# PWM_Board_77X.net
KiCad netlist of a schematic drawn in EAGLE
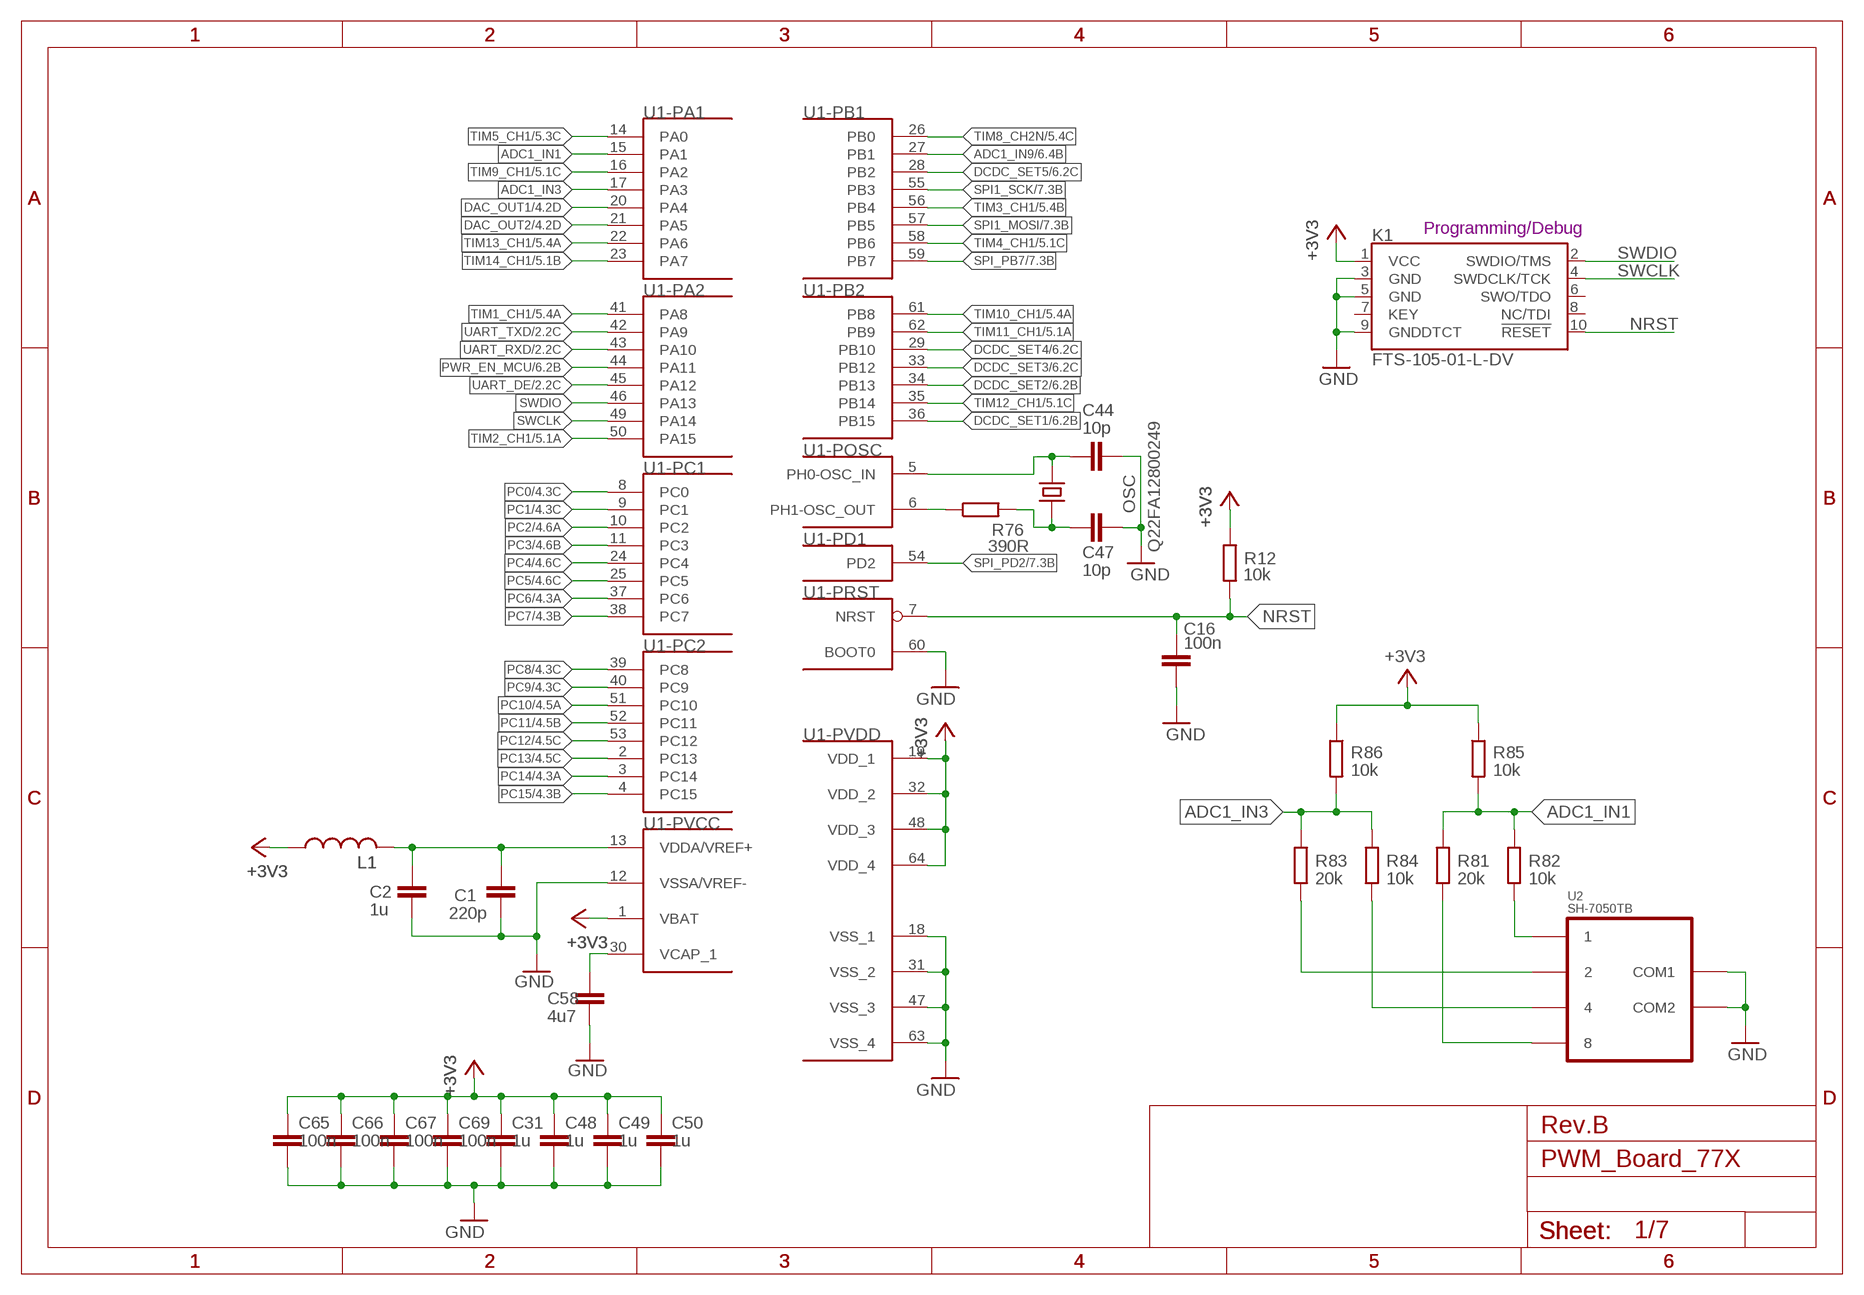
[diagram p0: schematic, sheet 1]
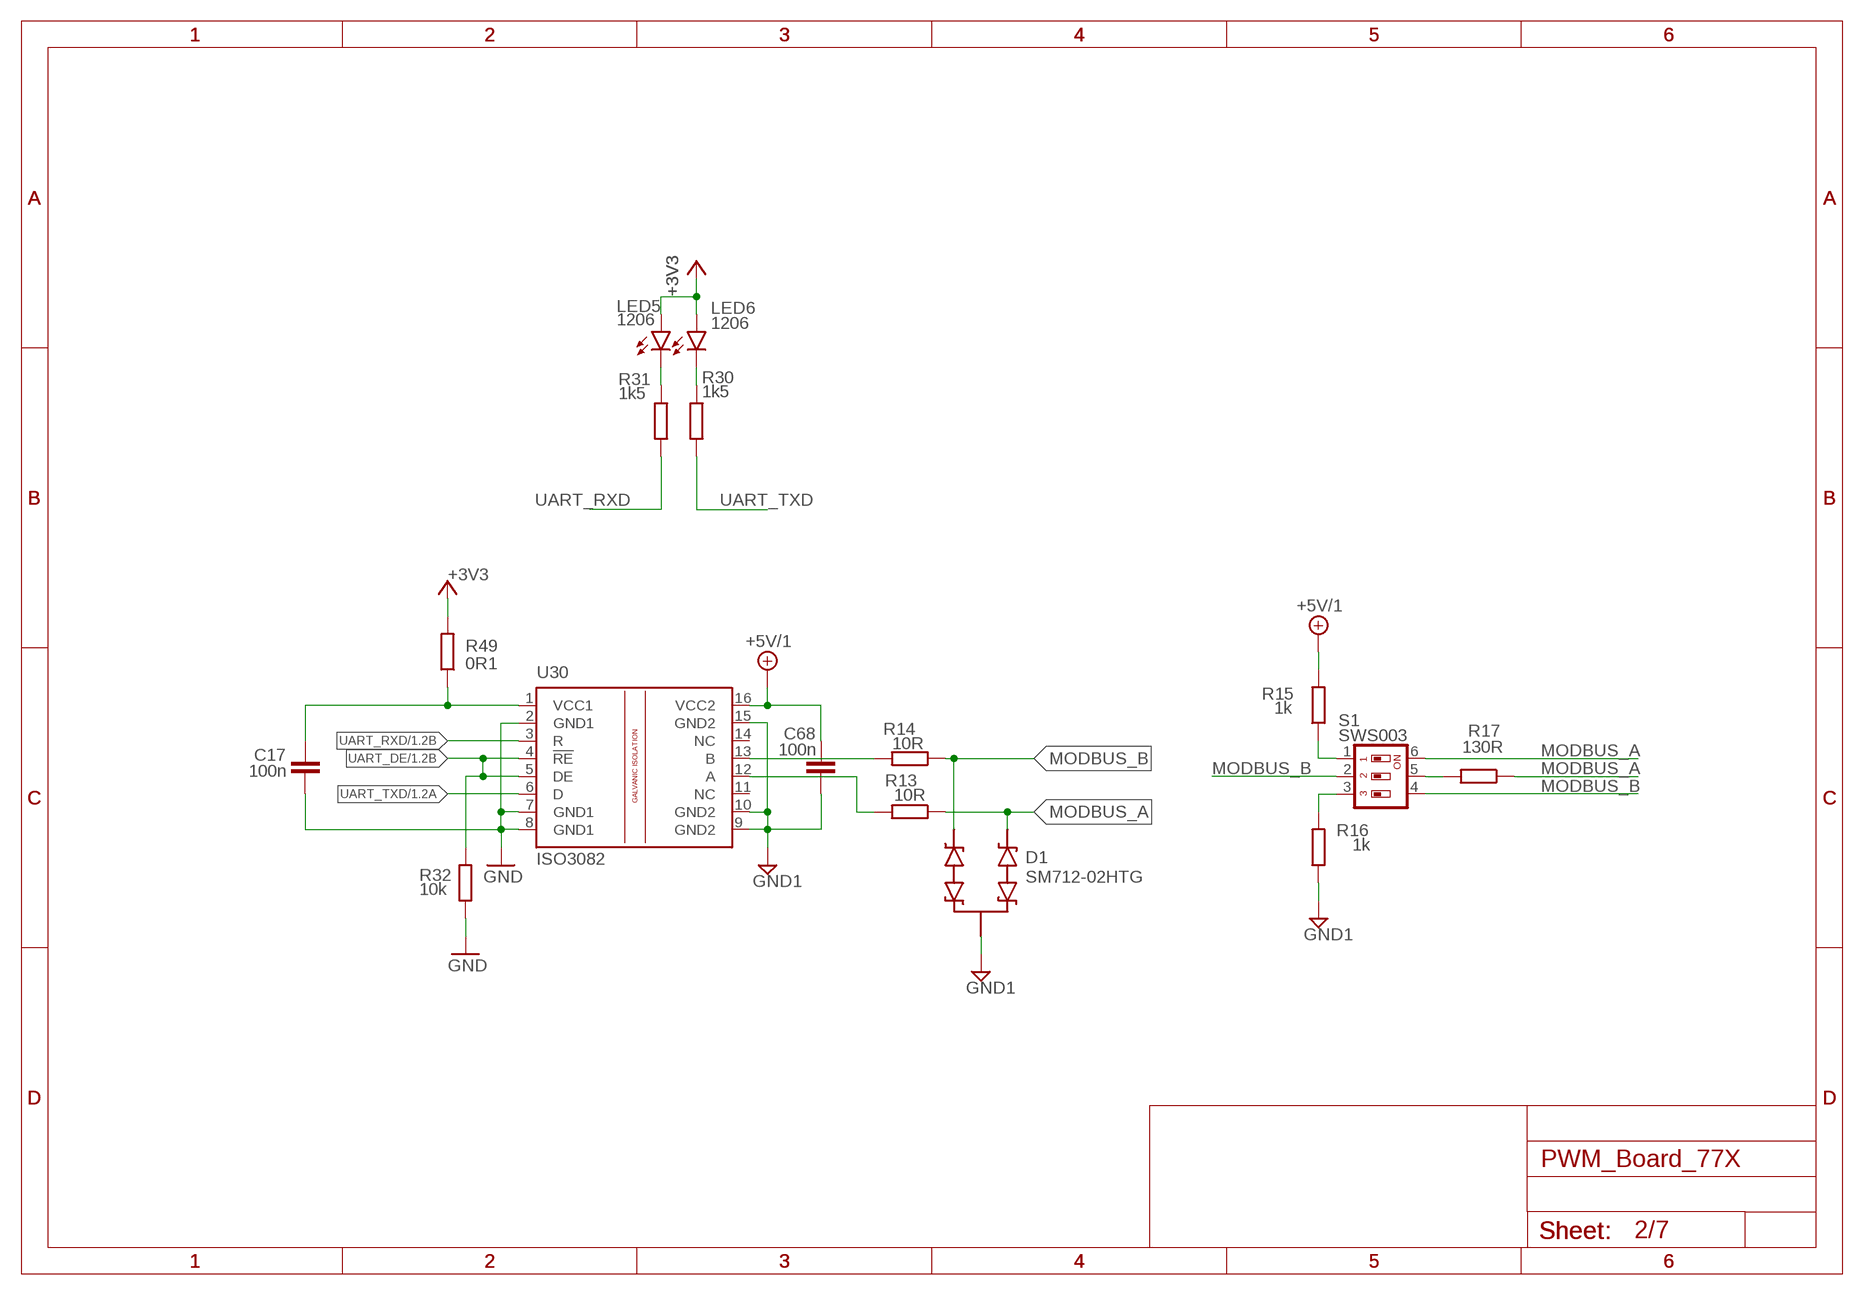
[diagram p1: schematic, sheet 2]
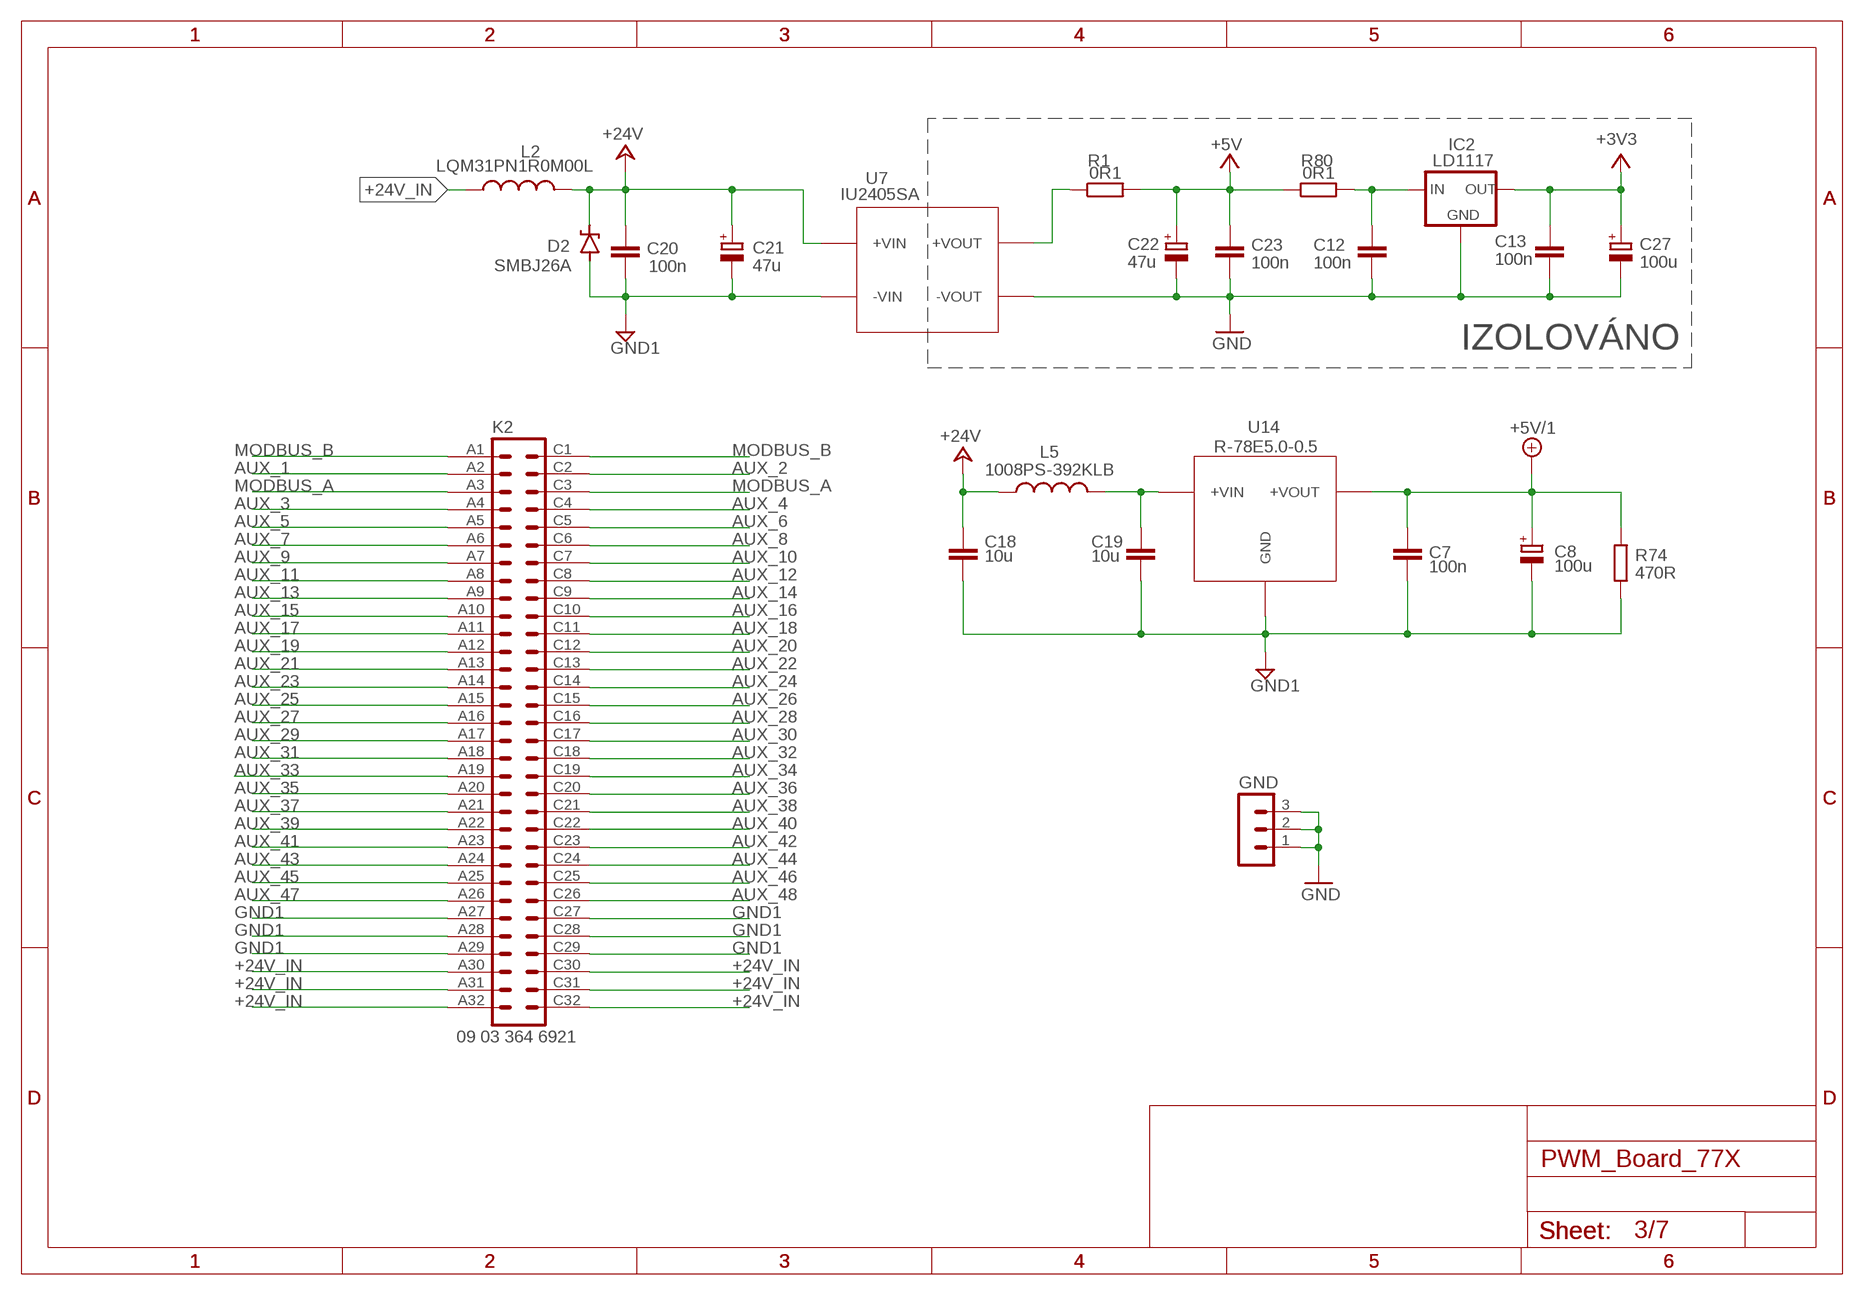
[diagram p2: schematic, sheet 3]
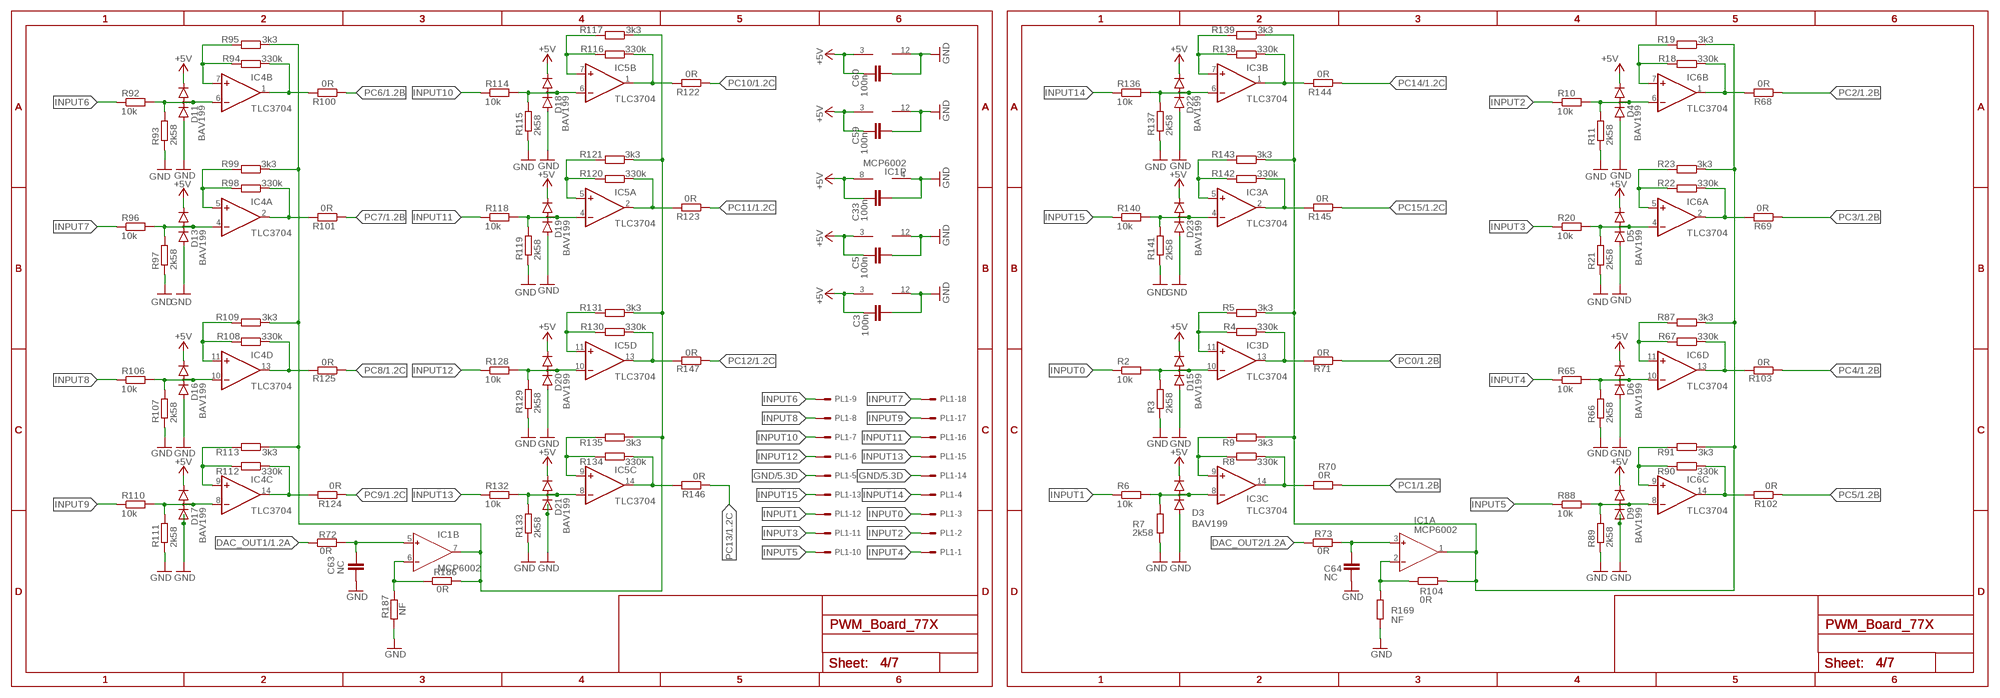
[diagram p3: schematic, sheet 4]
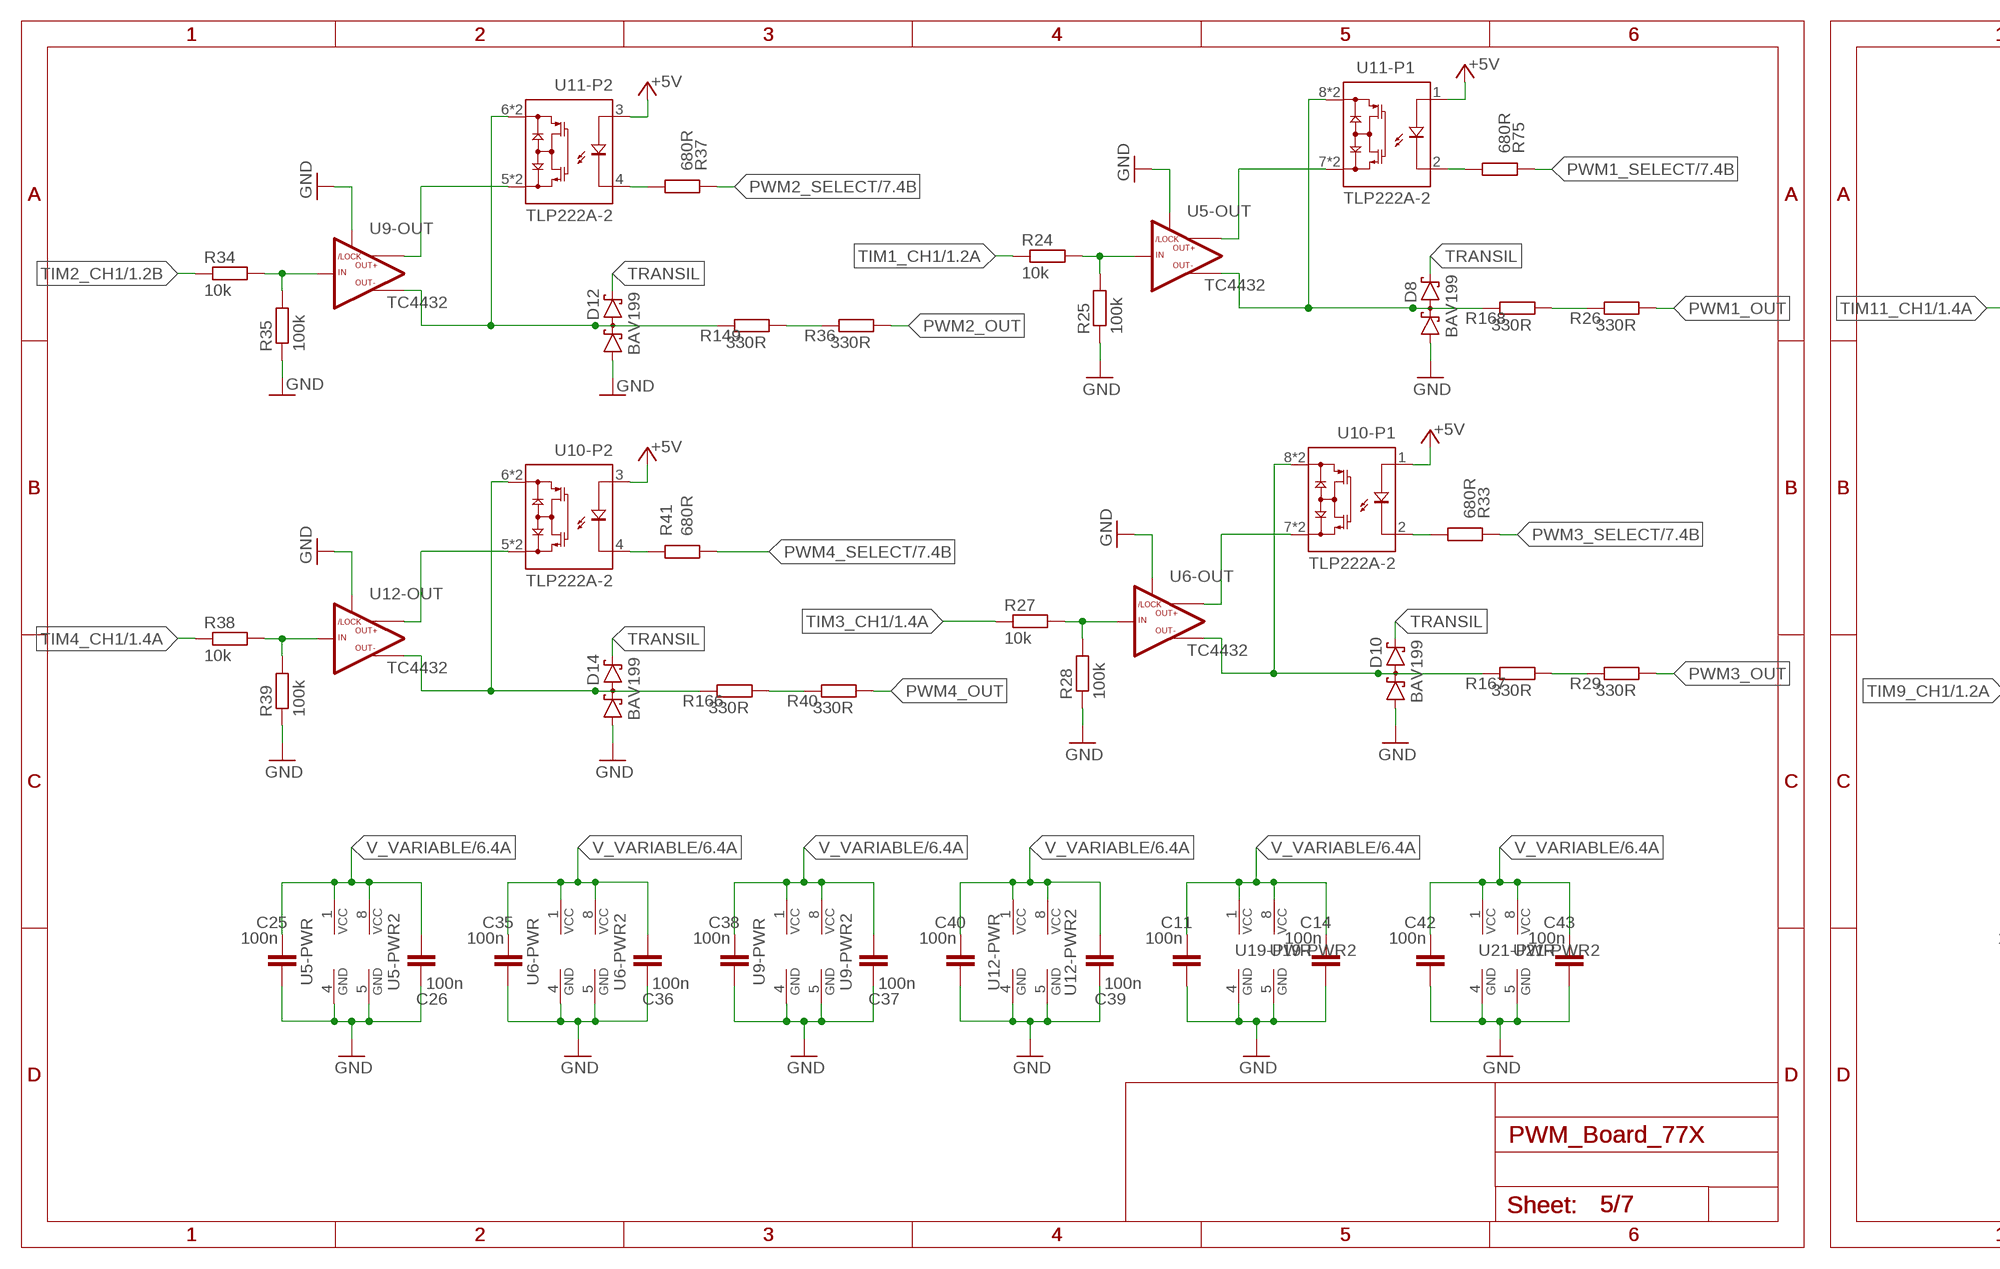
[diagram p4: schematic, sheet 5, part 1 of 2]
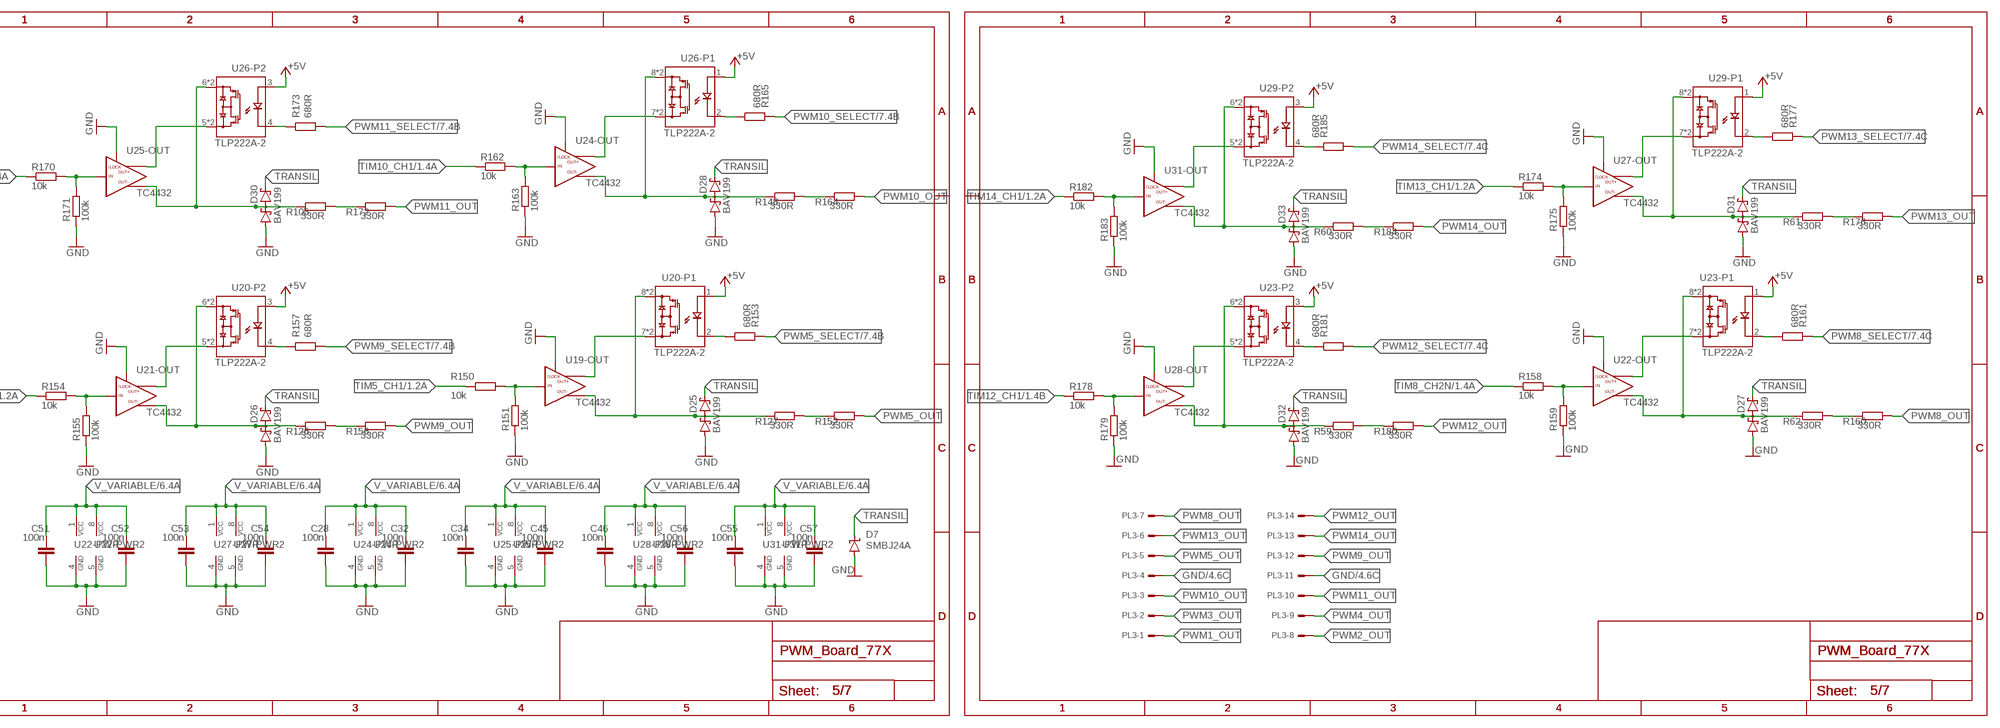
[diagram p5: schematic, sheet 5, part 2 of 2]
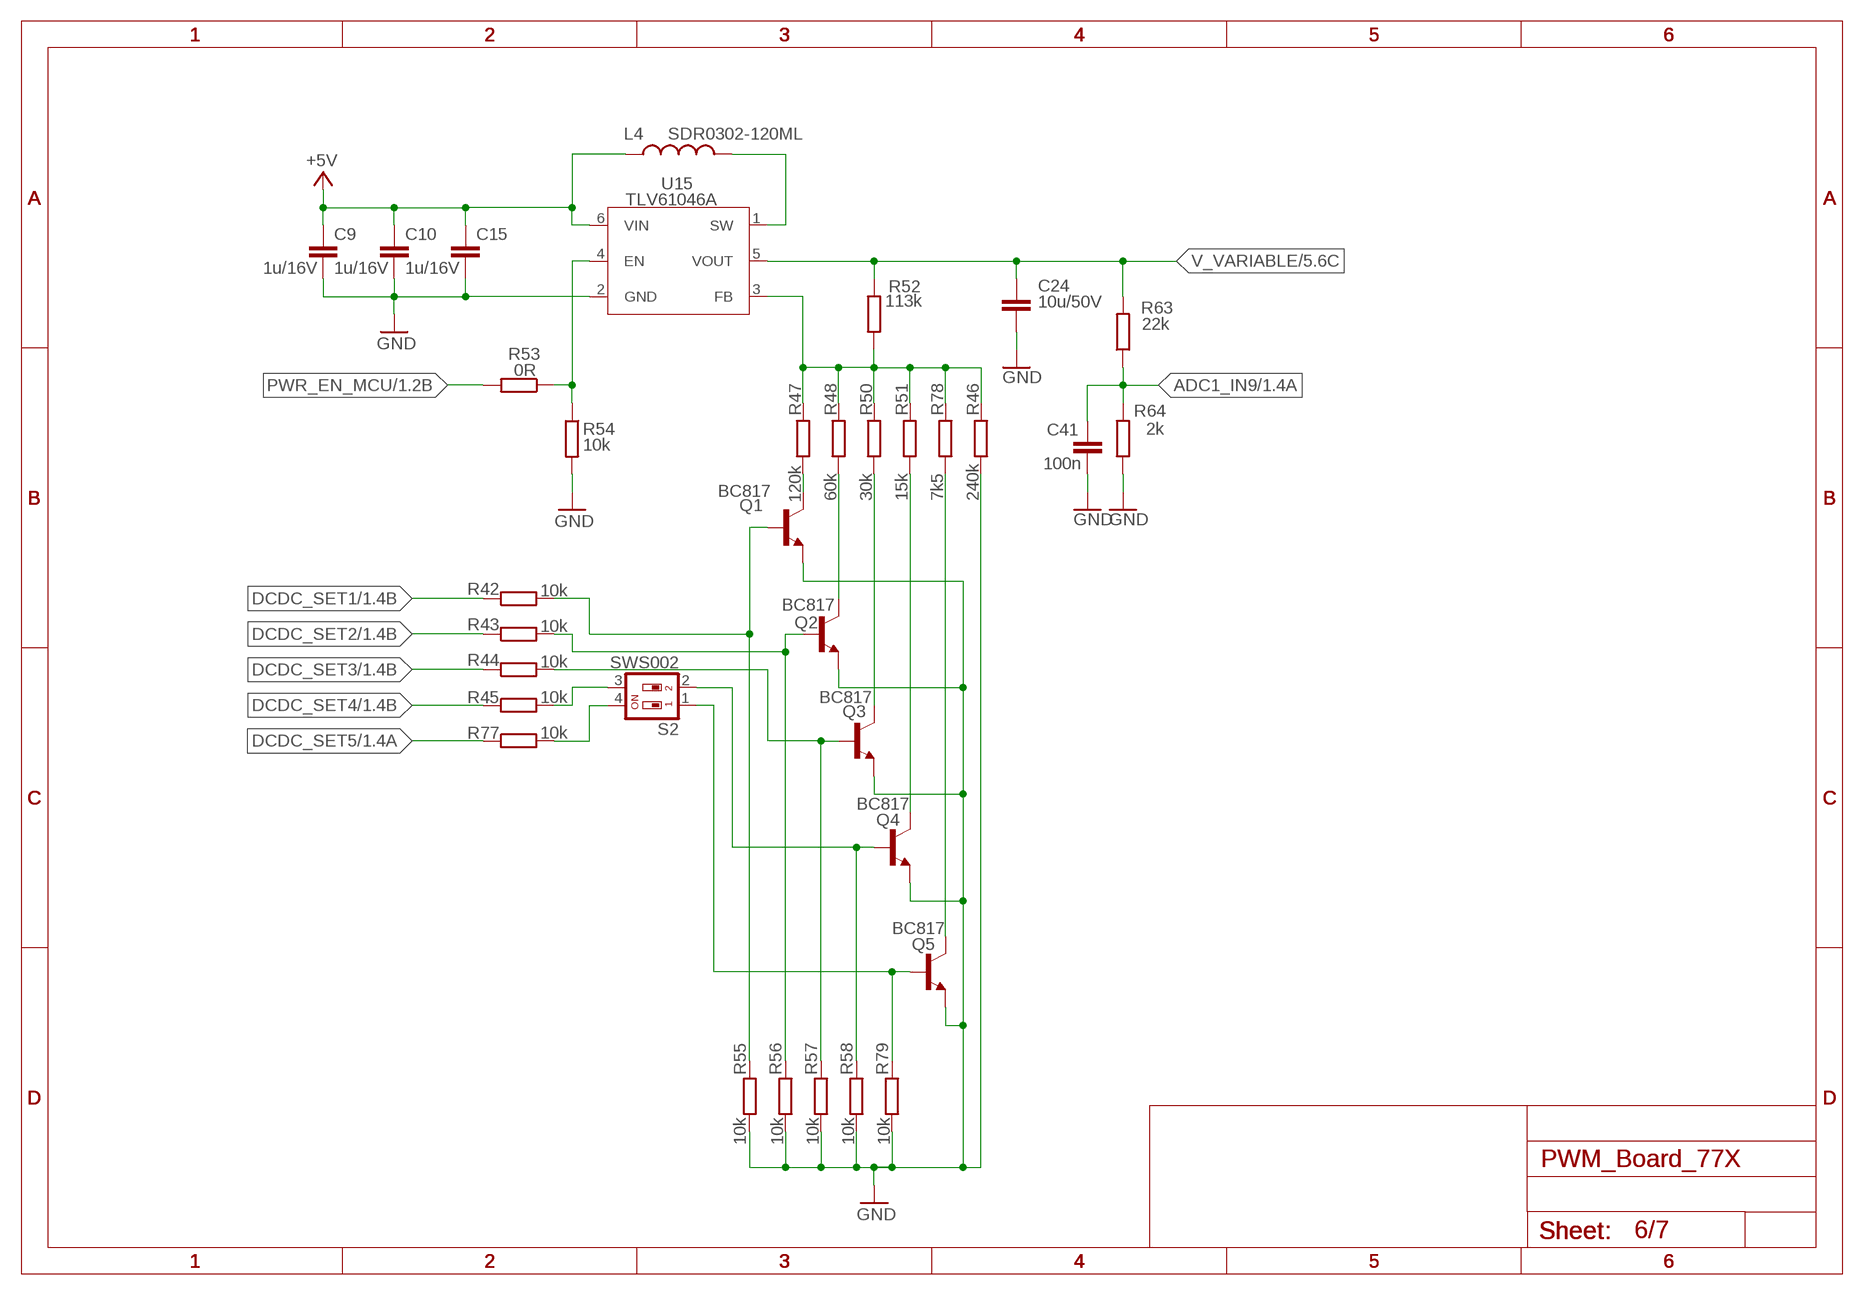
[diagram p6: schematic, sheet 6]
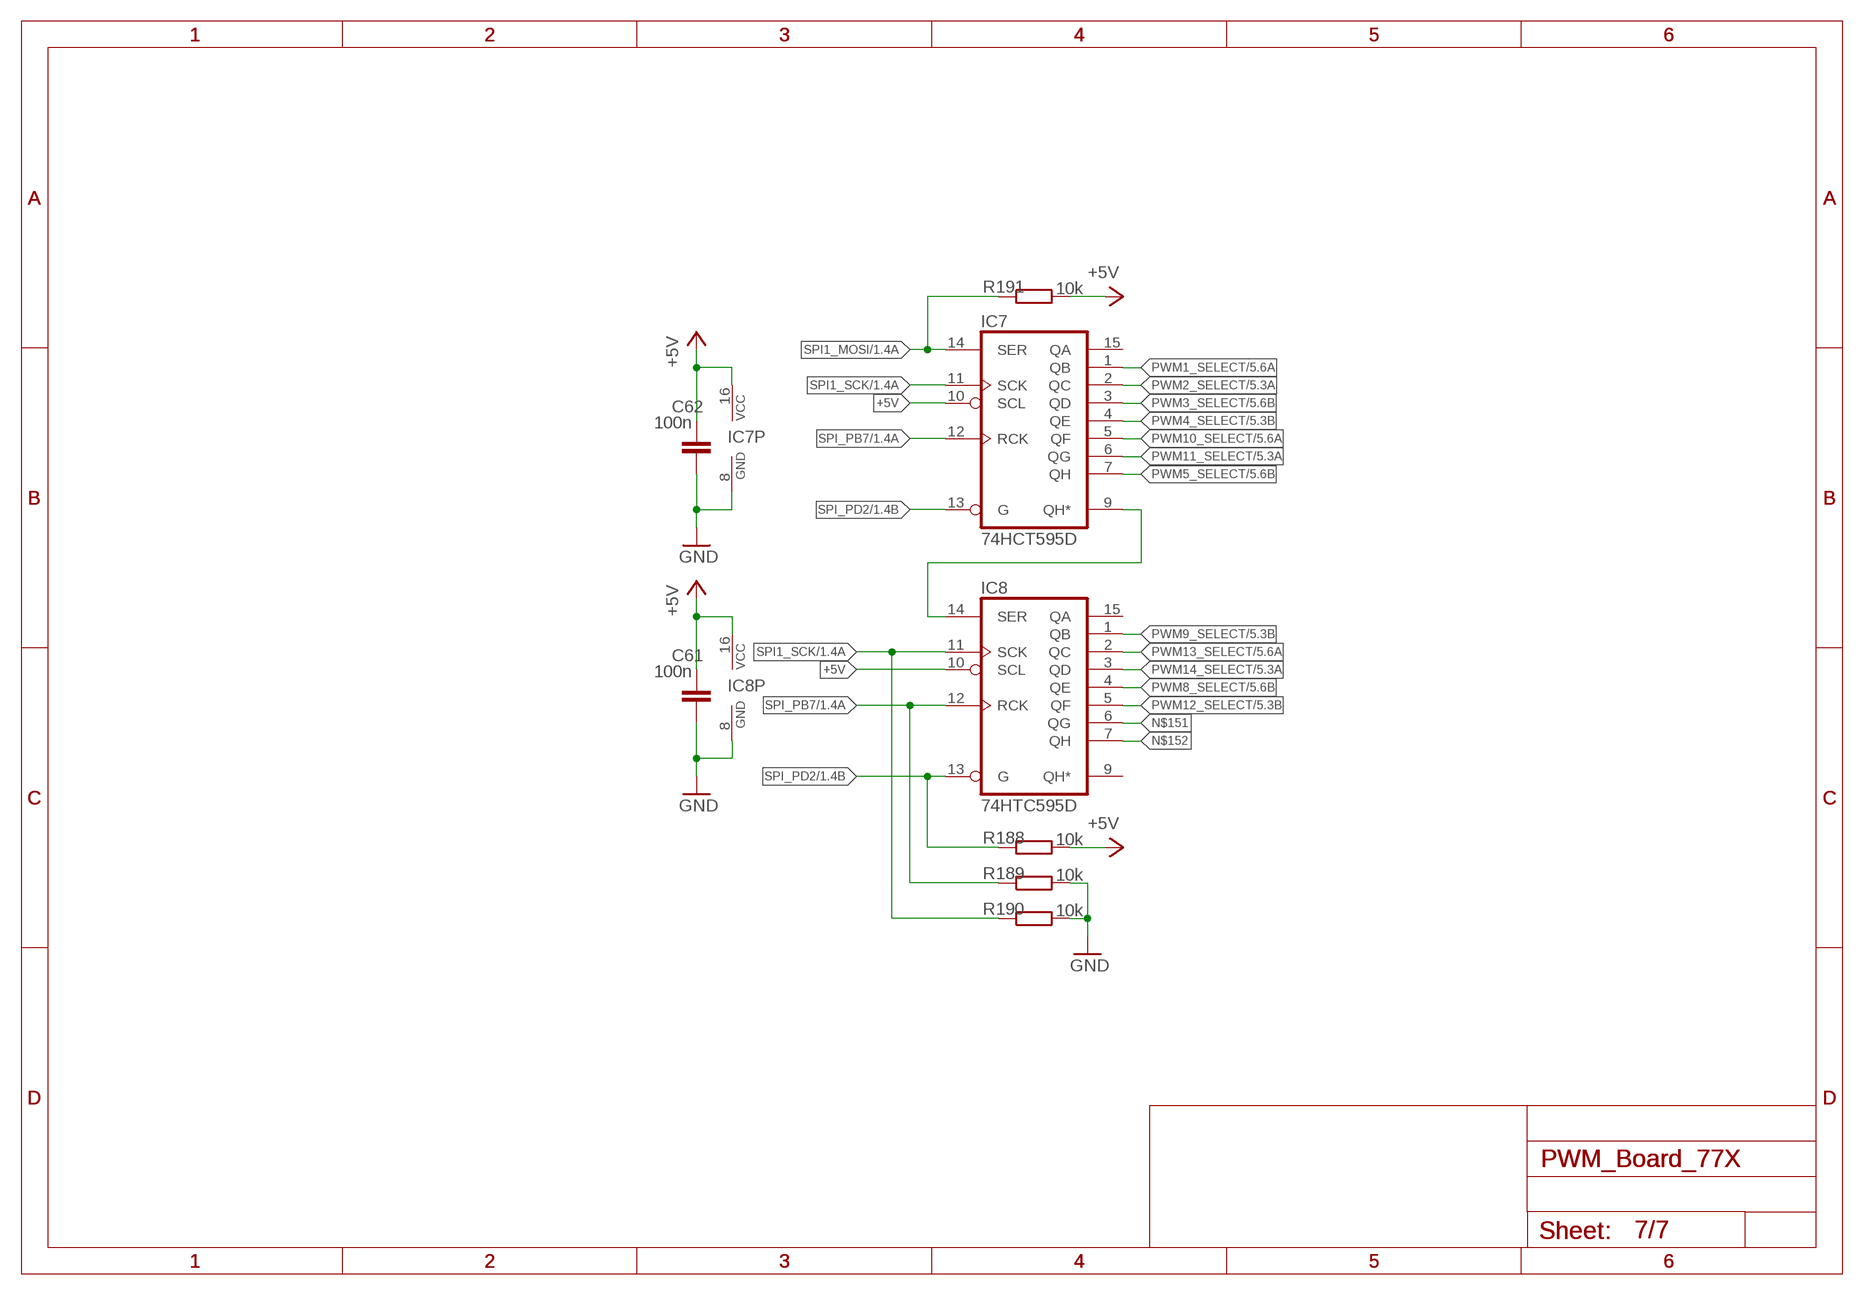
[diagram p7: schematic, sheet 7]

(export (version "E")
  (design (tool "Eeschema 10.0.6"))
  (components
    (comp (ref "C9")
      (value "1u/16V")
      (footprint "eagle-import:C0805")
      (libsource (lib "eagle-import") (part "rcl@1_C-EUC0805"))
    )
    (comp (ref "C10")
      (value "1u/16V")
      (footprint "eagle-import:C0805")
      (libsource (lib "eagle-import") (part "rcl@1_C-EUC0805"))
    )
    (comp (ref "C15")
      (value "1u/16V")
      (footprint "eagle-import:C0805")
      (libsource (lib "eagle-import") (part "rcl@1_C-EUC0805"))
    )
    (comp (ref "C24")
      (value "10u/50V")
      (footprint "eagle-import:C1206")
      (libsource (lib "eagle-import") (part "rcl@1_C-EUC1206"))
    )
    (comp (ref "C41")
      (value "100n")
      (footprint "eagle-import:C0805")
      (libsource (lib "eagle-import") (part "rcl@1_C-EUC0805"))
    )
    (comp (ref "L4")
      (value "SDR0302-120ML")
      (footprint "eagle-import:IND_NPI43C")
      (libsource (lib "eagle-import") (part "rcl2_L-US"))
    )
    (comp (ref "Q1")
      (value "BC817")
      (footprint "eagle-import:SOT23-BEC")
      (libsource (lib "eagle-import") (part "BC817SMD-25"))
    )
    (comp (ref "Q2")
      (value "BC817")
      (footprint "eagle-import:SOT23-BEC")
      (libsource (lib "eagle-import") (part "BC817SMD-25"))
    )
    (comp (ref "Q3")
      (value "BC817")
      (footprint "eagle-import:SOT23-BEC")
      (libsource (lib "eagle-import") (part "BC817SMD-25"))
    )
    (comp (ref "Q4")
      (value "BC817")
      (footprint "eagle-import:SOT23-BEC")
      (libsource (lib "eagle-import") (part "BC817SMD-25"))
    )
    (comp (ref "Q5")
      (value "BC817")
      (footprint "eagle-import:SOT23-BEC")
      (libsource (lib "eagle-import") (part "BC817SMD-25"))
    )
    (comp (ref "R42")
      (value "10k")
      (footprint "eagle-import:R0603")
      (libsource (lib "eagle-import") (part "rcl@1_R-EU_R0603"))
    )
    (comp (ref "R43")
      (value "10k")
      (footprint "eagle-import:R0603")
      (libsource (lib "eagle-import") (part "rcl@1_R-EU_R0603"))
    )
    (comp (ref "R44")
      (value "10k")
      (footprint "eagle-import:R0603")
      (libsource (lib "eagle-import") (part "rcl@1_R-EU_R0603"))
    )
    (comp (ref "R45")
      (value "10k")
      (footprint "eagle-import:R0603")
      (libsource (lib "eagle-import") (part "rcl@1_R-EU_R0603"))
    )
    (comp (ref "R46")
      (value "240k")
      (footprint "eagle-import:R0603")
      (libsource (lib "eagle-import") (part "rcl@1_R-EU_R0603"))
    )
    (comp (ref "R47")
      (value "120k")
      (footprint "eagle-import:R0603")
      (libsource (lib "eagle-import") (part "rcl@1_R-EU_R0603"))
    )
    (comp (ref "R48")
      (value "60k")
      (footprint "eagle-import:R0603")
      (libsource (lib "eagle-import") (part "rcl@1_R-EU_R0603"))
    )
    (comp (ref "R50")
      (value "30k")
      (footprint "eagle-import:R0603")
      (libsource (lib "eagle-import") (part "rcl@1_R-EU_R0603"))
    )
    (comp (ref "R51")
      (value "15k")
      (footprint "eagle-import:R0603")
      (libsource (lib "eagle-import") (part "rcl@1_R-EU_R0603"))
    )
    (comp (ref "R52")
      (value "113k")
      (footprint "eagle-import:R0603")
      (libsource (lib "eagle-import") (part "rcl@1_R-EU_R0603"))
    )
    (comp (ref "R53")
      (value "0R")
      (footprint "eagle-import:R0603")
      (libsource (lib "eagle-import") (part "R-EU_R0603"))
    )
    (comp (ref "R54")
      (value "10k")
      (footprint "eagle-import:R0603")
      (libsource (lib "eagle-import") (part "rcl@1_R-EU_R0603"))
    )
    (comp (ref "R55")
      (value "10k")
      (footprint "eagle-import:R0603")
      (libsource (lib "eagle-import") (part "rcl@1_R-EU_R0603"))
    )
    (comp (ref "R56")
      (value "10k")
      (footprint "eagle-import:R0603")
      (libsource (lib "eagle-import") (part "rcl@1_R-EU_R0603"))
    )
    (comp (ref "R57")
      (value "10k")
      (footprint "eagle-import:R0603")
      (libsource (lib "eagle-import") (part "rcl@1_R-EU_R0603"))
    )
    (comp (ref "R58")
      (value "10k")
      (footprint "eagle-import:R0603")
      (libsource (lib "eagle-import") (part "rcl@1_R-EU_R0603"))
    )
    (comp (ref "R63")
      (value "22k")
      (footprint "eagle-import:R0603")
      (libsource (lib "eagle-import") (part "R-EU_R0603"))
    )
    (comp (ref "R64")
      (value "2k")
      (footprint "eagle-import:R0603")
      (libsource (lib "eagle-import") (part "rcl@1_R-EU_R0603"))
    )
    (comp (ref "R77")
      (value "10k")
      (footprint "eagle-import:R0603")
      (libsource (lib "eagle-import") (part "rcl@1_R-EU_R0603"))
    )
    (comp (ref "R78")
      (value "7k5")
      (footprint "eagle-import:R0603")
      (libsource (lib "eagle-import") (part "rcl@1_R-EU_R0603"))
    )
    (comp (ref "R79")
      (value "10k")
      (footprint "eagle-import:R0603")
      (libsource (lib "eagle-import") (part "rcl@1_R-EU_R0603"))
    )
    (comp (ref "S2")
      (value "SWS002")
      (footprint "eagle-import:SMS-002")
      (libsource (lib "eagle-import") (part "SWS002"))
    )
    (comp (ref "U15")
      (value "TLV61046A")
      (footprint "eagle-import:SOT23-6")
      (libsource (lib "eagle-import") (part "TLV61046A"))
    )
    (comp (ref "C1")
      (value "220p")
      (footprint "eagle-import:C0603")
      (libsource (lib "eagle-import") (part "rcl_C-EUC0603"))
    )
    (comp (ref "C2")
      (value "1u")
      (footprint "eagle-import:C0805")
      (libsource (lib "eagle-import") (part "rcl@1_C-EUC0805"))
    )
    (comp (ref "C16")
      (value "100n")
      (footprint "eagle-import:C0603")
      (libsource (lib "eagle-import") (part "rcl_C-EUC0603"))
    )
    (comp (ref "C31")
      (value "1u")
      (footprint "eagle-import:C0805")
      (libsource (lib "eagle-import") (part "rcl@1_C-EUC0805"))
    )
    (comp (ref "C44")
      (value "10p")
      (footprint "eagle-import:C0603")
      (libsource (lib "eagle-import") (part "C-EUC0603"))
    )
    (comp (ref "C47")
      (value "10p")
      (footprint "eagle-import:C0603")
      (libsource (lib "eagle-import") (part "C-EUC0603"))
    )
    (comp (ref "C48")
      (value "1u")
      (footprint "eagle-import:C0805")
      (libsource (lib "eagle-import") (part "rcl@1_C-EUC0805"))
    )
    (comp (ref "C49")
      (value "1u")
      (footprint "eagle-import:C0805")
      (libsource (lib "eagle-import") (part "rcl@1_C-EUC0805"))
    )
    (comp (ref "C50")
      (value "1u")
      (footprint "eagle-import:C0805")
      (libsource (lib "eagle-import") (part "rcl@1_C-EUC0805"))
    )
    (comp (ref "C58")
      (value "4u7")
      (footprint "eagle-import:C0805")
      (libsource (lib "eagle-import") (part "rcl@1_C-EUC0805"))
    )
    (comp (ref "C65")
      (value "100n")
      (footprint "eagle-import:C0805")
      (libsource (lib "eagle-import") (part "rcl@1_C-EUC0805"))
    )
    (comp (ref "C66")
      (value "100n")
      (footprint "eagle-import:C0805")
      (libsource (lib "eagle-import") (part "rcl@1_C-EUC0805"))
    )
    (comp (ref "C67")
      (value "100n")
      (footprint "eagle-import:C0805")
      (libsource (lib "eagle-import") (part "rcl@1_C-EUC0805"))
    )
    (comp (ref "C69")
      (value "100n")
      (footprint "eagle-import:C0805")
      (libsource (lib "eagle-import") (part "rcl@1_C-EUC0805"))
    )
    (comp (ref "K1")
      (value "FTS-105-01-L-DV")
      (footprint "eagle-import:SAMTECH_FTSH-105-01")
      (libsource (lib "eagle-import") (part "CORTEX_DEBUG_SMD"))
    )
    (comp (ref "L1")
      (value "L-US")
      (footprint "eagle-import:R1206")
      (libsource (lib "eagle-import") (part "L-US"))
    )
    (comp (ref "OSC")
      (value "Q22FA12800249")
      (footprint "eagle-import:OSCILATOR")
      (libsource (lib "eagle-import") (part "Q22FA12800249"))
    )
    (comp (ref "R12")
      (value "10k")
      (footprint "eagle-import:R0603")
      (libsource (lib "eagle-import") (part "R-EU_R0603"))
    )
    (comp (ref "R76")
      (value "390R")
      (footprint "eagle-import:R0603")
      (libsource (lib "eagle-import") (part "R-EU_R0603"))
    )
    (comp (ref "R81")
      (value "20k")
      (footprint "eagle-import:R0603")
      (libsource (lib "eagle-import") (part "R-EU_R0603"))
    )
    (comp (ref "R82")
      (value "10k")
      (footprint "eagle-import:R0603")
      (libsource (lib "eagle-import") (part "R-EU_R0603"))
    )
    (comp (ref "R83")
      (value "20k")
      (footprint "eagle-import:R0603")
      (libsource (lib "eagle-import") (part "R-EU_R0603"))
    )
    (comp (ref "R84")
      (value "10k")
      (footprint "eagle-import:R0603")
      (libsource (lib "eagle-import") (part "R-EU_R0603"))
    )
    (comp (ref "R85")
      (value "10k")
      (footprint "eagle-import:R0603")
      (libsource (lib "eagle-import") (part "R-EU_R0603"))
    )
    (comp (ref "R86")
      (value "10k")
      (footprint "eagle-import:R0603")
      (libsource (lib "eagle-import") (part "R-EU_R0603"))
    )
    (comp (ref "U1")
      (value "STM32F446RE_64PIN")
      (footprint "eagle-import:LQFP64_F446RE")
      (libsource (lib "eagle-import") (part "STM32F446RE_64PIN"))
    )
    (comp (ref "U2")
      (value "SH-7050TB")
      (footprint "eagle-import:HEX_DEC")
      (libsource (lib "eagle-import") (part "SH-7050TB"))
    )
    (comp (ref "C11")
      (value "100n")
      (footprint "eagle-import:C0805")
      (libsource (lib "eagle-import") (part "rcl_C-EUC0805"))
    )
    (comp (ref "C14")
      (value "100n")
      (footprint "eagle-import:C0805")
      (libsource (lib "eagle-import") (part "rcl_C-EUC0805"))
    )
    (comp (ref "C25")
      (value "100n")
      (footprint "eagle-import:C0805")
      (libsource (lib "eagle-import") (part "rcl_C-EUC0805"))
    )
    (comp (ref "C26")
      (value "100n")
      (footprint "eagle-import:C0805")
      (libsource (lib "eagle-import") (part "rcl_C-EUC0805"))
    )
    (comp (ref "C28")
      (value "100n")
      (footprint "eagle-import:C0805")
      (libsource (lib "eagle-import") (part "rcl_C-EUC0805"))
    )
    (comp (ref "C32")
      (value "100n")
      (footprint "eagle-import:C0805")
      (libsource (lib "eagle-import") (part "rcl_C-EUC0805"))
    )
    (comp (ref "C34")
      (value "100n")
      (footprint "eagle-import:C0805")
      (libsource (lib "eagle-import") (part "rcl_C-EUC0805"))
    )
    (comp (ref "C35")
      (value "100n")
      (footprint "eagle-import:C0805")
      (libsource (lib "eagle-import") (part "rcl_C-EUC0805"))
    )
    (comp (ref "C36")
      (value "100n")
      (footprint "eagle-import:C0805")
      (libsource (lib "eagle-import") (part "rcl_C-EUC0805"))
    )
    (comp (ref "C37")
      (value "100n")
      (footprint "eagle-import:C0805")
      (libsource (lib "eagle-import") (part "rcl_C-EUC0805"))
    )
    (comp (ref "C38")
      (value "100n")
      (footprint "eagle-import:C0805")
      (libsource (lib "eagle-import") (part "rcl_C-EUC0805"))
    )
    (comp (ref "C39")
      (value "100n")
      (footprint "eagle-import:C0805")
      (libsource (lib "eagle-import") (part "rcl_C-EUC0805"))
    )
    (comp (ref "C40")
      (value "100n")
      (footprint "eagle-import:C0805")
      (libsource (lib "eagle-import") (part "rcl_C-EUC0805"))
    )
    (comp (ref "C42")
      (value "100n")
      (footprint "eagle-import:C0805")
      (libsource (lib "eagle-import") (part "rcl_C-EUC0805"))
    )
    (comp (ref "C43")
      (value "100n")
      (footprint "eagle-import:C0805")
      (libsource (lib "eagle-import") (part "rcl_C-EUC0805"))
    )
    (comp (ref "C45")
      (value "100n")
      (footprint "eagle-import:C0805")
      (libsource (lib "eagle-import") (part "rcl_C-EUC0805"))
    )
    (comp (ref "C46")
      (value "100n")
      (footprint "eagle-import:C0805")
      (libsource (lib "eagle-import") (part "rcl_C-EUC0805"))
    )
    (comp (ref "C51")
      (value "100n")
      (footprint "eagle-import:C0805")
      (libsource (lib "eagle-import") (part "rcl_C-EUC0805"))
    )
    (comp (ref "C52")
      (value "100n")
      (footprint "eagle-import:C0805")
      (libsource (lib "eagle-import") (part "rcl_C-EUC0805"))
    )
    (comp (ref "C53")
      (value "100n")
      (footprint "eagle-import:C0805")
      (libsource (lib "eagle-import") (part "rcl_C-EUC0805"))
    )
    (comp (ref "C54")
      (value "100n")
      (footprint "eagle-import:C0805")
      (libsource (lib "eagle-import") (part "rcl_C-EUC0805"))
    )
    (comp (ref "C55")
      (value "100n")
      (footprint "eagle-import:C0805")
      (libsource (lib "eagle-import") (part "rcl_C-EUC0805"))
    )
    (comp (ref "C56")
      (value "100n")
      (footprint "eagle-import:C0805")
      (libsource (lib "eagle-import") (part "rcl_C-EUC0805"))
    )
    (comp (ref "C57")
      (value "100n")
      (footprint "eagle-import:C0805")
      (libsource (lib "eagle-import") (part "rcl_C-EUC0805"))
    )
    (comp (ref "D7")
      (value "SMBJ24A")
      (footprint "eagle-import:SMBJ")
      (libsource (lib "eagle-import") (part "SUPPRESSOR-SMBJ"))
    )
    (comp (ref "D8")
      (value "BAV199")
      (footprint "eagle-import:SOT23")
      (libsource (lib "eagle-import") (part "BAS70-04"))
    )
    (comp (ref "D10")
      (value "BAV199")
      (footprint "eagle-import:SOT23")
      (libsource (lib "eagle-import") (part "BAS70-04"))
    )
    (comp (ref "D12")
      (value "BAV199")
      (footprint "eagle-import:SOT23")
      (libsource (lib "eagle-import") (part "BAS70-04"))
    )
    (comp (ref "D14")
      (value "BAV199")
      (footprint "eagle-import:SOT23")
      (libsource (lib "eagle-import") (part "BAS70-04"))
    )
    (comp (ref "D25")
      (value "BAV199")
      (footprint "eagle-import:SOT23")
      (libsource (lib "eagle-import") (part "BAS70-04"))
    )
    (comp (ref "D26")
      (value "BAV199")
      (footprint "eagle-import:SOT23")
      (libsource (lib "eagle-import") (part "BAS70-04"))
    )
    (comp (ref "D27")
      (value "BAV199")
      (footprint "eagle-import:SOT23")
      (libsource (lib "eagle-import") (part "BAS70-04"))
    )
    (comp (ref "D28")
      (value "BAV199")
      (footprint "eagle-import:SOT23")
      (libsource (lib "eagle-import") (part "BAS70-04"))
    )
    (comp (ref "D30")
      (value "BAV199")
      (footprint "eagle-import:SOT23")
      (libsource (lib "eagle-import") (part "BAS70-04"))
    )
    (comp (ref "D31")
      (value "BAV199")
      (footprint "eagle-import:SOT23")
      (libsource (lib "eagle-import") (part "BAS70-04"))
    )
    (comp (ref "D32")
      (value "BAV199")
      (footprint "eagle-import:SOT23")
      (libsource (lib "eagle-import") (part "BAS70-04"))
    )
    (comp (ref "D33")
      (value "BAV199")
      (footprint "eagle-import:SOT23")
      (libsource (lib "eagle-import") (part "BAS70-04"))
    )
    (comp (ref "PL3")
      (value "555X-14H-NO-HOLES")
      (footprint "eagle-import:5569-14_NO_HOLES")
      (libsource (lib "eagle-import") (part "555X-14H-NO-HOLES"))
    )
    (comp (ref "R24")
      (value "10k")
      (footprint "eagle-import:R0603")
      (libsource (lib "eagle-import") (part "R-EU_R0603"))
    )
    (comp (ref "R25")
      (value "100k")
      (footprint "eagle-import:R0603")
      (libsource (lib "eagle-import") (part "rcl@1_R-EU_R0603"))
    )
    (comp (ref "R26")
      (value "330R")
      (footprint "eagle-import:R1210")
      (libsource (lib "eagle-import") (part "resistor_R-EU_R1210"))
    )
    (comp (ref "R27")
      (value "10k")
      (footprint "eagle-import:R0603")
      (libsource (lib "eagle-import") (part "R-EU_R0603"))
    )
    (comp (ref "R28")
      (value "100k")
      (footprint "eagle-import:R0603")
      (libsource (lib "eagle-import") (part "rcl@1_R-EU_R0603"))
    )
    (comp (ref "R29")
      (value "330R")
      (footprint "eagle-import:R1210")
      (libsource (lib "eagle-import") (part "resistor_R-EU_R1210"))
    )
    (comp (ref "R33")
      (value "680R")
      (footprint "eagle-import:R0603")
      (libsource (lib "eagle-import") (part "R-EU_R0603"))
    )
    (comp (ref "R34")
      (value "10k")
      (footprint "eagle-import:R0603")
      (libsource (lib "eagle-import") (part "R-EU_R0603"))
    )
    (comp (ref "R35")
      (value "100k")
      (footprint "eagle-import:R0603")
      (libsource (lib "eagle-import") (part "rcl@1_R-EU_R0603"))
    )
    (comp (ref "R36")
      (value "330R")
      (footprint "eagle-import:R1210")
      (libsource (lib "eagle-import") (part "resistor_R-EU_R1210"))
    )
    (comp (ref "R37")
      (value "680R")
      (footprint "eagle-import:R0603")
      (libsource (lib "eagle-import") (part "R-EU_R0603"))
    )
    (comp (ref "R38")
      (value "10k")
      (footprint "eagle-import:R0603")
      (libsource (lib "eagle-import") (part "R-EU_R0603"))
    )
    (comp (ref "R39")
      (value "100k")
      (footprint "eagle-import:R0603")
      (libsource (lib "eagle-import") (part "rcl@1_R-EU_R0603"))
    )
    (comp (ref "R40")
      (value "330R")
      (footprint "eagle-import:R1210")
      (libsource (lib "eagle-import") (part "resistor_R-EU_R1210"))
    )
    (comp (ref "R41")
      (value "680R")
      (footprint "eagle-import:R0603")
      (libsource (lib "eagle-import") (part "R-EU_R0603"))
    )
    (comp (ref "R59")
      (value "330R")
      (footprint "eagle-import:R1210")
      (libsource (lib "eagle-import") (part "resistor_R-EU_R1210"))
    )
    (comp (ref "R60")
      (value "330R")
      (footprint "eagle-import:R1210")
      (libsource (lib "eagle-import") (part "resistor_R-EU_R1210"))
    )
    (comp (ref "R61")
      (value "330R")
      (footprint "eagle-import:R1210")
      (libsource (lib "eagle-import") (part "resistor_R-EU_R1210"))
    )
    (comp (ref "R62")
      (value "330R")
      (footprint "eagle-import:R1210")
      (libsource (lib "eagle-import") (part "resistor_R-EU_R1210"))
    )
    (comp (ref "R75")
      (value "680R")
      (footprint "eagle-import:R0603")
      (libsource (lib "eagle-import") (part "R-EU_R0603"))
    )
    (comp (ref "R105")
      (value "330R")
      (footprint "eagle-import:R1210")
      (libsource (lib "eagle-import") (part "resistor_R-EU_R1210"))
    )
    (comp (ref "R126")
      (value "330R")
      (footprint "eagle-import:R1210")
      (libsource (lib "eagle-import") (part "resistor_R-EU_R1210"))
    )
    (comp (ref "R127")
      (value "330R")
      (footprint "eagle-import:R1210")
      (libsource (lib "eagle-import") (part "resistor_R-EU_R1210"))
    )
    (comp (ref "R148")
      (value "330R")
      (footprint "eagle-import:R1210")
      (libsource (lib "eagle-import") (part "resistor_R-EU_R1210"))
    )
    (comp (ref "R149")
      (value "330R")
      (footprint "eagle-import:R1210")
      (libsource (lib "eagle-import") (part "resistor_R-EU_R1210"))
    )
    (comp (ref "R150")
      (value "10k")
      (footprint "eagle-import:R0603")
      (libsource (lib "eagle-import") (part "R-EU_R0603"))
    )
    (comp (ref "R151")
      (value "100k")
      (footprint "eagle-import:R0603")
      (libsource (lib "eagle-import") (part "rcl@1_R-EU_R0603"))
    )
    (comp (ref "R152")
      (value "330R")
      (footprint "eagle-import:R1210")
      (libsource (lib "eagle-import") (part "resistor_R-EU_R1210"))
    )
    (comp (ref "R153")
      (value "680R")
      (footprint "eagle-import:R0603")
      (libsource (lib "eagle-import") (part "R-EU_R0603"))
    )
    (comp (ref "R154")
      (value "10k")
      (footprint "eagle-import:R0603")
      (libsource (lib "eagle-import") (part "R-EU_R0603"))
    )
    (comp (ref "R155")
      (value "100k")
      (footprint "eagle-import:R0603")
      (libsource (lib "eagle-import") (part "rcl@1_R-EU_R0603"))
    )
    (comp (ref "R156")
      (value "330R")
      (footprint "eagle-import:R1210")
      (libsource (lib "eagle-import") (part "resistor_R-EU_R1210"))
    )
    (comp (ref "R157")
      (value "680R")
      (footprint "eagle-import:R0603")
      (libsource (lib "eagle-import") (part "R-EU_R0603"))
    )
    (comp (ref "R158")
      (value "10k")
      (footprint "eagle-import:R0603")
      (libsource (lib "eagle-import") (part "R-EU_R0603"))
    )
    (comp (ref "R159")
      (value "100k")
      (footprint "eagle-import:R0603")
      (libsource (lib "eagle-import") (part "rcl@1_R-EU_R0603"))
    )
    (comp (ref "R160")
      (value "330R")
      (footprint "eagle-import:R1210")
      (libsource (lib "eagle-import") (part "resistor_R-EU_R1210"))
    )
    (comp (ref "R161")
      (value "680R")
      (footprint "eagle-import:R0603")
      (libsource (lib "eagle-import") (part "R-EU_R0603"))
    )
    (comp (ref "R162")
      (value "10k")
      (footprint "eagle-import:R0603")
      (libsource (lib "eagle-import") (part "R-EU_R0603"))
    )
    (comp (ref "R163")
      (value "100k")
      (footprint "eagle-import:R0603")
      (libsource (lib "eagle-import") (part "rcl@1_R-EU_R0603"))
    )
    (comp (ref "R164")
      (value "330R")
      (footprint "eagle-import:R1210")
      (libsource (lib "eagle-import") (part "resistor_R-EU_R1210"))
    )
    (comp (ref "R165")
      (value "680R")
      (footprint "eagle-import:R0603")
      (libsource (lib "eagle-import") (part "R-EU_R0603"))
    )
    (comp (ref "R166")
      (value "330R")
      (footprint "eagle-import:R1210")
      (libsource (lib "eagle-import") (part "resistor_R-EU_R1210"))
    )
    (comp (ref "R167")
      (value "330R")
      (footprint "eagle-import:R1210")
      (libsource (lib "eagle-import") (part "resistor_R-EU_R1210"))
    )
    (comp (ref "R168")
      (value "330R")
      (footprint "eagle-import:R1210")
      (libsource (lib "eagle-import") (part "resistor_R-EU_R1210"))
    )
    (comp (ref "R170")
      (value "10k")
      (footprint "eagle-import:R0603")
      (libsource (lib "eagle-import") (part "R-EU_R0603"))
    )
    (comp (ref "R171")
      (value "100k")
      (footprint "eagle-import:R0603")
      (libsource (lib "eagle-import") (part "rcl@1_R-EU_R0603"))
    )
    (comp (ref "R172")
      (value "330R")
      (footprint "eagle-import:R1210")
      (libsource (lib "eagle-import") (part "resistor_R-EU_R1210"))
    )
    (comp (ref "R173")
      (value "680R")
      (footprint "eagle-import:R0603")
      (libsource (lib "eagle-import") (part "R-EU_R0603"))
    )
    (comp (ref "R174")
      (value "10k")
      (footprint "eagle-import:R0603")
      (libsource (lib "eagle-import") (part "R-EU_R0603"))
    )
    (comp (ref "R175")
      (value "100k")
      (footprint "eagle-import:R0603")
      (libsource (lib "eagle-import") (part "rcl@1_R-EU_R0603"))
    )
    (comp (ref "R176")
      (value "330R")
      (footprint "eagle-import:R1210")
      (libsource (lib "eagle-import") (part "resistor_R-EU_R1210"))
    )
    (comp (ref "R177")
      (value "680R")
      (footprint "eagle-import:R0603")
      (libsource (lib "eagle-import") (part "R-EU_R0603"))
    )
    (comp (ref "R178")
      (value "10k")
      (footprint "eagle-import:R0603")
      (libsource (lib "eagle-import") (part "R-EU_R0603"))
    )
    (comp (ref "R179")
      (value "100k")
      (footprint "eagle-import:R0603")
      (libsource (lib "eagle-import") (part "rcl@1_R-EU_R0603"))
    )
    (comp (ref "R180")
      (value "330R")
      (footprint "eagle-import:R1210")
      (libsource (lib "eagle-import") (part "resistor_R-EU_R1210"))
    )
    (comp (ref "R181")
      (value "680R")
      (footprint "eagle-import:R0603")
      (libsource (lib "eagle-import") (part "R-EU_R0603"))
    )
    (comp (ref "R182")
      (value "10k")
      (footprint "eagle-import:R0603")
      (libsource (lib "eagle-import") (part "R-EU_R0603"))
    )
    (comp (ref "R183")
      (value "100k")
      (footprint "eagle-import:R0603")
      (libsource (lib "eagle-import") (part "rcl@1_R-EU_R0603"))
    )
    (comp (ref "R184")
      (value "330R")
      (footprint "eagle-import:R1210")
      (libsource (lib "eagle-import") (part "resistor_R-EU_R1210"))
    )
    (comp (ref "R185")
      (value "680R")
      (footprint "eagle-import:R0603")
      (libsource (lib "eagle-import") (part "R-EU_R0603"))
    )
    (comp (ref "U5")
      (value "TC4432")
      (footprint "eagle-import:SO08")
      (libsource (lib "eagle-import") (part "TC4432"))
    )
    (comp (ref "U6")
      (value "TC4432")
      (footprint "eagle-import:SO08")
      (libsource (lib "eagle-import") (part "TC4432"))
    )
    (comp (ref "U9")
      (value "TC4432")
      (footprint "eagle-import:SO08")
      (libsource (lib "eagle-import") (part "TC4432"))
    )
    (comp (ref "U10")
      (value "TLP222A-2")
      (footprint "eagle-import:DIL8-SMD_V2")
      (libsource (lib "eagle-import") (part "TLP222A-2/TLP171D"))
    )
    (comp (ref "U11")
      (value "TLP222A-2")
      (footprint "eagle-import:DIL8-SMD_V2")
      (libsource (lib "eagle-import") (part "TLP222A-2/TLP171D"))
    )
    (comp (ref "U12")
      (value "TC4432")
      (footprint "eagle-import:SO08")
      (libsource (lib "eagle-import") (part "TC4432"))
    )
    (comp (ref "U19")
      (value "TC4432")
      (footprint "eagle-import:SO08")
      (libsource (lib "eagle-import") (part "TC4432"))
    )
    (comp (ref "U20")
      (value "TLP222A-2")
      (footprint "eagle-import:DIL8-SMD_V2")
      (libsource (lib "eagle-import") (part "TLP222A-2/TLP171D"))
    )
    (comp (ref "U21")
      (value "TC4432")
      (footprint "eagle-import:SO08")
      (libsource (lib "eagle-import") (part "TC4432"))
    )
    (comp (ref "U22")
      (value "TC4432")
      (footprint "eagle-import:SO08")
      (libsource (lib "eagle-import") (part "TC4432"))
    )
    (comp (ref "U23")
      (value "TLP222A-2")
      (footprint "eagle-import:DIL8-SMD_V2")
      (libsource (lib "eagle-import") (part "TLP222A-2/TLP171D"))
    )
    (comp (ref "U24")
      (value "TC4432")
      (footprint "eagle-import:SO08")
      (libsource (lib "eagle-import") (part "TC4432"))
    )
    (comp (ref "U25")
      (value "TC4432")
      (footprint "eagle-import:SO08")
      (libsource (lib "eagle-import") (part "TC4432"))
    )
    (comp (ref "U26")
      (value "TLP222A-2")
      (footprint "eagle-import:DIL8-SMD_V2")
      (libsource (lib "eagle-import") (part "TLP222A-2/TLP171D"))
    )
    (comp (ref "U27")
      (value "TC4432")
      (footprint "eagle-import:SO08")
      (libsource (lib "eagle-import") (part "TC4432"))
    )
    (comp (ref "U28")
      (value "TC4432")
      (footprint "eagle-import:SO08")
      (libsource (lib "eagle-import") (part "TC4432"))
    )
    (comp (ref "U29")
      (value "TLP222A-2")
      (footprint "eagle-import:DIL8-SMD_V2")
      (libsource (lib "eagle-import") (part "TLP222A-2/TLP171D"))
    )
    (comp (ref "U31")
      (value "TC4432")
      (footprint "eagle-import:SO08")
      (libsource (lib "eagle-import") (part "TC4432"))
    )
    (comp (ref "C3")
      (value "100n")
      (footprint "eagle-import:C0805")
      (libsource (lib "eagle-import") (part "rcl_C-EUC0805"))
    )
    (comp (ref "C5")
      (value "100n")
      (footprint "eagle-import:C0805")
      (libsource (lib "eagle-import") (part "rcl_C-EUC0805"))
    )
    (comp (ref "C33")
      (value "100n")
      (footprint "eagle-import:C0805")
      (libsource (lib "eagle-import") (part "rcl_C-EUC0805"))
    )
    (comp (ref "C59")
      (value "100n")
      (footprint "eagle-import:C0805")
      (libsource (lib "eagle-import") (part "rcl_C-EUC0805"))
    )
    (comp (ref "C60")
      (value "100n")
      (footprint "eagle-import:C0805")
      (libsource (lib "eagle-import") (part "rcl_C-EUC0805"))
    )
    (comp (ref "C63")
      (value "NC")
      (footprint "eagle-import:C0603")
      (libsource (lib "eagle-import") (part "C-EUC0603"))
    )
    (comp (ref "C64")
      (value "NC")
      (footprint "eagle-import:C0603")
      (libsource (lib "eagle-import") (part "C-EUC0603"))
    )
    (comp (ref "D3")
      (value "BAV199")
      (footprint "eagle-import:SOT23")
      (libsource (lib "eagle-import") (part "BAV199"))
    )
    (comp (ref "D4")
      (value "BAV199")
      (footprint "eagle-import:SOT23")
      (libsource (lib "eagle-import") (part "BAV199"))
    )
    (comp (ref "D5")
      (value "BAV199")
      (footprint "eagle-import:SOT23")
      (libsource (lib "eagle-import") (part "BAV199"))
    )
    (comp (ref "D6")
      (value "BAV199")
      (footprint "eagle-import:SOT23")
      (libsource (lib "eagle-import") (part "BAV199"))
    )
    (comp (ref "D9")
      (value "BAV199")
      (footprint "eagle-import:SOT23")
      (libsource (lib "eagle-import") (part "BAV199"))
    )
    (comp (ref "D11")
      (value "BAV199")
      (footprint "eagle-import:SOT23")
      (libsource (lib "eagle-import") (part "BAV199"))
    )
    (comp (ref "D13")
      (value "BAV199")
      (footprint "eagle-import:SOT23")
      (libsource (lib "eagle-import") (part "BAV199"))
    )
    (comp (ref "D15")
      (value "BAV199")
      (footprint "eagle-import:SOT23")
      (libsource (lib "eagle-import") (part "BAV199"))
    )
    (comp (ref "D16")
      (value "BAV199")
      (footprint "eagle-import:SOT23")
      (libsource (lib "eagle-import") (part "BAV199"))
    )
    (comp (ref "D17")
      (value "BAV199")
      (footprint "eagle-import:SOT23")
      (libsource (lib "eagle-import") (part "BAV199"))
    )
    (comp (ref "D18")
      (value "BAV199")
      (footprint "eagle-import:SOT23")
      (libsource (lib "eagle-import") (part "BAV199"))
    )
    (comp (ref "D19")
      (value "BAV199")
      (footprint "eagle-import:SOT23")
      (libsource (lib "eagle-import") (part "BAV199"))
    )
    (comp (ref "D20")
      (value "BAV199")
      (footprint "eagle-import:SOT23")
      (libsource (lib "eagle-import") (part "BAV199"))
    )
    (comp (ref "D21")
      (value "BAV199")
      (footprint "eagle-import:SOT23")
      (libsource (lib "eagle-import") (part "BAV199"))
    )
    (comp (ref "D22")
      (value "BAV199")
      (footprint "eagle-import:SOT23")
      (libsource (lib "eagle-import") (part "BAV199"))
    )
    (comp (ref "D23")
      (value "BAV199")
      (footprint "eagle-import:SOT23")
      (libsource (lib "eagle-import") (part "BAV199"))
    )
    (comp (ref "IC1")
      (value "MCP6002")
      (footprint "eagle-import:SO8")
      (fields (field (name "MPN") "AD8599ARZ"))
      (libsource (lib "eagle-import") (part "AD8599R"))
    )
    (comp (ref "IC3")
      (value "TLC3704")
      (footprint "eagle-import:SO14")
      (libsource (lib "eagle-import") (part "TLC339D"))
    )
    (comp (ref "IC4")
      (value "TLC3704")
      (footprint "eagle-import:SO14")
      (libsource (lib "eagle-import") (part "TLC339D"))
    )
    (comp (ref "IC5")
      (value "TLC3704")
      (footprint "eagle-import:SO14")
      (libsource (lib "eagle-import") (part "TLC339D"))
    )
    (comp (ref "IC6")
      (value "TLC3704")
      (footprint "eagle-import:SO14")
      (libsource (lib "eagle-import") (part "TLC339D"))
    )
    (comp (ref "PL1")
      (value "555X-18H-NO-HOLES")
      (footprint "eagle-import:5569-18_NO_HOLES")
      (libsource (lib "eagle-import") (part "555X-18H-NO-HOLES"))
    )
    (comp (ref "R2")
      (value "10k")
      (footprint "eagle-import:R1206")
      (libsource (lib "eagle-import") (part "rcl@1_R-EU_R1206"))
    )
    (comp (ref "R3")
      (value "2k58")
      (footprint "eagle-import:R0603")
      (libsource (lib "eagle-import") (part "R-EU_R0603"))
    )
    (comp (ref "R4")
      (value "330k")
      (footprint "eagle-import:R0603")
      (libsource (lib "eagle-import") (part "R-EU_R0603"))
    )
    (comp (ref "R5")
      (value "3k3")
      (footprint "eagle-import:R0603")
      (libsource (lib "eagle-import") (part "R-EU_R0603"))
    )
    (comp (ref "R6")
      (value "10k")
      (footprint "eagle-import:R1206")
      (libsource (lib "eagle-import") (part "rcl@1_R-EU_R1206"))
    )
    (comp (ref "R7")
      (value "2k58")
      (footprint "eagle-import:R0603")
      (libsource (lib "eagle-import") (part "R-EU_R0603"))
    )
    (comp (ref "R8")
      (value "330k")
      (footprint "eagle-import:R0603")
      (libsource (lib "eagle-import") (part "R-EU_R0603"))
    )
    (comp (ref "R9")
      (value "3k3")
      (footprint "eagle-import:R0603")
      (libsource (lib "eagle-import") (part "R-EU_R0603"))
    )
    (comp (ref "R10")
      (value "10k")
      (footprint "eagle-import:R1206")
      (libsource (lib "eagle-import") (part "rcl@1_R-EU_R1206"))
    )
    (comp (ref "R11")
      (value "2k58")
      (footprint "eagle-import:R0603")
      (libsource (lib "eagle-import") (part "R-EU_R0603"))
    )
    (comp (ref "R18")
      (value "330k")
      (footprint "eagle-import:R0603")
      (libsource (lib "eagle-import") (part "R-EU_R0603"))
    )
    (comp (ref "R19")
      (value "3k3")
      (footprint "eagle-import:R0603")
      (libsource (lib "eagle-import") (part "R-EU_R0603"))
    )
    (comp (ref "R20")
      (value "10k")
      (footprint "eagle-import:R1206")
      (libsource (lib "eagle-import") (part "rcl@1_R-EU_R1206"))
    )
    (comp (ref "R21")
      (value "2k58")
      (footprint "eagle-import:R0603")
      (libsource (lib "eagle-import") (part "R-EU_R0603"))
    )
    (comp (ref "R22")
      (value "330k")
      (footprint "eagle-import:R0603")
      (libsource (lib "eagle-import") (part "R-EU_R0603"))
    )
    (comp (ref "R23")
      (value "3k3")
      (footprint "eagle-import:R0603")
      (libsource (lib "eagle-import") (part "R-EU_R0603"))
    )
    (comp (ref "R65")
      (value "10k")
      (footprint "eagle-import:R1206")
      (libsource (lib "eagle-import") (part "rcl@1_R-EU_R1206"))
    )
    (comp (ref "R66")
      (value "2k58")
      (footprint "eagle-import:R0603")
      (libsource (lib "eagle-import") (part "R-EU_R0603"))
    )
    (comp (ref "R67")
      (value "330k")
      (footprint "eagle-import:R0603")
      (libsource (lib "eagle-import") (part "R-EU_R0603"))
    )
    (comp (ref "R68")
      (value "0R")
      (footprint "eagle-import:R0603")
      (libsource (lib "eagle-import") (part "R-EU_R0603"))
    )
    (comp (ref "R69")
      (value "0R")
      (footprint "eagle-import:R0603")
      (libsource (lib "eagle-import") (part "R-EU_R0603"))
    )
    (comp (ref "R70")
      (value "0R")
      (footprint "eagle-import:R0603")
      (libsource (lib "eagle-import") (part "R-EU_R0603"))
    )
    (comp (ref "R71")
      (value "0R")
      (footprint "eagle-import:R0603")
      (libsource (lib "eagle-import") (part "R-EU_R0603"))
    )
    (comp (ref "R72")
      (value "0R")
      (footprint "eagle-import:R0603")
      (libsource (lib "eagle-import") (part "R-EU_R0603"))
    )
    (comp (ref "R73")
      (value "0R")
      (footprint "eagle-import:R0603")
      (libsource (lib "eagle-import") (part "R-EU_R0603"))
    )
    (comp (ref "R87")
      (value "3k3")
      (footprint "eagle-import:R0603")
      (libsource (lib "eagle-import") (part "R-EU_R0603"))
    )
    (comp (ref "R88")
      (value "10k")
      (footprint "eagle-import:R1206")
      (libsource (lib "eagle-import") (part "rcl@1_R-EU_R1206"))
    )
    (comp (ref "R89")
      (value "2k58")
      (footprint "eagle-import:R0603")
      (libsource (lib "eagle-import") (part "R-EU_R0603"))
    )
    (comp (ref "R90")
      (value "330k")
      (footprint "eagle-import:R0603")
      (libsource (lib "eagle-import") (part "R-EU_R0603"))
    )
    (comp (ref "R91")
      (value "3k3")
      (footprint "eagle-import:R0603")
      (libsource (lib "eagle-import") (part "R-EU_R0603"))
    )
    (comp (ref "R92")
      (value "10k")
      (footprint "eagle-import:R1206")
      (libsource (lib "eagle-import") (part "rcl@1_R-EU_R1206"))
    )
    (comp (ref "R93")
      (value "2k58")
      (footprint "eagle-import:R0603")
      (libsource (lib "eagle-import") (part "R-EU_R0603"))
    )
    (comp (ref "R94")
      (value "330k")
      (footprint "eagle-import:R0603")
      (libsource (lib "eagle-import") (part "R-EU_R0603"))
    )
    (comp (ref "R95")
      (value "3k3")
      (footprint "eagle-import:R0603")
      (libsource (lib "eagle-import") (part "R-EU_R0603"))
    )
    (comp (ref "R96")
      (value "10k")
      (footprint "eagle-import:R1206")
      (libsource (lib "eagle-import") (part "rcl@1_R-EU_R1206"))
    )
    (comp (ref "R97")
      (value "2k58")
      (footprint "eagle-import:R0603")
      (libsource (lib "eagle-import") (part "R-EU_R0603"))
    )
    (comp (ref "R98")
      (value "330k")
      (footprint "eagle-import:R0603")
      (libsource (lib "eagle-import") (part "R-EU_R0603"))
    )
    (comp (ref "R99")
      (value "3k3")
      (footprint "eagle-import:R0603")
      (libsource (lib "eagle-import") (part "R-EU_R0603"))
    )
    (comp (ref "R100")
      (value "0R")
      (footprint "eagle-import:R0603")
      (libsource (lib "eagle-import") (part "R-EU_R0603"))
    )
    (comp (ref "R101")
      (value "0R")
      (footprint "eagle-import:R0603")
      (libsource (lib "eagle-import") (part "R-EU_R0603"))
    )
    (comp (ref "R102")
      (value "0R")
      (footprint "eagle-import:R0603")
      (libsource (lib "eagle-import") (part "R-EU_R0603"))
    )
    (comp (ref "R103")
      (value "0R")
      (footprint "eagle-import:R0603")
      (libsource (lib "eagle-import") (part "R-EU_R0603"))
    )
    (comp (ref "R104")
      (value "0R")
      (footprint "eagle-import:R0603")
      (libsource (lib "eagle-import") (part "R-EU_R0603"))
    )
    (comp (ref "R106")
      (value "10k")
      (footprint "eagle-import:R1206")
      (libsource (lib "eagle-import") (part "rcl@1_R-EU_R1206"))
    )
    (comp (ref "R107")
      (value "2k58")
      (footprint "eagle-import:R0603")
      (libsource (lib "eagle-import") (part "R-EU_R0603"))
    )
    (comp (ref "R108")
      (value "330k")
      (footprint "eagle-import:R0603")
      (libsource (lib "eagle-import") (part "R-EU_R0603"))
    )
    (comp (ref "R109")
      (value "3k3")
      (footprint "eagle-import:R0603")
      (libsource (lib "eagle-import") (part "R-EU_R0603"))
    )
    (comp (ref "R110")
      (value "10k")
      (footprint "eagle-import:R1206")
      (libsource (lib "eagle-import") (part "rcl@1_R-EU_R1206"))
    )
    (comp (ref "R111")
      (value "2k58")
      (footprint "eagle-import:R0603")
      (libsource (lib "eagle-import") (part "R-EU_R0603"))
    )
    (comp (ref "R112")
      (value "330k")
      (footprint "eagle-import:R0603")
      (libsource (lib "eagle-import") (part "R-EU_R0603"))
    )
    (comp (ref "R113")
      (value "3k3")
      (footprint "eagle-import:R0603")
      (libsource (lib "eagle-import") (part "R-EU_R0603"))
    )
    (comp (ref "R114")
      (value "10k")
      (footprint "eagle-import:R1206")
      (libsource (lib "eagle-import") (part "rcl@1_R-EU_R1206"))
    )
    (comp (ref "R115")
      (value "2k58")
      (footprint "eagle-import:R0603")
      (libsource (lib "eagle-import") (part "R-EU_R0603"))
    )
    (comp (ref "R116")
      (value "330k")
      (footprint "eagle-import:R0603")
      (libsource (lib "eagle-import") (part "R-EU_R0603"))
    )
    (comp (ref "R117")
      (value "3k3")
      (footprint "eagle-import:R0603")
      (libsource (lib "eagle-import") (part "R-EU_R0603"))
    )
    (comp (ref "R118")
      (value "10k")
      (footprint "eagle-import:R1206")
      (libsource (lib "eagle-import") (part "rcl@1_R-EU_R1206"))
    )
    (comp (ref "R119")
      (value "2k58")
      (footprint "eagle-import:R0603")
      (libsource (lib "eagle-import") (part "R-EU_R0603"))
    )
    (comp (ref "R120")
      (value "330k")
      (footprint "eagle-import:R0603")
      (libsource (lib "eagle-import") (part "R-EU_R0603"))
    )
    (comp (ref "R121")
      (value "3k3")
      (footprint "eagle-import:R0603")
      (libsource (lib "eagle-import") (part "R-EU_R0603"))
    )
    (comp (ref "R122")
      (value "0R")
      (footprint "eagle-import:R0603")
      (libsource (lib "eagle-import") (part "R-EU_R0603"))
    )
    (comp (ref "R123")
      (value "0R")
      (footprint "eagle-import:R0603")
      (libsource (lib "eagle-import") (part "R-EU_R0603"))
    )
    (comp (ref "R124")
      (value "0R")
      (footprint "eagle-import:R0603")
      (libsource (lib "eagle-import") (part "R-EU_R0603"))
    )
    (comp (ref "R125")
      (value "0R")
      (footprint "eagle-import:R0603")
      (libsource (lib "eagle-import") (part "R-EU_R0603"))
    )
    (comp (ref "R128")
      (value "10k")
      (footprint "eagle-import:R1206")
      (libsource (lib "eagle-import") (part "rcl@1_R-EU_R1206"))
    )
    (comp (ref "R129")
      (value "2k58")
      (footprint "eagle-import:R0603")
      (libsource (lib "eagle-import") (part "R-EU_R0603"))
    )
    (comp (ref "R130")
      (value "330k")
      (footprint "eagle-import:R0603")
      (libsource (lib "eagle-import") (part "R-EU_R0603"))
    )
    (comp (ref "R131")
      (value "3k3")
      (footprint "eagle-import:R0603")
      (libsource (lib "eagle-import") (part "R-EU_R0603"))
    )
    (comp (ref "R132")
      (value "10k")
      (footprint "eagle-import:R1206")
      (libsource (lib "eagle-import") (part "rcl@1_R-EU_R1206"))
    )
    (comp (ref "R133")
      (value "2k58")
      (footprint "eagle-import:R0603")
      (libsource (lib "eagle-import") (part "R-EU_R0603"))
    )
    (comp (ref "R134")
      (value "330k")
      (footprint "eagle-import:R0603")
      (libsource (lib "eagle-import") (part "R-EU_R0603"))
    )
    (comp (ref "R135")
      (value "3k3")
      (footprint "eagle-import:R0603")
      (libsource (lib "eagle-import") (part "R-EU_R0603"))
    )
    (comp (ref "R136")
      (value "10k")
      (footprint "eagle-import:R1206")
      (libsource (lib "eagle-import") (part "rcl@1_R-EU_R1206"))
    )
    (comp (ref "R137")
      (value "2k58")
      (footprint "eagle-import:R0603")
      (libsource (lib "eagle-import") (part "R-EU_R0603"))
    )
    (comp (ref "R138")
      (value "330k")
      (footprint "eagle-import:R0603")
      (libsource (lib "eagle-import") (part "R-EU_R0603"))
    )
    (comp (ref "R139")
      (value "3k3")
      (footprint "eagle-import:R0603")
      (libsource (lib "eagle-import") (part "R-EU_R0603"))
    )
    (comp (ref "R140")
      (value "10k")
      (footprint "eagle-import:R1206")
      (libsource (lib "eagle-import") (part "rcl@1_R-EU_R1206"))
    )
    (comp (ref "R141")
      (value "2k58")
      (footprint "eagle-import:R0603")
      (libsource (lib "eagle-import") (part "R-EU_R0603"))
    )
    (comp (ref "R142")
      (value "330k")
      (footprint "eagle-import:R0603")
      (libsource (lib "eagle-import") (part "R-EU_R0603"))
    )
    (comp (ref "R143")
      (value "3k3")
      (footprint "eagle-import:R0603")
      (libsource (lib "eagle-import") (part "R-EU_R0603"))
    )
    (comp (ref "R144")
      (value "0R")
      (footprint "eagle-import:R0603")
      (libsource (lib "eagle-import") (part "R-EU_R0603"))
    )
    (comp (ref "R145")
      (value "0R")
      (footprint "eagle-import:R0603")
      (libsource (lib "eagle-import") (part "R-EU_R0603"))
    )
    (comp (ref "R146")
      (value "0R")
      (footprint "eagle-import:R0603")
      (libsource (lib "eagle-import") (part "R-EU_R0603"))
    )
    (comp (ref "R147")
      (value "0R")
      (footprint "eagle-import:R0603")
      (libsource (lib "eagle-import") (part "R-EU_R0603"))
    )
    (comp (ref "R169")
      (value "NF")
      (footprint "eagle-import:R0603")
      (libsource (lib "eagle-import") (part "R-EU_R0603"))
    )
    (comp (ref "R186")
      (value "0R")
      (footprint "eagle-import:R0603")
      (libsource (lib "eagle-import") (part "R-EU_R0603"))
    )
    (comp (ref "R187")
      (value "NF")
      (footprint "eagle-import:R0603")
      (libsource (lib "eagle-import") (part "R-EU_R0603"))
    )
    (comp (ref "C17")
      (value "100n")
      (footprint "eagle-import:C0805")
      (libsource (lib "eagle-import") (part "rcl_C-EUC0805"))
    )
    (comp (ref "C68")
      (value "100n")
      (footprint "eagle-import:C0805")
      (libsource (lib "eagle-import") (part "rcl_C-EUC0805"))
    )
    (comp (ref "D1")
      (value "SM712-02HTG")
      (footprint "eagle-import:SOT23-BEC")
      (libsource (lib "eagle-import") (part "SM712-02HTG"))
    )
    (comp (ref "LED5")
      (value "1206")
      (footprint "eagle-import:CHIPLED_1206")
      (libsource (lib "eagle-import") (part "LEDCHIPLED_1206"))
    )
    (comp (ref "LED6")
      (value "1206")
      (footprint "eagle-import:CHIPLED_1206")
      (libsource (lib "eagle-import") (part "LEDCHIPLED_1206"))
    )
    (comp (ref "R13")
      (value "10R")
      (footprint "eagle-import:R0603")
      (libsource (lib "eagle-import") (part "R-EU_R0603"))
    )
    (comp (ref "R14")
      (value "10R")
      (footprint "eagle-import:R0603")
      (libsource (lib "eagle-import") (part "R-EU_R0603"))
    )
    (comp (ref "R15")
      (value "1k")
      (footprint "eagle-import:R0603")
      (libsource (lib "eagle-import") (part "R-EU_R0603"))
    )
    (comp (ref "R16")
      (value "1k")
      (footprint "eagle-import:R0603")
      (libsource (lib "eagle-import") (part "R-EU_R0603"))
    )
    (comp (ref "R17")
      (value "130R")
      (footprint "eagle-import:R1206")
      (libsource (lib "eagle-import") (part "R-EU_R1206"))
    )
    (comp (ref "R30")
      (value "1k5")
      (footprint "eagle-import:R1206")
      (libsource (lib "eagle-import") (part "R-EU_R1206"))
    )
    (comp (ref "R31")
      (value "1k5")
      (footprint "eagle-import:R1206")
      (libsource (lib "eagle-import") (part "R-EU_R1206"))
    )
    (comp (ref "R32")
      (value "10k")
      (footprint "eagle-import:R0603")
      (libsource (lib "eagle-import") (part "R-EU_R0603"))
    )
    (comp (ref "R49")
      (value "0R1")
      (footprint "eagle-import:R1206")
      (libsource (lib "eagle-import") (part "R-EU_R1206"))
    )
    (comp (ref "S1")
      (value "SWS003")
      (footprint "eagle-import:SMS-003")
      (libsource (lib "eagle-import") (part "SWS003"))
    )
    (comp (ref "U30")
      (value "ISO3082")
      (footprint "eagle-import:SO-16DW")
      (libsource (lib "eagle-import") (part "ISO3082"))
    )
    (comp (ref "C61")
      (value "100n")
      (footprint "eagle-import:C0805")
      (libsource (lib "eagle-import") (part "rcl_C-EUC0805"))
    )
    (comp (ref "C62")
      (value "100n")
      (footprint "eagle-import:C0805")
      (libsource (lib "eagle-import") (part "rcl_C-EUC0805"))
    )
    (comp (ref "IC7")
      (value "74HCT595D")
      (footprint "eagle-import:SO16")
      (libsource (lib "eagle-import") (part "74595DHC"))
    )
    (comp (ref "IC8")
      (value "74HTC595D")
      (footprint "eagle-import:SO16")
      (libsource (lib "eagle-import") (part "74595DHC"))
    )
    (comp (ref "R188")
      (value "10k")
      (footprint "eagle-import:R0603")
      (libsource (lib "eagle-import") (part "rcl@1_R-EU_R0603"))
    )
    (comp (ref "R189")
      (value "10k")
      (footprint "eagle-import:R0603")
      (libsource (lib "eagle-import") (part "rcl@1_R-EU_R0603"))
    )
    (comp (ref "R190")
      (value "10k")
      (footprint "eagle-import:R0603")
      (libsource (lib "eagle-import") (part "rcl@1_R-EU_R0603"))
    )
    (comp (ref "R191")
      (value "10k")
      (footprint "eagle-import:R0603")
      (libsource (lib "eagle-import") (part "rcl@1_R-EU_R0603"))
    )
    (comp (ref "C7")
      (value "100n")
      (footprint "eagle-import:C0805")
      (libsource (lib "eagle-import") (part "rcl_C-EUC0805"))
    )
    (comp (ref "C8")
      (value "100u")
      (footprint "eagle-import:153CLV-0605")
      (libsource (lib "eagle-import") (part "rcl@1_CPOL-EU153CLV-0605"))
    )
    (comp (ref "C12")
      (value "100n")
      (footprint "eagle-import:C0805")
      (libsource (lib "eagle-import") (part "rcl_C-EUC0805"))
    )
    (comp (ref "C13")
      (value "100n")
      (footprint "eagle-import:C0805")
      (libsource (lib "eagle-import") (part "rcl_C-EUC0805"))
    )
    (comp (ref "C18")
      (value "10u")
      (footprint "eagle-import:C1206")
      (libsource (lib "eagle-import") (part "C-EUC1206"))
    )
    (comp (ref "C19")
      (value "10u")
      (footprint "eagle-import:C1206")
      (libsource (lib "eagle-import") (part "C-EUC1206"))
    )
    (comp (ref "C20")
      (value "100n")
      (footprint "eagle-import:C1206")
      (libsource (lib "eagle-import") (part "rcl_C-EUC1206"))
    )
    (comp (ref "C21")
      (value "47u")
      (footprint "eagle-import:E3,5-8")
      (libsource (lib "eagle-import") (part "CPOL-EUE3.5-8"))
    )
    (comp (ref "C22")
      (value "47u")
      (footprint "eagle-import:150CLZ-1014")
      (libsource (lib "eagle-import") (part "CPOL-EU150CLZ-1014"))
    )
    (comp (ref "C23")
      (value "100n")
      (footprint "eagle-import:C0805")
      (libsource (lib "eagle-import") (part "rcl_C-EUC0805"))
    )
    (comp (ref "C27")
      (value "100u")
      (footprint "eagle-import:153CLV-0605")
      (libsource (lib "eagle-import") (part "rcl@1_CPOL-EU153CLV-0605"))
    )
    (comp (ref "D2")
      (value "SMBJ26A")
      (footprint "eagle-import:SMB")
      (libsource (lib "eagle-import") (part "SMBJ26A"))
    )
    (comp (ref "GND")
      (value "MA03-1")
      (footprint "eagle-import:MA03-1")
      (libsource (lib "eagle-import") (part "MA03-1"))
    )
    (comp (ref "IC2")
      (value "LD1117")
      (footprint "eagle-import:SOT223")
      (libsource (lib "eagle-import") (part "LM1117"))
    )
    (comp (ref "K2")
      (value "09 03 364 6921")
      (footprint "eagle-import:VG64P")
      (libsource (lib "eagle-import") (part "VG64P"))
    )
    (comp (ref "L2")
      (value "LQM31PN1R0M00L")
      (footprint "eagle-import:R1206")
      (libsource (lib "eagle-import") (part "L-US"))
    )
    (comp (ref "L5")
      (value "1008PS-392KLB")
      (footprint "eagle-import:L1812")
      (libsource (lib "eagle-import") (part "L-US?{colon}1L1812"))
    )
    (comp (ref "R1")
      (value "0R1")
      (footprint "eagle-import:R1206")
      (libsource (lib "eagle-import") (part "R-EU_R1206"))
    )
    (comp (ref "R74")
      (value "470R")
      (footprint "eagle-import:R1206")
      (libsource (lib "eagle-import") (part "R-EU_R1206"))
    )
    (comp (ref "R80")
      (value "0R1")
      (footprint "eagle-import:R1206")
      (libsource (lib "eagle-import") (part "R-EU_R1206"))
    )
    (comp (ref "U7")
      (value "IU2405SA")
      (footprint "eagle-import:IU2405SA")
      (libsource (lib "eagle-import") (part "IU2405SA"))
    )
    (comp (ref "U14")
      (value "R-78C5.0-0.5")
      (footprint "eagle-import:R-78E-0.5")
      (libsource (lib "eagle-import") (part "R-78E-0.5"))
    )
  )
  (nets
    (net (code "1") (name "+3V3") (class "Default")
      (node (ref "C13") (pin "1") (pinfunction "1_1") (pintype "passive"))
      (node (ref "C27") (pin "+") (pinfunction "+_+") (pintype "passive"))
      (node (ref "C31") (pin "1") (pinfunction "1_1") (pintype "passive"))
      (node (ref "C48") (pin "1") (pinfunction "1_1") (pintype "passive"))
      (node (ref "C49") (pin "1") (pinfunction "1_1") (pintype "passive"))
      (node (ref "C50") (pin "1") (pinfunction "1_1") (pintype "passive"))
      (node (ref "C65") (pin "1") (pinfunction "1_1") (pintype "passive"))
      (node (ref "C66") (pin "1") (pinfunction "1_1") (pintype "passive"))
      (node (ref "C67") (pin "1") (pinfunction "1_1") (pintype "passive"))
      (node (ref "C69") (pin "1") (pinfunction "1_1") (pintype "passive"))
      (node (ref "IC2") (pin "2") (pinfunction "OUT_2") (pintype "passive"))
      (node (ref "K1") (pin "1") (pinfunction "VCC_1") (pintype "bidirectional"))
      (node (ref "L1") (pin "1") (pinfunction "1_1") (pintype "passive"))
      (node (ref "LED5") (pin "A") (pinfunction "A_A") (pintype "passive"))
      (node (ref "LED6") (pin "A") (pinfunction "A_A") (pintype "passive"))
      (node (ref "R12") (pin "2") (pinfunction "2_2") (pintype "passive"))
      (node (ref "R49") (pin "2") (pinfunction "2_2") (pintype "passive"))
      (node (ref "R85") (pin "1") (pinfunction "1_1") (pintype "passive"))
      (node (ref "R86") (pin "1") (pinfunction "1_1") (pintype "passive"))
      (node (ref "U1") (pin "1") (pinfunction "VBAT_1") (pintype "bidirectional"))
      (node (ref "U1") (pin "19") (pinfunction "VDD_1_19") (pintype "power_in"))
      (node (ref "U1") (pin "32") (pinfunction "VDD_2_32") (pintype "power_in"))
      (node (ref "U1") (pin "48") (pinfunction "VDD_3_48") (pintype "power_in"))
      (node (ref "U1") (pin "64") (pinfunction "VDD_4_64") (pintype "power_in"))
    )
    (net (code "2") (name "+5V") (class "Default")
      (node (ref "C10") (pin "1") (pinfunction "1_1") (pintype "passive"))
      (node (ref "C15") (pin "1") (pinfunction "1_1") (pintype "passive"))
      (node (ref "C22") (pin "+") (pinfunction "+_+") (pintype "passive"))
      (node (ref "C23") (pin "1") (pinfunction "1_1") (pintype "passive"))
      (node (ref "C3") (pin "1") (pinfunction "1_1") (pintype "passive"))
      (node (ref "C33") (pin "1") (pinfunction "1_1") (pintype "passive"))
      (node (ref "C5") (pin "1") (pinfunction "1_1") (pintype "passive"))
      (node (ref "C59") (pin "1") (pinfunction "1_1") (pintype "passive"))
      (node (ref "C60") (pin "1") (pinfunction "1_1") (pintype "passive"))
      (node (ref "C61") (pin "1") (pinfunction "1_1") (pintype "passive"))
      (node (ref "C62") (pin "1") (pinfunction "1_1") (pintype "passive"))
      (node (ref "C9") (pin "1") (pinfunction "1_1") (pintype "passive"))
      (node (ref "D11") (pin "2") (pinfunction "C_2") (pintype "passive"))
      (node (ref "D13") (pin "2") (pinfunction "C_2") (pintype "passive"))
      (node (ref "D15") (pin "2") (pinfunction "C_2") (pintype "passive"))
      (node (ref "D16") (pin "2") (pinfunction "C_2") (pintype "passive"))
      (node (ref "D17") (pin "2") (pinfunction "C_2") (pintype "passive"))
      (node (ref "D18") (pin "2") (pinfunction "C_2") (pintype "passive"))
      (node (ref "D19") (pin "2") (pinfunction "C_2") (pintype "passive"))
      (node (ref "D20") (pin "2") (pinfunction "C_2") (pintype "passive"))
      (node (ref "D21") (pin "2") (pinfunction "C_2") (pintype "passive"))
      (node (ref "D22") (pin "2") (pinfunction "C_2") (pintype "passive"))
      (node (ref "D23") (pin "2") (pinfunction "C_2") (pintype "passive"))
      (node (ref "D3") (pin "2") (pinfunction "C_2") (pintype "passive"))
      (node (ref "D4") (pin "2") (pinfunction "C_2") (pintype "passive"))
      (node (ref "D5") (pin "2") (pinfunction "C_2") (pintype "passive"))
      (node (ref "D6") (pin "2") (pinfunction "C_2") (pintype "passive"))
      (node (ref "D9") (pin "2") (pinfunction "C_2") (pintype "passive"))
      (node (ref "IC1") (pin "8") (pinfunction "V+_8") (pintype "power_in"))
      (node (ref "IC3") (pin "3") (pinfunction "V+_3") (pintype "power_in"))
      (node (ref "IC4") (pin "3") (pinfunction "V+_3") (pintype "power_in"))
      (node (ref "IC5") (pin "3") (pinfunction "V+_3") (pintype "power_in"))
      (node (ref "IC6") (pin "3") (pinfunction "V+_3") (pintype "power_in"))
      (node (ref "IC7") (pin "10") (pinfunction "SCL_10") (pintype "input"))
      (node (ref "IC7") (pin "16") (pinfunction "VCC_16") (pintype "power_in"))
      (node (ref "IC8") (pin "10") (pinfunction "SCL_10") (pintype "input"))
      (node (ref "IC8") (pin "16") (pinfunction "VCC_16") (pintype "power_in"))
      (node (ref "L4") (pin "1") (pinfunction "1_1") (pintype "passive"))
      (node (ref "R1") (pin "2") (pinfunction "2_2") (pintype "passive"))
      (node (ref "R188") (pin "2") (pinfunction "2_2") (pintype "passive"))
      (node (ref "R191") (pin "2") (pinfunction "2_2") (pintype "passive"))
      (node (ref "R80") (pin "1") (pinfunction "1_1") (pintype "passive"))
      (node (ref "U10") (pin "1") (pinfunction "A_1") (pintype "passive"))
      (node (ref "U10") (pin "3") (pinfunction "A_3") (pintype "passive"))
      (node (ref "U11") (pin "1") (pinfunction "A_1") (pintype "passive"))
      (node (ref "U11") (pin "3") (pinfunction "A_3") (pintype "passive"))
      (node (ref "U15") (pin "6") (pinfunction "VIN_6") (pintype "power_in"))
      (node (ref "U20") (pin "1") (pinfunction "A_1") (pintype "passive"))
      (node (ref "U20") (pin "3") (pinfunction "A_3") (pintype "passive"))
      (node (ref "U23") (pin "1") (pinfunction "A_1") (pintype "passive"))
      (node (ref "U23") (pin "3") (pinfunction "A_3") (pintype "passive"))
      (node (ref "U26") (pin "1") (pinfunction "A_1") (pintype "passive"))
      (node (ref "U26") (pin "3") (pinfunction "A_3") (pintype "passive"))
      (node (ref "U29") (pin "1") (pinfunction "A_1") (pintype "passive"))
      (node (ref "U29") (pin "3") (pinfunction "A_3") (pintype "passive"))
    )
    (net (code "3") (name "+5V{slash}1") (class "Default")
      (node (ref "C68") (pin "1") (pinfunction "1_1") (pintype "passive"))
      (node (ref "C7") (pin "1") (pinfunction "1_1") (pintype "passive"))
      (node (ref "C8") (pin "+") (pinfunction "+_+") (pintype "passive"))
      (node (ref "R15") (pin "2") (pinfunction "2_2") (pintype "passive"))
      (node (ref "R74") (pin "2") (pinfunction "2_2") (pintype "passive"))
      (node (ref "U14") (pin "3") (pinfunction "+VOUT_3") (pintype "bidirectional"))
      (node (ref "U30") (pin "16") (pinfunction "VCC2_16") (pintype "input"))
    )
    (net (code "4") (name "+24V") (class "Default")
      (node (ref "C18") (pin "1") (pinfunction "1_1") (pintype "passive"))
      (node (ref "C20") (pin "1") (pinfunction "1_1") (pintype "passive"))
      (node (ref "C21") (pin "+") (pinfunction "+_+") (pintype "passive"))
      (node (ref "D2") (pin "C") (pinfunction "C_C") (pintype "passive"))
      (node (ref "L2") (pin "2") (pinfunction "2_2") (pintype "passive"))
      (node (ref "L5") (pin "1") (pinfunction "1_1") (pintype "passive"))
      (node (ref "U7") (pin "VIN+") (pinfunction "+VIN_VIN+") (pintype "bidirectional"))
    )
    (net (code "5") (name "+24V_IN") (class "Default")
      (node (ref "K2") (pin "A30") (pinfunction "A30_A30") (pintype "passive"))
      (node (ref "K2") (pin "A31") (pinfunction "A31_A31") (pintype "passive"))
      (node (ref "K2") (pin "A32") (pinfunction "A32_A32") (pintype "passive"))
      (node (ref "K2") (pin "C30") (pinfunction "C30_C30") (pintype "passive"))
      (node (ref "K2") (pin "C31") (pinfunction "C31_C31") (pintype "passive"))
      (node (ref "K2") (pin "C32") (pinfunction "C32_C32") (pintype "passive"))
      (node (ref "L2") (pin "1") (pinfunction "1_1") (pintype "passive"))
    )
    (net (code "6") (name "ADC1_IN1") (class "Default")
      (node (ref "R81") (pin "1") (pinfunction "1_1") (pintype "passive"))
      (node (ref "R82") (pin "1") (pinfunction "1_1") (pintype "passive"))
      (node (ref "R85") (pin "2") (pinfunction "2_2") (pintype "passive"))
      (node (ref "U1") (pin "15") (pinfunction "PA1_15") (pintype "bidirectional"))
    )
    (net (code "7") (name "ADC1_IN3") (class "Default")
      (node (ref "R83") (pin "1") (pinfunction "1_1") (pintype "passive"))
      (node (ref "R84") (pin "1") (pinfunction "1_1") (pintype "passive"))
      (node (ref "R86") (pin "2") (pinfunction "2_2") (pintype "passive"))
      (node (ref "U1") (pin "17") (pinfunction "PA3_17") (pintype "bidirectional"))
    )
    (net (code "8") (name "ADC1_IN9") (class "Default")
      (node (ref "C41") (pin "1") (pinfunction "1_1") (pintype "passive"))
      (node (ref "R63") (pin "1") (pinfunction "1_1") (pintype "passive"))
      (node (ref "R64") (pin "2") (pinfunction "2_2") (pintype "passive"))
      (node (ref "U1") (pin "27") (pinfunction "PB1_27") (pintype "bidirectional"))
    )
    (net (code "9") (name "AUX_1") (class "Default")
      (node (ref "K2") (pin "A2") (pinfunction "A2_A2") (pintype "passive"))
    )
    (net (code "10") (name "AUX_2") (class "Default")
      (node (ref "K2") (pin "C2") (pinfunction "C2_C2") (pintype "passive"))
    )
    (net (code "11") (name "AUX_3") (class "Default")
      (node (ref "K2") (pin "A4") (pinfunction "A4_A4") (pintype "passive"))
    )
    (net (code "12") (name "AUX_4") (class "Default")
      (node (ref "K2") (pin "C4") (pinfunction "C4_C4") (pintype "passive"))
    )
    (net (code "13") (name "AUX_5") (class "Default")
      (node (ref "K2") (pin "A5") (pinfunction "A5_A5") (pintype "passive"))
    )
    (net (code "14") (name "AUX_6") (class "Default")
      (node (ref "K2") (pin "C5") (pinfunction "C5_C5") (pintype "passive"))
    )
    (net (code "15") (name "AUX_7") (class "Default")
      (node (ref "K2") (pin "A6") (pinfunction "A6_A6") (pintype "passive"))
    )
    (net (code "16") (name "AUX_8") (class "Default")
      (node (ref "K2") (pin "C6") (pinfunction "C6_C6") (pintype "passive"))
    )
    (net (code "17") (name "AUX_9") (class "Default")
      (node (ref "K2") (pin "A7") (pinfunction "A7_A7") (pintype "passive"))
    )
    (net (code "18") (name "AUX_10") (class "Default")
      (node (ref "K2") (pin "C7") (pinfunction "C7_C7") (pintype "passive"))
    )
    (net (code "19") (name "AUX_11") (class "Default")
      (node (ref "K2") (pin "A8") (pinfunction "A8_A8") (pintype "passive"))
    )
    (net (code "20") (name "AUX_12") (class "Default")
      (node (ref "K2") (pin "C8") (pinfunction "C8_C8") (pintype "passive"))
    )
    (net (code "21") (name "AUX_13") (class "Default")
      (node (ref "K2") (pin "A9") (pinfunction "A9_A9") (pintype "passive"))
    )
    (net (code "22") (name "AUX_14") (class "Default")
      (node (ref "K2") (pin "C9") (pinfunction "C9_C9") (pintype "passive"))
    )
    (net (code "23") (name "AUX_15") (class "Default")
      (node (ref "K2") (pin "A10") (pinfunction "A10_A10") (pintype "passive"))
    )
    (net (code "24") (name "AUX_16") (class "Default")
      (node (ref "K2") (pin "C10") (pinfunction "C10_C10") (pintype "passive"))
    )
    (net (code "25") (name "AUX_17") (class "Default")
      (node (ref "K2") (pin "A11") (pinfunction "A11_A11") (pintype "passive"))
    )
    (net (code "26") (name "AUX_18") (class "Default")
      (node (ref "K2") (pin "C11") (pinfunction "C11_C11") (pintype "passive"))
    )
    (net (code "27") (name "AUX_19") (class "Default")
      (node (ref "K2") (pin "A12") (pinfunction "A12_A12") (pintype "passive"))
    )
    (net (code "28") (name "AUX_20") (class "Default")
      (node (ref "K2") (pin "C12") (pinfunction "C12_C12") (pintype "passive"))
    )
    (net (code "29") (name "AUX_21") (class "Default")
      (node (ref "K2") (pin "A13") (pinfunction "A13_A13") (pintype "passive"))
    )
    (net (code "30") (name "AUX_22") (class "Default")
      (node (ref "K2") (pin "C13") (pinfunction "C13_C13") (pintype "passive"))
    )
    (net (code "31") (name "AUX_23") (class "Default")
      (node (ref "K2") (pin "A14") (pinfunction "A14_A14") (pintype "passive"))
    )
    (net (code "32") (name "AUX_24") (class "Default")
      (node (ref "K2") (pin "C14") (pinfunction "C14_C14") (pintype "passive"))
    )
    (net (code "33") (name "AUX_25") (class "Default")
      (node (ref "K2") (pin "A15") (pinfunction "A15_A15") (pintype "passive"))
    )
    (net (code "34") (name "AUX_26") (class "Default")
      (node (ref "K2") (pin "C15") (pinfunction "C15_C15") (pintype "passive"))
    )
    (net (code "35") (name "AUX_27") (class "Default")
      (node (ref "K2") (pin "A16") (pinfunction "A16_A16") (pintype "passive"))
    )
    (net (code "36") (name "AUX_28") (class "Default")
      (node (ref "K2") (pin "C16") (pinfunction "C16_C16") (pintype "passive"))
    )
    (net (code "37") (name "AUX_29") (class "Default")
      (node (ref "K2") (pin "A17") (pinfunction "A17_A17") (pintype "passive"))
    )
    (net (code "38") (name "AUX_30") (class "Default")
      (node (ref "K2") (pin "C17") (pinfunction "C17_C17") (pintype "passive"))
    )
    (net (code "39") (name "AUX_31") (class "Default")
      (node (ref "K2") (pin "A18") (pinfunction "A18_A18") (pintype "passive"))
    )
    (net (code "40") (name "AUX_32") (class "Default")
      (node (ref "K2") (pin "C18") (pinfunction "C18_C18") (pintype "passive"))
    )
    (net (code "41") (name "AUX_33") (class "Default")
      (node (ref "K2") (pin "A19") (pinfunction "A19_A19") (pintype "passive"))
    )
    (net (code "42") (name "AUX_34") (class "Default")
      (node (ref "K2") (pin "C19") (pinfunction "C19_C19") (pintype "passive"))
    )
    (net (code "43") (name "AUX_35") (class "Default")
      (node (ref "K2") (pin "A20") (pinfunction "A20_A20") (pintype "passive"))
    )
    (net (code "44") (name "AUX_36") (class "Default")
      (node (ref "K2") (pin "C20") (pinfunction "C20_C20") (pintype "passive"))
    )
    (net (code "45") (name "AUX_37") (class "Default")
      (node (ref "K2") (pin "A21") (pinfunction "A21_A21") (pintype "passive"))
    )
    (net (code "46") (name "AUX_38") (class "Default")
      (node (ref "K2") (pin "C21") (pinfunction "C21_C21") (pintype "passive"))
    )
    (net (code "47") (name "AUX_39") (class "Default")
      (node (ref "K2") (pin "A22") (pinfunction "A22_A22") (pintype "passive"))
    )
    (net (code "48") (name "AUX_40") (class "Default")
      (node (ref "K2") (pin "C22") (pinfunction "C22_C22") (pintype "passive"))
    )
    (net (code "49") (name "AUX_41") (class "Default")
      (node (ref "K2") (pin "A23") (pinfunction "A23_A23") (pintype "passive"))
    )
    (net (code "50") (name "AUX_42") (class "Default")
      (node (ref "K2") (pin "C23") (pinfunction "C23_C23") (pintype "passive"))
    )
    (net (code "51") (name "AUX_43") (class "Default")
      (node (ref "K2") (pin "A24") (pinfunction "A24_A24") (pintype "passive"))
    )
    (net (code "52") (name "AUX_44") (class "Default")
      (node (ref "K2") (pin "C24") (pinfunction "C24_C24") (pintype "passive"))
    )
    (net (code "53") (name "AUX_45") (class "Default")
      (node (ref "K2") (pin "A25") (pinfunction "A25_A25") (pintype "passive"))
    )
    (net (code "54") (name "AUX_46") (class "Default")
      (node (ref "K2") (pin "C25") (pinfunction "C25_C25") (pintype "passive"))
    )
    (net (code "55") (name "AUX_47") (class "Default")
      (node (ref "K2") (pin "A26") (pinfunction "A26_A26") (pintype "passive"))
    )
    (net (code "56") (name "AUX_48") (class "Default")
      (node (ref "K2") (pin "C26") (pinfunction "C26_C26") (pintype "passive"))
    )
    (net (code "57") (name "DAC_OUT1") (class "Default")
      (node (ref "R72") (pin "1") (pinfunction "1_1") (pintype "passive"))
      (node (ref "U1") (pin "20") (pinfunction "PA4_20") (pintype "bidirectional"))
    )
    (net (code "58") (name "DAC_OUT2") (class "Default")
      (node (ref "R73") (pin "1") (pinfunction "1_1") (pintype "passive"))
      (node (ref "U1") (pin "21") (pinfunction "PA5_21") (pintype "bidirectional"))
    )
    (net (code "59") (name "DCDC_SET1") (class "Default")
      (node (ref "R42") (pin "1") (pinfunction "1_1") (pintype "passive"))
      (node (ref "U1") (pin "36") (pinfunction "PB15_36") (pintype "bidirectional"))
    )
    (net (code "60") (name "DCDC_SET2") (class "Default")
      (node (ref "R43") (pin "1") (pinfunction "1_1") (pintype "passive"))
      (node (ref "U1") (pin "34") (pinfunction "PB13_34") (pintype "bidirectional"))
    )
    (net (code "61") (name "DCDC_SET3") (class "Default")
      (node (ref "R44") (pin "1") (pinfunction "1_1") (pintype "passive"))
      (node (ref "U1") (pin "33") (pinfunction "PB12_33") (pintype "bidirectional"))
    )
    (net (code "62") (name "DCDC_SET4") (class "Default")
      (node (ref "R45") (pin "1") (pinfunction "1_1") (pintype "passive"))
      (node (ref "U1") (pin "29") (pinfunction "PB10_29") (pintype "bidirectional"))
    )
    (net (code "63") (name "DCDC_SET5") (class "Default")
      (node (ref "R77") (pin "1") (pinfunction "1_1") (pintype "passive"))
      (node (ref "U1") (pin "28") (pinfunction "PB2_28") (pintype "bidirectional"))
    )
    (net (code "64") (name "GND") (class "Default")
      (node (ref "C1") (pin "2") (pinfunction "2_2") (pintype "passive"))
      (node (ref "C10") (pin "2") (pinfunction "2_2") (pintype "passive"))
      (node (ref "C11") (pin "2") (pinfunction "2_2") (pintype "passive"))
      (node (ref "C12") (pin "2") (pinfunction "2_2") (pintype "passive"))
      (node (ref "C13") (pin "2") (pinfunction "2_2") (pintype "passive"))
      (node (ref "C14") (pin "2") (pinfunction "2_2") (pintype "passive"))
      (node (ref "C15") (pin "2") (pinfunction "2_2") (pintype "passive"))
      (node (ref "C16") (pin "2") (pinfunction "2_2") (pintype "passive"))
      (node (ref "C17") (pin "2") (pinfunction "2_2") (pintype "passive"))
      (node (ref "C2") (pin "2") (pinfunction "2_2") (pintype "passive"))
      (node (ref "C22") (pin "-") (pinfunction "-_-") (pintype "passive"))
      (node (ref "C23") (pin "2") (pinfunction "2_2") (pintype "passive"))
      (node (ref "C24") (pin "2") (pinfunction "2_2") (pintype "passive"))
      (node (ref "C25") (pin "2") (pinfunction "2_2") (pintype "passive"))
      (node (ref "C26") (pin "1") (pinfunction "1_1") (pintype "passive"))
      (node (ref "C27") (pin "-") (pinfunction "-_-") (pintype "passive"))
      (node (ref "C28") (pin "2") (pinfunction "2_2") (pintype "passive"))
      (node (ref "C3") (pin "2") (pinfunction "2_2") (pintype "passive"))
      (node (ref "C31") (pin "2") (pinfunction "2_2") (pintype "passive"))
      (node (ref "C32") (pin "2") (pinfunction "2_2") (pintype "passive"))
      (node (ref "C33") (pin "2") (pinfunction "2_2") (pintype "passive"))
      (node (ref "C34") (pin "2") (pinfunction "2_2") (pintype "passive"))
      (node (ref "C35") (pin "2") (pinfunction "2_2") (pintype "passive"))
      (node (ref "C36") (pin "1") (pinfunction "1_1") (pintype "passive"))
      (node (ref "C37") (pin "1") (pinfunction "1_1") (pintype "passive"))
      (node (ref "C38") (pin "2") (pinfunction "2_2") (pintype "passive"))
      (node (ref "C39") (pin "1") (pinfunction "1_1") (pintype "passive"))
      (node (ref "C40") (pin "2") (pinfunction "2_2") (pintype "passive"))
      (node (ref "C41") (pin "2") (pinfunction "2_2") (pintype "passive"))
      (node (ref "C42") (pin "2") (pinfunction "2_2") (pintype "passive"))
      (node (ref "C43") (pin "2") (pinfunction "2_2") (pintype "passive"))
      (node (ref "C44") (pin "1") (pinfunction "1_1") (pintype "passive"))
      (node (ref "C45") (pin "2") (pinfunction "2_2") (pintype "passive"))
      (node (ref "C46") (pin "2") (pinfunction "2_2") (pintype "passive"))
      (node (ref "C47") (pin "1") (pinfunction "1_1") (pintype "passive"))
      (node (ref "C48") (pin "2") (pinfunction "2_2") (pintype "passive"))
      (node (ref "C49") (pin "2") (pinfunction "2_2") (pintype "passive"))
      (node (ref "C5") (pin "2") (pinfunction "2_2") (pintype "passive"))
      (node (ref "C50") (pin "2") (pinfunction "2_2") (pintype "passive"))
      (node (ref "C51") (pin "2") (pinfunction "2_2") (pintype "passive"))
      (node (ref "C52") (pin "2") (pinfunction "2_2") (pintype "passive"))
      (node (ref "C53") (pin "2") (pinfunction "2_2") (pintype "passive"))
      (node (ref "C54") (pin "2") (pinfunction "2_2") (pintype "passive"))
      (node (ref "C55") (pin "2") (pinfunction "2_2") (pintype "passive"))
      (node (ref "C56") (pin "2") (pinfunction "2_2") (pintype "passive"))
      (node (ref "C57") (pin "2") (pinfunction "2_2") (pintype "passive"))
      (node (ref "C58") (pin "2") (pinfunction "2_2") (pintype "passive"))
      (node (ref "C59") (pin "2") (pinfunction "2_2") (pintype "passive"))
      (node (ref "C60") (pin "2") (pinfunction "2_2") (pintype "passive"))
      (node (ref "C61") (pin "2") (pinfunction "2_2") (pintype "passive"))
      (node (ref "C62") (pin "2") (pinfunction "2_2") (pintype "passive"))
      (node (ref "C63") (pin "2") (pinfunction "2_2") (pintype "passive"))
      (node (ref "C64") (pin "2") (pinfunction "2_2") (pintype "passive"))
      (node (ref "C65") (pin "2") (pinfunction "2_2") (pintype "passive"))
      (node (ref "C66") (pin "2") (pinfunction "2_2") (pintype "passive"))
      (node (ref "C67") (pin "2") (pinfunction "2_2") (pintype "passive"))
      (node (ref "C69") (pin "2") (pinfunction "2_2") (pintype "passive"))
      (node (ref "C9") (pin "2") (pinfunction "2_2") (pintype "passive"))
      (node (ref "D10") (pin "1") (pinfunction "A1_1") (pintype "passive"))
      (node (ref "D11") (pin "1") (pinfunction "A_1") (pintype "passive"))
      (node (ref "D12") (pin "1") (pinfunction "A1_1") (pintype "passive"))
      (node (ref "D13") (pin "1") (pinfunction "A_1") (pintype "passive"))
      (node (ref "D14") (pin "1") (pinfunction "A1_1") (pintype "passive"))
      (node (ref "D15") (pin "1") (pinfunction "A_1") (pintype "passive"))
      (node (ref "D16") (pin "1") (pinfunction "A_1") (pintype "passive"))
      (node (ref "D17") (pin "1") (pinfunction "A_1") (pintype "passive"))
      (node (ref "D18") (pin "1") (pinfunction "A_1") (pintype "passive"))
      (node (ref "D19") (pin "1") (pinfunction "A_1") (pintype "passive"))
      (node (ref "D20") (pin "1") (pinfunction "A_1") (pintype "passive"))
      (node (ref "D21") (pin "1") (pinfunction "A_1") (pintype "passive"))
      (node (ref "D22") (pin "1") (pinfunction "A_1") (pintype "passive"))
      (node (ref "D23") (pin "1") (pinfunction "A_1") (pintype "passive"))
      (node (ref "D25") (pin "1") (pinfunction "A1_1") (pintype "passive"))
      (node (ref "D26") (pin "1") (pinfunction "A1_1") (pintype "passive"))
      (node (ref "D27") (pin "1") (pinfunction "A1_1") (pintype "passive"))
      (node (ref "D28") (pin "1") (pinfunction "A1_1") (pintype "passive"))
      (node (ref "D3") (pin "1") (pinfunction "A_1") (pintype "passive"))
      (node (ref "D30") (pin "1") (pinfunction "A1_1") (pintype "passive"))
      (node (ref "D31") (pin "1") (pinfunction "A1_1") (pintype "passive"))
      (node (ref "D32") (pin "1") (pinfunction "A1_1") (pintype "passive"))
      (node (ref "D33") (pin "1") (pinfunction "A1_1") (pintype "passive"))
      (node (ref "D4") (pin "1") (pinfunction "A_1") (pintype "passive"))
      (node (ref "D5") (pin "1") (pinfunction "A_1") (pintype "passive"))
      (node (ref "D6") (pin "1") (pinfunction "A_1") (pintype "passive"))
      (node (ref "D7") (pin "A") (pinfunction "A_A") (pintype "passive"))
      (node (ref "D8") (pin "1") (pinfunction "A1_1") (pintype "passive"))
      (node (ref "D9") (pin "1") (pinfunction "A_1") (pintype "passive"))
      (node (ref "GND") (pin "1") (pinfunction "1_1") (pintype "passive"))
      (node (ref "GND") (pin "2") (pinfunction "2_2") (pintype "passive"))
      (node (ref "GND") (pin "3") (pinfunction "3_3") (pintype "passive"))
      (node (ref "IC1") (pin "4") (pinfunction "V-_4") (pintype "power_in"))
      (node (ref "IC2") (pin "1") (pinfunction "GND_1") (pintype "input"))
      (node (ref "IC3") (pin "12") (pinfunction "V-_12") (pintype "power_in"))
      (node (ref "IC4") (pin "12") (pinfunction "V-_12") (pintype "power_in"))
      (node (ref "IC5") (pin "12") (pinfunction "V-_12") (pintype "power_in"))
      (node (ref "IC6") (pin "12") (pinfunction "V-_12") (pintype "power_in"))
      (node (ref "IC7") (pin "8") (pinfunction "GND_8") (pintype "power_in"))
      (node (ref "IC8") (pin "8") (pinfunction "GND_8") (pintype "power_in"))
      (node (ref "K1") (pin "3") (pinfunction "GND_3") (pintype "bidirectional"))
      (node (ref "K1") (pin "5") (pinfunction "GND_5") (pintype "bidirectional"))
      (node (ref "K1") (pin "9") (pinfunction "GNDDTCT_9") (pintype "bidirectional"))
      (node (ref "PL1") (pin "14") (pinfunction "S_14") (pintype "passive"))
      (node (ref "PL1") (pin "5") (pinfunction "S_5") (pintype "passive"))
      (node (ref "PL3") (pin "11") (pinfunction "S_11") (pintype "passive"))
      (node (ref "PL3") (pin "4") (pinfunction "S_4") (pintype "passive"))
      (node (ref "Q1") (pin "E") (pinfunction "E_E") (pintype "passive"))
      (node (ref "Q2") (pin "E") (pinfunction "E_E") (pintype "passive"))
      (node (ref "Q3") (pin "E") (pinfunction "E_E") (pintype "passive"))
      (node (ref "Q4") (pin "E") (pinfunction "E_E") (pintype "passive"))
      (node (ref "Q5") (pin "E") (pinfunction "E_E") (pintype "passive"))
      (node (ref "R107") (pin "1") (pinfunction "1_1") (pintype "passive"))
      (node (ref "R11") (pin "1") (pinfunction "1_1") (pintype "passive"))
      (node (ref "R111") (pin "1") (pinfunction "1_1") (pintype "passive"))
      (node (ref "R115") (pin "1") (pinfunction "1_1") (pintype "passive"))
      (node (ref "R119") (pin "1") (pinfunction "1_1") (pintype "passive"))
      (node (ref "R129") (pin "1") (pinfunction "1_1") (pintype "passive"))
      (node (ref "R133") (pin "1") (pinfunction "1_1") (pintype "passive"))
      (node (ref "R137") (pin "1") (pinfunction "1_1") (pintype "passive"))
      (node (ref "R141") (pin "1") (pinfunction "1_1") (pintype "passive"))
      (node (ref "R151") (pin "1") (pinfunction "1_1") (pintype "passive"))
      (node (ref "R155") (pin "1") (pinfunction "1_1") (pintype "passive"))
      (node (ref "R159") (pin "1") (pinfunction "1_1") (pintype "passive"))
      (node (ref "R163") (pin "1") (pinfunction "1_1") (pintype "passive"))
      (node (ref "R169") (pin "1") (pinfunction "1_1") (pintype "passive"))
      (node (ref "R171") (pin "1") (pinfunction "1_1") (pintype "passive"))
      (node (ref "R175") (pin "1") (pinfunction "1_1") (pintype "passive"))
      (node (ref "R179") (pin "1") (pinfunction "1_1") (pintype "passive"))
      (node (ref "R183") (pin "1") (pinfunction "1_1") (pintype "passive"))
      (node (ref "R187") (pin "1") (pinfunction "1_1") (pintype "passive"))
      (node (ref "R189") (pin "2") (pinfunction "2_2") (pintype "passive"))
      (node (ref "R190") (pin "2") (pinfunction "2_2") (pintype "passive"))
      (node (ref "R21") (pin "1") (pinfunction "1_1") (pintype "passive"))
      (node (ref "R25") (pin "1") (pinfunction "1_1") (pintype "passive"))
      (node (ref "R28") (pin "1") (pinfunction "1_1") (pintype "passive"))
      (node (ref "R3") (pin "1") (pinfunction "1_1") (pintype "passive"))
      (node (ref "R32") (pin "1") (pinfunction "1_1") (pintype "passive"))
      (node (ref "R35") (pin "1") (pinfunction "1_1") (pintype "passive"))
      (node (ref "R39") (pin "1") (pinfunction "1_1") (pintype "passive"))
      (node (ref "R46") (pin "1") (pinfunction "1_1") (pintype "passive"))
      (node (ref "R54") (pin "2") (pinfunction "2_2") (pintype "passive"))
      (node (ref "R55") (pin "2") (pinfunction "2_2") (pintype "passive"))
      (node (ref "R56") (pin "2") (pinfunction "2_2") (pintype "passive"))
      (node (ref "R57") (pin "2") (pinfunction "2_2") (pintype "passive"))
      (node (ref "R58") (pin "2") (pinfunction "2_2") (pintype "passive"))
      (node (ref "R64") (pin "1") (pinfunction "1_1") (pintype "passive"))
      (node (ref "R66") (pin "1") (pinfunction "1_1") (pintype "passive"))
      (node (ref "R7") (pin "1") (pinfunction "1_1") (pintype "passive"))
      (node (ref "R79") (pin "2") (pinfunction "2_2") (pintype "passive"))
      (node (ref "R89") (pin "1") (pinfunction "1_1") (pintype "passive"))
      (node (ref "R93") (pin "1") (pinfunction "1_1") (pintype "passive"))
      (node (ref "R97") (pin "1") (pinfunction "1_1") (pintype "passive"))
      (node (ref "U1") (pin "12") (pinfunction "VSSA/VREF-_12") (pintype "bidirectional"))
      (node (ref "U1") (pin "18") (pinfunction "VSS_1_18") (pintype "bidirectional"))
      (node (ref "U1") (pin "31") (pinfunction "VSS_2_31") (pintype "bidirectional"))
      (node (ref "U1") (pin "47") (pinfunction "VSS_3_47") (pintype "bidirectional"))
      (node (ref "U1") (pin "60") (pinfunction "BOOT0_60") (pintype "bidirectional"))
      (node (ref "U1") (pin "63") (pinfunction "VSS_4_63") (pintype "bidirectional"))
      (node (ref "U12") (pin "3") (pinfunction "/LOCK_3") (pintype "input"))
      (node (ref "U12") (pin "4") (pinfunction "GND_4") (pintype "power_in"))
      (node (ref "U12") (pin "5") (pinfunction "GND_5") (pintype "power_in"))
      (node (ref "U15") (pin "2") (pinfunction "GND_2") (pintype "power_in"))
      (node (ref "U19") (pin "3") (pinfunction "/LOCK_3") (pintype "input"))
      (node (ref "U19") (pin "4") (pinfunction "GND_4") (pintype "power_in"))
      (node (ref "U19") (pin "5") (pinfunction "GND_5") (pintype "power_in"))
      (node (ref "U2") (pin "C1") (pinfunction "COM1_C1") (pintype "bidirectional"))
      (node (ref "U2") (pin "C2") (pinfunction "COM2_C2") (pintype "bidirectional"))
      (node (ref "U21") (pin "3") (pinfunction "/LOCK_3") (pintype "input"))
      (node (ref "U21") (pin "4") (pinfunction "GND_4") (pintype "power_in"))
      (node (ref "U21") (pin "5") (pinfunction "GND_5") (pintype "power_in"))
      (node (ref "U22") (pin "3") (pinfunction "/LOCK_3") (pintype "input"))
      (node (ref "U22") (pin "4") (pinfunction "GND_4") (pintype "power_in"))
      (node (ref "U22") (pin "5") (pinfunction "GND_5") (pintype "power_in"))
      (node (ref "U24") (pin "3") (pinfunction "/LOCK_3") (pintype "input"))
      (node (ref "U24") (pin "4") (pinfunction "GND_4") (pintype "power_in"))
      (node (ref "U24") (pin "5") (pinfunction "GND_5") (pintype "power_in"))
      (node (ref "U25") (pin "3") (pinfunction "/LOCK_3") (pintype "input"))
      (node (ref "U25") (pin "4") (pinfunction "GND_4") (pintype "power_in"))
      (node (ref "U25") (pin "5") (pinfunction "GND_5") (pintype "power_in"))
      (node (ref "U27") (pin "3") (pinfunction "/LOCK_3") (pintype "input"))
      (node (ref "U27") (pin "4") (pinfunction "GND_4") (pintype "power_in"))
      (node (ref "U27") (pin "5") (pinfunction "GND_5") (pintype "power_in"))
      (node (ref "U28") (pin "3") (pinfunction "/LOCK_3") (pintype "input"))
      (node (ref "U28") (pin "4") (pinfunction "GND_4") (pintype "power_in"))
      (node (ref "U28") (pin "5") (pinfunction "GND_5") (pintype "power_in"))
      (node (ref "U30") (pin "2") (pinfunction "GND1_2") (pintype "input"))
      (node (ref "U30") (pin "7") (pinfunction "GND1_7") (pintype "input"))
      (node (ref "U30") (pin "8") (pinfunction "GND1_8") (pintype "input"))
      (node (ref "U31") (pin "3") (pinfunction "/LOCK_3") (pintype "input"))
      (node (ref "U31") (pin "4") (pinfunction "GND_4") (pintype "power_in"))
      (node (ref "U31") (pin "5") (pinfunction "GND_5") (pintype "power_in"))
      (node (ref "U5") (pin "3") (pinfunction "/LOCK_3") (pintype "input"))
      (node (ref "U5") (pin "4") (pinfunction "GND_4") (pintype "power_in"))
      (node (ref "U5") (pin "5") (pinfunction "GND_5") (pintype "power_in"))
      (node (ref "U6") (pin "3") (pinfunction "/LOCK_3") (pintype "input"))
      (node (ref "U6") (pin "4") (pinfunction "GND_4") (pintype "power_in"))
      (node (ref "U6") (pin "5") (pinfunction "GND_5") (pintype "power_in"))
      (node (ref "U7") (pin "VOUT-") (pinfunction "-VOUT_VOUT-") (pintype "bidirectional"))
      (node (ref "U9") (pin "3") (pinfunction "/LOCK_3") (pintype "input"))
      (node (ref "U9") (pin "4") (pinfunction "GND_4") (pintype "power_in"))
      (node (ref "U9") (pin "5") (pinfunction "GND_5") (pintype "power_in"))
    )
    (net (code "65") (name "GND1") (class "Default")
      (node (ref "C18") (pin "2") (pinfunction "2_2") (pintype "passive"))
      (node (ref "C19") (pin "2") (pinfunction "2_2") (pintype "passive"))
      (node (ref "C20") (pin "2") (pinfunction "2_2") (pintype "passive"))
      (node (ref "C21") (pin "-") (pinfunction "-_-") (pintype "passive"))
      (node (ref "C68") (pin "2") (pinfunction "2_2") (pintype "passive"))
      (node (ref "C7") (pin "2") (pinfunction "2_2") (pintype "passive"))
      (node (ref "C8") (pin "-") (pinfunction "-_-") (pintype "passive"))
      (node (ref "D1") (pin "C") (pinfunction "E_C") (pintype "passive"))
      (node (ref "D2") (pin "A") (pinfunction "A_A") (pintype "passive"))
      (node (ref "K2") (pin "A27") (pinfunction "A27_A27") (pintype "passive"))
      (node (ref "K2") (pin "A28") (pinfunction "A28_A28") (pintype "passive"))
      (node (ref "K2") (pin "A29") (pinfunction "A29_A29") (pintype "passive"))
      (node (ref "K2") (pin "C27") (pinfunction "C27_C27") (pintype "passive"))
      (node (ref "K2") (pin "C28") (pinfunction "C28_C28") (pintype "passive"))
      (node (ref "K2") (pin "C29") (pinfunction "C29_C29") (pintype "passive"))
      (node (ref "R16") (pin "1") (pinfunction "1_1") (pintype "passive"))
      (node (ref "R74") (pin "1") (pinfunction "1_1") (pintype "passive"))
      (node (ref "U14") (pin "2") (pinfunction "GND_2") (pintype "bidirectional"))
      (node (ref "U30") (pin "10") (pinfunction "GND2_10") (pintype "input"))
      (node (ref "U30") (pin "15") (pinfunction "GND2_15") (pintype "input"))
      (node (ref "U30") (pin "9") (pinfunction "GND2_9") (pintype "input"))
      (node (ref "U7") (pin "VIN-") (pinfunction "-VIN_VIN-") (pintype "bidirectional"))
    )
    (net (code "66") (name "INPUT0") (class "Default")
      (node (ref "PL1") (pin "3") (pinfunction "S_3") (pintype "passive"))
      (node (ref "R2") (pin "1") (pinfunction "1_1") (pintype "passive"))
    )
    (net (code "67") (name "INPUT1") (class "Default")
      (node (ref "PL1") (pin "12") (pinfunction "S_12") (pintype "passive"))
      (node (ref "R6") (pin "1") (pinfunction "1_1") (pintype "passive"))
    )
    (net (code "68") (name "INPUT2") (class "Default")
      (node (ref "PL1") (pin "2") (pinfunction "S_2") (pintype "passive"))
      (node (ref "R10") (pin "1") (pinfunction "1_1") (pintype "passive"))
    )
    (net (code "69") (name "INPUT3") (class "Default")
      (node (ref "PL1") (pin "11") (pinfunction "S_11") (pintype "passive"))
      (node (ref "R20") (pin "1") (pinfunction "1_1") (pintype "passive"))
    )
    (net (code "70") (name "INPUT4") (class "Default")
      (node (ref "PL1") (pin "1") (pinfunction "S_1") (pintype "passive"))
      (node (ref "R65") (pin "1") (pinfunction "1_1") (pintype "passive"))
    )
    (net (code "71") (name "INPUT5") (class "Default")
      (node (ref "PL1") (pin "10") (pinfunction "S_10") (pintype "passive"))
      (node (ref "R88") (pin "1") (pinfunction "1_1") (pintype "passive"))
    )
    (net (code "72") (name "INPUT6") (class "Default")
      (node (ref "PL1") (pin "9") (pinfunction "S_9") (pintype "passive"))
      (node (ref "R92") (pin "1") (pinfunction "1_1") (pintype "passive"))
    )
    (net (code "73") (name "INPUT7") (class "Default")
      (node (ref "PL1") (pin "18") (pinfunction "S_18") (pintype "passive"))
      (node (ref "R96") (pin "1") (pinfunction "1_1") (pintype "passive"))
    )
    (net (code "74") (name "INPUT8") (class "Default")
      (node (ref "PL1") (pin "8") (pinfunction "S_8") (pintype "passive"))
      (node (ref "R106") (pin "1") (pinfunction "1_1") (pintype "passive"))
    )
    (net (code "75") (name "INPUT9") (class "Default")
      (node (ref "PL1") (pin "17") (pinfunction "S_17") (pintype "passive"))
      (node (ref "R110") (pin "1") (pinfunction "1_1") (pintype "passive"))
    )
    (net (code "76") (name "INPUT10") (class "Default")
      (node (ref "PL1") (pin "7") (pinfunction "S_7") (pintype "passive"))
      (node (ref "R114") (pin "1") (pinfunction "1_1") (pintype "passive"))
    )
    (net (code "77") (name "INPUT11") (class "Default")
      (node (ref "PL1") (pin "16") (pinfunction "S_16") (pintype "passive"))
      (node (ref "R118") (pin "1") (pinfunction "1_1") (pintype "passive"))
    )
    (net (code "78") (name "INPUT12") (class "Default")
      (node (ref "PL1") (pin "6") (pinfunction "S_6") (pintype "passive"))
      (node (ref "R128") (pin "1") (pinfunction "1_1") (pintype "passive"))
    )
    (net (code "79") (name "INPUT13") (class "Default")
      (node (ref "PL1") (pin "15") (pinfunction "S_15") (pintype "passive"))
      (node (ref "R132") (pin "1") (pinfunction "1_1") (pintype "passive"))
    )
    (net (code "80") (name "INPUT14") (class "Default")
      (node (ref "PL1") (pin "4") (pinfunction "S_4") (pintype "passive"))
      (node (ref "R136") (pin "1") (pinfunction "1_1") (pintype "passive"))
    )
    (net (code "81") (name "INPUT15") (class "Default")
      (node (ref "PL1") (pin "13") (pinfunction "S_13") (pintype "passive"))
      (node (ref "R140") (pin "1") (pinfunction "1_1") (pintype "passive"))
    )
    (net (code "82") (name "MODBUS_A") (class "Default")
      (node (ref "D1") (pin "E") (pinfunction "2_E") (pintype "passive"))
      (node (ref "K2") (pin "A3") (pinfunction "A3_A3") (pintype "passive"))
      (node (ref "K2") (pin "C3") (pinfunction "C3_C3") (pintype "passive"))
      (node (ref "R13") (pin "1") (pinfunction "1_1") (pintype "passive"))
      (node (ref "R17") (pin "1") (pinfunction "1_1") (pintype "passive"))
      (node (ref "S1") (pin "6") (pinfunction "6_6") (pintype "passive"))
    )
    (net (code "83") (name "MODBUS_B") (class "Default")
      (node (ref "D1") (pin "B") (pinfunction "1_B") (pintype "passive"))
      (node (ref "K2") (pin "A1") (pinfunction "A1_A1") (pintype "passive"))
      (node (ref "K2") (pin "C1") (pinfunction "C1_C1") (pintype "passive"))
      (node (ref "R14") (pin "1") (pinfunction "1_1") (pintype "passive"))
      (node (ref "S1") (pin "2") (pinfunction "2_2") (pintype "passive"))
      (node (ref "S1") (pin "4") (pinfunction "4_4") (pintype "passive"))
    )
    (net (code "84") (name "N$151") (class "Default")
      (node (ref "IC8") (pin "6") (pinfunction "QG_6") (pintype "tri_state"))
    )
    (net (code "85") (name "N$152") (class "Default")
      (node (ref "IC8") (pin "7") (pinfunction "QH_7") (pintype "tri_state"))
    )
    (net (code "86") (name "NRST") (class "Default")
      (node (ref "C16") (pin "1") (pinfunction "1_1") (pintype "passive"))
      (node (ref "K1") (pin "10") (pinfunction "~{RESET}_10") (pintype "bidirectional"))
      (node (ref "R12") (pin "1") (pinfunction "1_1") (pintype "passive"))
      (node (ref "U1") (pin "7") (pinfunction "NRST_7") (pintype "input"))
    )
    (net (code "87") (name "Net-(D3-AC)") (class "Default")
      (node (ref "D3") (pin "3") (pinfunction "AC_3") (pintype "passive"))
      (node (ref "IC3") (pin "8") (pinfunction "-IN_8") (pintype "input"))
      (node (ref "R6") (pin "2") (pinfunction "2_2") (pintype "passive"))
      (node (ref "R7") (pin "2") (pinfunction "2_2") (pintype "passive"))
    )
    (net (code "88") (name "Net-(D4-AC)") (class "Default")
      (node (ref "D4") (pin "3") (pinfunction "AC_3") (pintype "passive"))
      (node (ref "IC6") (pin "6") (pinfunction "-IN_6") (pintype "input"))
      (node (ref "R10") (pin "2") (pinfunction "2_2") (pintype "passive"))
      (node (ref "R11") (pin "2") (pinfunction "2_2") (pintype "passive"))
    )
    (net (code "89") (name "Net-(D5-AC)") (class "Default")
      (node (ref "D5") (pin "3") (pinfunction "AC_3") (pintype "passive"))
      (node (ref "IC6") (pin "4") (pinfunction "-IN_4") (pintype "input"))
      (node (ref "R20") (pin "2") (pinfunction "2_2") (pintype "passive"))
      (node (ref "R21") (pin "2") (pinfunction "2_2") (pintype "passive"))
    )
    (net (code "90") (name "Net-(D6-AC)") (class "Default")
      (node (ref "D6") (pin "3") (pinfunction "AC_3") (pintype "passive"))
      (node (ref "IC6") (pin "10") (pinfunction "-IN_10") (pintype "input"))
      (node (ref "R65") (pin "2") (pinfunction "2_2") (pintype "passive"))
      (node (ref "R66") (pin "2") (pinfunction "2_2") (pintype "passive"))
    )
    (net (code "91") (name "Net-(D8-C1A2)") (class "Default")
      (node (ref "D8") (pin "3") (pinfunction "C1A2_3") (pintype "passive"))
      (node (ref "R168") (pin "1") (pinfunction "1_1") (pintype "passive"))
      (node (ref "U11") (pin "8") (pinfunction "O1_8") (pintype "passive"))
      (node (ref "U11") (pin "9") (pinfunction "O1_9") (pintype "passive"))
      (node (ref "U5") (pin "6") (pinfunction "OUT-_6") (pintype "output"))
    )
    (net (code "92") (name "Net-(D9-AC)") (class "Default")
      (node (ref "D9") (pin "3") (pinfunction "AC_3") (pintype "passive"))
      (node (ref "IC6") (pin "8") (pinfunction "-IN_8") (pintype "input"))
      (node (ref "R88") (pin "2") (pinfunction "2_2") (pintype "passive"))
      (node (ref "R89") (pin "2") (pinfunction "2_2") (pintype "passive"))
    )
    (net (code "93") (name "Net-(D10-C1A2)") (class "Default")
      (node (ref "D10") (pin "3") (pinfunction "C1A2_3") (pintype "passive"))
      (node (ref "R167") (pin "1") (pinfunction "1_1") (pintype "passive"))
      (node (ref "U10") (pin "8") (pinfunction "O1_8") (pintype "passive"))
      (node (ref "U10") (pin "9") (pinfunction "O1_9") (pintype "passive"))
      (node (ref "U6") (pin "6") (pinfunction "OUT-_6") (pintype "output"))
    )
    (net (code "94") (name "Net-(D11-AC)") (class "Default")
      (node (ref "D11") (pin "3") (pinfunction "AC_3") (pintype "passive"))
      (node (ref "IC4") (pin "6") (pinfunction "-IN_6") (pintype "input"))
      (node (ref "R92") (pin "2") (pinfunction "2_2") (pintype "passive"))
      (node (ref "R93") (pin "2") (pinfunction "2_2") (pintype "passive"))
    )
    (net (code "95") (name "Net-(D12-C1A2)") (class "Default")
      (node (ref "D12") (pin "3") (pinfunction "C1A2_3") (pintype "passive"))
      (node (ref "R149") (pin "1") (pinfunction "1_1") (pintype "passive"))
      (node (ref "U11") (pin "11") (pinfunction "O1_11") (pintype "passive"))
      (node (ref "U11") (pin "6") (pinfunction "O1_6") (pintype "passive"))
      (node (ref "U9") (pin "6") (pinfunction "OUT-_6") (pintype "output"))
    )
    (net (code "96") (name "Net-(D13-AC)") (class "Default")
      (node (ref "D13") (pin "3") (pinfunction "AC_3") (pintype "passive"))
      (node (ref "IC4") (pin "4") (pinfunction "-IN_4") (pintype "input"))
      (node (ref "R96") (pin "2") (pinfunction "2_2") (pintype "passive"))
      (node (ref "R97") (pin "2") (pinfunction "2_2") (pintype "passive"))
    )
    (net (code "97") (name "Net-(D14-C1A2)") (class "Default")
      (node (ref "D14") (pin "3") (pinfunction "C1A2_3") (pintype "passive"))
      (node (ref "R166") (pin "1") (pinfunction "1_1") (pintype "passive"))
      (node (ref "U10") (pin "11") (pinfunction "O1_11") (pintype "passive"))
      (node (ref "U10") (pin "6") (pinfunction "O1_6") (pintype "passive"))
      (node (ref "U12") (pin "6") (pinfunction "OUT-_6") (pintype "output"))
    )
    (net (code "98") (name "Net-(D15-AC)") (class "Default")
      (node (ref "D15") (pin "3") (pinfunction "AC_3") (pintype "passive"))
      (node (ref "IC3") (pin "10") (pinfunction "-IN_10") (pintype "input"))
      (node (ref "R2") (pin "2") (pinfunction "2_2") (pintype "passive"))
      (node (ref "R3") (pin "2") (pinfunction "2_2") (pintype "passive"))
    )
    (net (code "99") (name "Net-(D16-AC)") (class "Default")
      (node (ref "D16") (pin "3") (pinfunction "AC_3") (pintype "passive"))
      (node (ref "IC4") (pin "10") (pinfunction "-IN_10") (pintype "input"))
      (node (ref "R106") (pin "2") (pinfunction "2_2") (pintype "passive"))
      (node (ref "R107") (pin "2") (pinfunction "2_2") (pintype "passive"))
    )
    (net (code "100") (name "Net-(D17-AC)") (class "Default")
      (node (ref "D17") (pin "3") (pinfunction "AC_3") (pintype "passive"))
      (node (ref "IC4") (pin "8") (pinfunction "-IN_8") (pintype "input"))
      (node (ref "R110") (pin "2") (pinfunction "2_2") (pintype "passive"))
      (node (ref "R111") (pin "2") (pinfunction "2_2") (pintype "passive"))
    )
    (net (code "101") (name "Net-(D18-AC)") (class "Default")
      (node (ref "D18") (pin "3") (pinfunction "AC_3") (pintype "passive"))
      (node (ref "IC5") (pin "6") (pinfunction "-IN_6") (pintype "input"))
      (node (ref "R114") (pin "2") (pinfunction "2_2") (pintype "passive"))
      (node (ref "R115") (pin "2") (pinfunction "2_2") (pintype "passive"))
    )
    (net (code "102") (name "Net-(D19-AC)") (class "Default")
      (node (ref "D19") (pin "3") (pinfunction "AC_3") (pintype "passive"))
      (node (ref "IC5") (pin "4") (pinfunction "-IN_4") (pintype "input"))
      (node (ref "R118") (pin "2") (pinfunction "2_2") (pintype "passive"))
      (node (ref "R119") (pin "2") (pinfunction "2_2") (pintype "passive"))
    )
    (net (code "103") (name "Net-(D20-AC)") (class "Default")
      (node (ref "D20") (pin "3") (pinfunction "AC_3") (pintype "passive"))
      (node (ref "IC5") (pin "10") (pinfunction "-IN_10") (pintype "input"))
      (node (ref "R128") (pin "2") (pinfunction "2_2") (pintype "passive"))
      (node (ref "R129") (pin "2") (pinfunction "2_2") (pintype "passive"))
    )
    (net (code "104") (name "Net-(D21-AC)") (class "Default")
      (node (ref "D21") (pin "3") (pinfunction "AC_3") (pintype "passive"))
      (node (ref "IC5") (pin "8") (pinfunction "-IN_8") (pintype "input"))
      (node (ref "R132") (pin "2") (pinfunction "2_2") (pintype "passive"))
      (node (ref "R133") (pin "2") (pinfunction "2_2") (pintype "passive"))
    )
    (net (code "105") (name "Net-(D22-AC)") (class "Default")
      (node (ref "D22") (pin "3") (pinfunction "AC_3") (pintype "passive"))
      (node (ref "IC3") (pin "6") (pinfunction "-IN_6") (pintype "input"))
      (node (ref "R136") (pin "2") (pinfunction "2_2") (pintype "passive"))
      (node (ref "R137") (pin "2") (pinfunction "2_2") (pintype "passive"))
    )
    (net (code "106") (name "Net-(D23-AC)") (class "Default")
      (node (ref "D23") (pin "3") (pinfunction "AC_3") (pintype "passive"))
      (node (ref "IC3") (pin "4") (pinfunction "-IN_4") (pintype "input"))
      (node (ref "R140") (pin "2") (pinfunction "2_2") (pintype "passive"))
      (node (ref "R141") (pin "2") (pinfunction "2_2") (pintype "passive"))
    )
    (net (code "107") (name "Net-(D25-C1A2)") (class "Default")
      (node (ref "D25") (pin "3") (pinfunction "C1A2_3") (pintype "passive"))
      (node (ref "R127") (pin "1") (pinfunction "1_1") (pintype "passive"))
      (node (ref "U19") (pin "6") (pinfunction "OUT-_6") (pintype "output"))
      (node (ref "U20") (pin "8") (pinfunction "O1_8") (pintype "passive"))
      (node (ref "U20") (pin "9") (pinfunction "O1_9") (pintype "passive"))
    )
    (net (code "108") (name "Net-(D26-C1A2)") (class "Default")
      (node (ref "D26") (pin "3") (pinfunction "C1A2_3") (pintype "passive"))
      (node (ref "R126") (pin "1") (pinfunction "1_1") (pintype "passive"))
      (node (ref "U20") (pin "11") (pinfunction "O1_11") (pintype "passive"))
      (node (ref "U20") (pin "6") (pinfunction "O1_6") (pintype "passive"))
      (node (ref "U21") (pin "6") (pinfunction "OUT-_6") (pintype "output"))
    )
    (net (code "109") (name "Net-(D27-C1A2)") (class "Default")
      (node (ref "D27") (pin "3") (pinfunction "C1A2_3") (pintype "passive"))
      (node (ref "R62") (pin "1") (pinfunction "1_1") (pintype "passive"))
      (node (ref "U22") (pin "6") (pinfunction "OUT-_6") (pintype "output"))
      (node (ref "U23") (pin "8") (pinfunction "O1_8") (pintype "passive"))
      (node (ref "U23") (pin "9") (pinfunction "O1_9") (pintype "passive"))
    )
    (net (code "110") (name "Net-(D28-C1A2)") (class "Default")
      (node (ref "D28") (pin "3") (pinfunction "C1A2_3") (pintype "passive"))
      (node (ref "R148") (pin "1") (pinfunction "1_1") (pintype "passive"))
      (node (ref "U24") (pin "6") (pinfunction "OUT-_6") (pintype "output"))
      (node (ref "U26") (pin "8") (pinfunction "O1_8") (pintype "passive"))
      (node (ref "U26") (pin "9") (pinfunction "O1_9") (pintype "passive"))
    )
    (net (code "111") (name "Net-(D30-C1A2)") (class "Default")
      (node (ref "D30") (pin "3") (pinfunction "C1A2_3") (pintype "passive"))
      (node (ref "R105") (pin "1") (pinfunction "1_1") (pintype "passive"))
      (node (ref "U25") (pin "6") (pinfunction "OUT-_6") (pintype "output"))
      (node (ref "U26") (pin "11") (pinfunction "O1_11") (pintype "passive"))
      (node (ref "U26") (pin "6") (pinfunction "O1_6") (pintype "passive"))
    )
    (net (code "112") (name "Net-(D31-C1A2)") (class "Default")
      (node (ref "D31") (pin "3") (pinfunction "C1A2_3") (pintype "passive"))
      (node (ref "R61") (pin "1") (pinfunction "1_1") (pintype "passive"))
      (node (ref "U27") (pin "6") (pinfunction "OUT-_6") (pintype "output"))
      (node (ref "U29") (pin "8") (pinfunction "O1_8") (pintype "passive"))
      (node (ref "U29") (pin "9") (pinfunction "O1_9") (pintype "passive"))
    )
    (net (code "113") (name "Net-(D32-C1A2)") (class "Default")
      (node (ref "D32") (pin "3") (pinfunction "C1A2_3") (pintype "passive"))
      (node (ref "R59") (pin "1") (pinfunction "1_1") (pintype "passive"))
      (node (ref "U23") (pin "11") (pinfunction "O1_11") (pintype "passive"))
      (node (ref "U23") (pin "6") (pinfunction "O1_6") (pintype "passive"))
      (node (ref "U28") (pin "6") (pinfunction "OUT-_6") (pintype "output"))
    )
    (net (code "114") (name "Net-(D33-C1A2)") (class "Default")
      (node (ref "D33") (pin "3") (pinfunction "C1A2_3") (pintype "passive"))
      (node (ref "R60") (pin "1") (pinfunction "1_1") (pintype "passive"))
      (node (ref "U29") (pin "11") (pinfunction "O1_11") (pintype "passive"))
      (node (ref "U29") (pin "6") (pinfunction "O1_6") (pintype "passive"))
      (node (ref "U31") (pin "6") (pinfunction "OUT-_6") (pintype "output"))
    )
    (net (code "115") (name "Net-(IC1A-IN+)") (class "Default")
      (node (ref "C64") (pin "1") (pinfunction "1_1") (pintype "passive"))
      (node (ref "IC1") (pin "3") (pinfunction "IN+_3") (pintype "input"))
      (node (ref "R73") (pin "2") (pinfunction "2_2") (pintype "passive"))
    )
    (net (code "116") (name "Net-(IC1A-IN-)") (class "Default")
      (node (ref "IC1") (pin "2") (pinfunction "IN-_2") (pintype "input"))
      (node (ref "R104") (pin "1") (pinfunction "1_1") (pintype "passive"))
      (node (ref "R169") (pin "2") (pinfunction "2_2") (pintype "passive"))
    )
    (net (code "117") (name "Net-(IC1A-OUT)") (class "Default")
      (node (ref "IC1") (pin "1") (pinfunction "OUT_1") (pintype "output"))
      (node (ref "R104") (pin "2") (pinfunction "2_2") (pintype "passive"))
      (node (ref "R139") (pin "1") (pinfunction "1_1") (pintype "passive"))
      (node (ref "R143") (pin "1") (pinfunction "1_1") (pintype "passive"))
      (node (ref "R19") (pin "1") (pinfunction "1_1") (pintype "passive"))
      (node (ref "R23") (pin "1") (pinfunction "1_1") (pintype "passive"))
      (node (ref "R5") (pin "1") (pinfunction "1_1") (pintype "passive"))
      (node (ref "R87") (pin "1") (pinfunction "1_1") (pintype "passive"))
      (node (ref "R9") (pin "1") (pinfunction "1_1") (pintype "passive"))
      (node (ref "R91") (pin "1") (pinfunction "1_1") (pintype "passive"))
    )
    (net (code "118") (name "Net-(IC1B-IN+)") (class "Default")
      (node (ref "C63") (pin "1") (pinfunction "1_1") (pintype "passive"))
      (node (ref "IC1") (pin "5") (pinfunction "IN+_5") (pintype "input"))
      (node (ref "R72") (pin "2") (pinfunction "2_2") (pintype "passive"))
    )
    (net (code "119") (name "Net-(IC1B-IN-)") (class "Default")
      (node (ref "IC1") (pin "6") (pinfunction "IN-_6") (pintype "input"))
      (node (ref "R186") (pin "1") (pinfunction "1_1") (pintype "passive"))
      (node (ref "R187") (pin "2") (pinfunction "2_2") (pintype "passive"))
    )
    (net (code "120") (name "Net-(IC1B-OUT)") (class "Default")
      (node (ref "IC1") (pin "7") (pinfunction "OUT_7") (pintype "output"))
      (node (ref "R109") (pin "1") (pinfunction "1_1") (pintype "passive"))
      (node (ref "R113") (pin "1") (pinfunction "1_1") (pintype "passive"))
      (node (ref "R117") (pin "1") (pinfunction "1_1") (pintype "passive"))
      (node (ref "R121") (pin "1") (pinfunction "1_1") (pintype "passive"))
      (node (ref "R131") (pin "1") (pinfunction "1_1") (pintype "passive"))
      (node (ref "R135") (pin "1") (pinfunction "1_1") (pintype "passive"))
      (node (ref "R186") (pin "2") (pinfunction "2_2") (pintype "passive"))
      (node (ref "R95") (pin "1") (pinfunction "1_1") (pintype "passive"))
      (node (ref "R99") (pin "1") (pinfunction "1_1") (pintype "passive"))
    )
    (net (code "121") (name "Net-(IC2-IN)") (class "Default")
      (node (ref "C12") (pin "1") (pinfunction "1_1") (pintype "passive"))
      (node (ref "IC2") (pin "3") (pinfunction "IN_3") (pintype "input"))
      (node (ref "R80") (pin "2") (pinfunction "2_2") (pintype "passive"))
    )
    (net (code "122") (name "Net-(IC3A-+IN)") (class "Default")
      (node (ref "IC3") (pin "5") (pinfunction "+IN_5") (pintype "input"))
      (node (ref "R142") (pin "2") (pinfunction "2_2") (pintype "passive"))
      (node (ref "R143") (pin "2") (pinfunction "2_2") (pintype "passive"))
    )
    (net (code "123") (name "Net-(IC3A-OUT)") (class "Default")
      (node (ref "IC3") (pin "2") (pinfunction "OUT_2") (pintype "output"))
      (node (ref "R142") (pin "1") (pinfunction "1_1") (pintype "passive"))
      (node (ref "R145") (pin "2") (pinfunction "2_2") (pintype "passive"))
    )
    (net (code "124") (name "Net-(IC3B-+IN)") (class "Default")
      (node (ref "IC3") (pin "7") (pinfunction "+IN_7") (pintype "input"))
      (node (ref "R138") (pin "2") (pinfunction "2_2") (pintype "passive"))
      (node (ref "R139") (pin "2") (pinfunction "2_2") (pintype "passive"))
    )
    (net (code "125") (name "Net-(IC3B-OUT)") (class "Default")
      (node (ref "IC3") (pin "1") (pinfunction "OUT_1") (pintype "output"))
      (node (ref "R138") (pin "1") (pinfunction "1_1") (pintype "passive"))
      (node (ref "R144") (pin "2") (pinfunction "2_2") (pintype "passive"))
    )
    (net (code "126") (name "Net-(IC3C-+IN)") (class "Default")
      (node (ref "IC3") (pin "9") (pinfunction "+IN_9") (pintype "input"))
      (node (ref "R8") (pin "2") (pinfunction "2_2") (pintype "passive"))
      (node (ref "R9") (pin "2") (pinfunction "2_2") (pintype "passive"))
    )
    (net (code "127") (name "Net-(IC3C-OUT)") (class "Default")
      (node (ref "IC3") (pin "14") (pinfunction "OUT_14") (pintype "output"))
      (node (ref "R70") (pin "2") (pinfunction "2_2") (pintype "passive"))
      (node (ref "R8") (pin "1") (pinfunction "1_1") (pintype "passive"))
    )
    (net (code "128") (name "Net-(IC3D-+IN)") (class "Default")
      (node (ref "IC3") (pin "11") (pinfunction "+IN_11") (pintype "input"))
      (node (ref "R4") (pin "2") (pinfunction "2_2") (pintype "passive"))
      (node (ref "R5") (pin "2") (pinfunction "2_2") (pintype "passive"))
    )
    (net (code "129") (name "Net-(IC3D-OUT)") (class "Default")
      (node (ref "IC3") (pin "13") (pinfunction "OUT_13") (pintype "output"))
      (node (ref "R4") (pin "1") (pinfunction "1_1") (pintype "passive"))
      (node (ref "R71") (pin "2") (pinfunction "2_2") (pintype "passive"))
    )
    (net (code "130") (name "Net-(IC4A-+IN)") (class "Default")
      (node (ref "IC4") (pin "5") (pinfunction "+IN_5") (pintype "input"))
      (node (ref "R98") (pin "2") (pinfunction "2_2") (pintype "passive"))
      (node (ref "R99") (pin "2") (pinfunction "2_2") (pintype "passive"))
    )
    (net (code "131") (name "Net-(IC4A-OUT)") (class "Default")
      (node (ref "IC4") (pin "2") (pinfunction "OUT_2") (pintype "output"))
      (node (ref "R101") (pin "2") (pinfunction "2_2") (pintype "passive"))
      (node (ref "R98") (pin "1") (pinfunction "1_1") (pintype "passive"))
    )
    (net (code "132") (name "Net-(IC4B-+IN)") (class "Default")
      (node (ref "IC4") (pin "7") (pinfunction "+IN_7") (pintype "input"))
      (node (ref "R94") (pin "2") (pinfunction "2_2") (pintype "passive"))
      (node (ref "R95") (pin "2") (pinfunction "2_2") (pintype "passive"))
    )
    (net (code "133") (name "Net-(IC4B-OUT)") (class "Default")
      (node (ref "IC4") (pin "1") (pinfunction "OUT_1") (pintype "output"))
      (node (ref "R100") (pin "2") (pinfunction "2_2") (pintype "passive"))
      (node (ref "R94") (pin "1") (pinfunction "1_1") (pintype "passive"))
    )
    (net (code "134") (name "Net-(IC4C-+IN)") (class "Default")
      (node (ref "IC4") (pin "9") (pinfunction "+IN_9") (pintype "input"))
      (node (ref "R112") (pin "2") (pinfunction "2_2") (pintype "passive"))
      (node (ref "R113") (pin "2") (pinfunction "2_2") (pintype "passive"))
    )
    (net (code "135") (name "Net-(IC4C-OUT)") (class "Default")
      (node (ref "IC4") (pin "14") (pinfunction "OUT_14") (pintype "output"))
      (node (ref "R112") (pin "1") (pinfunction "1_1") (pintype "passive"))
      (node (ref "R124") (pin "2") (pinfunction "2_2") (pintype "passive"))
    )
    (net (code "136") (name "Net-(IC4D-+IN)") (class "Default")
      (node (ref "IC4") (pin "11") (pinfunction "+IN_11") (pintype "input"))
      (node (ref "R108") (pin "2") (pinfunction "2_2") (pintype "passive"))
      (node (ref "R109") (pin "2") (pinfunction "2_2") (pintype "passive"))
    )
    (net (code "137") (name "Net-(IC4D-OUT)") (class "Default")
      (node (ref "IC4") (pin "13") (pinfunction "OUT_13") (pintype "output"))
      (node (ref "R108") (pin "1") (pinfunction "1_1") (pintype "passive"))
      (node (ref "R125") (pin "2") (pinfunction "2_2") (pintype "passive"))
    )
    (net (code "138") (name "Net-(IC5A-+IN)") (class "Default")
      (node (ref "IC5") (pin "5") (pinfunction "+IN_5") (pintype "input"))
      (node (ref "R120") (pin "2") (pinfunction "2_2") (pintype "passive"))
      (node (ref "R121") (pin "2") (pinfunction "2_2") (pintype "passive"))
    )
    (net (code "139") (name "Net-(IC5A-OUT)") (class "Default")
      (node (ref "IC5") (pin "2") (pinfunction "OUT_2") (pintype "output"))
      (node (ref "R120") (pin "1") (pinfunction "1_1") (pintype "passive"))
      (node (ref "R123") (pin "2") (pinfunction "2_2") (pintype "passive"))
    )
    (net (code "140") (name "Net-(IC5B-+IN)") (class "Default")
      (node (ref "IC5") (pin "7") (pinfunction "+IN_7") (pintype "input"))
      (node (ref "R116") (pin "2") (pinfunction "2_2") (pintype "passive"))
      (node (ref "R117") (pin "2") (pinfunction "2_2") (pintype "passive"))
    )
    (net (code "141") (name "Net-(IC5B-OUT)") (class "Default")
      (node (ref "IC5") (pin "1") (pinfunction "OUT_1") (pintype "output"))
      (node (ref "R116") (pin "1") (pinfunction "1_1") (pintype "passive"))
      (node (ref "R122") (pin "2") (pinfunction "2_2") (pintype "passive"))
    )
    (net (code "142") (name "Net-(IC5C-+IN)") (class "Default")
      (node (ref "IC5") (pin "9") (pinfunction "+IN_9") (pintype "input"))
      (node (ref "R134") (pin "2") (pinfunction "2_2") (pintype "passive"))
      (node (ref "R135") (pin "2") (pinfunction "2_2") (pintype "passive"))
    )
    (net (code "143") (name "Net-(IC5C-OUT)") (class "Default")
      (node (ref "IC5") (pin "14") (pinfunction "OUT_14") (pintype "output"))
      (node (ref "R134") (pin "1") (pinfunction "1_1") (pintype "passive"))
      (node (ref "R146") (pin "2") (pinfunction "2_2") (pintype "passive"))
    )
    (net (code "144") (name "Net-(IC5D-+IN)") (class "Default")
      (node (ref "IC5") (pin "11") (pinfunction "+IN_11") (pintype "input"))
      (node (ref "R130") (pin "2") (pinfunction "2_2") (pintype "passive"))
      (node (ref "R131") (pin "2") (pinfunction "2_2") (pintype "passive"))
    )
    (net (code "145") (name "Net-(IC5D-OUT)") (class "Default")
      (node (ref "IC5") (pin "13") (pinfunction "OUT_13") (pintype "output"))
      (node (ref "R130") (pin "1") (pinfunction "1_1") (pintype "passive"))
      (node (ref "R147") (pin "2") (pinfunction "2_2") (pintype "passive"))
    )
    (net (code "146") (name "Net-(IC6A-+IN)") (class "Default")
      (node (ref "IC6") (pin "5") (pinfunction "+IN_5") (pintype "input"))
      (node (ref "R22") (pin "2") (pinfunction "2_2") (pintype "passive"))
      (node (ref "R23") (pin "2") (pinfunction "2_2") (pintype "passive"))
    )
    (net (code "147") (name "Net-(IC6A-OUT)") (class "Default")
      (node (ref "IC6") (pin "2") (pinfunction "OUT_2") (pintype "output"))
      (node (ref "R22") (pin "1") (pinfunction "1_1") (pintype "passive"))
      (node (ref "R69") (pin "2") (pinfunction "2_2") (pintype "passive"))
    )
    (net (code "148") (name "Net-(IC6B-+IN)") (class "Default")
      (node (ref "IC6") (pin "7") (pinfunction "+IN_7") (pintype "input"))
      (node (ref "R18") (pin "2") (pinfunction "2_2") (pintype "passive"))
      (node (ref "R19") (pin "2") (pinfunction "2_2") (pintype "passive"))
    )
    (net (code "149") (name "Net-(IC6B-OUT)") (class "Default")
      (node (ref "IC6") (pin "1") (pinfunction "OUT_1") (pintype "output"))
      (node (ref "R18") (pin "1") (pinfunction "1_1") (pintype "passive"))
      (node (ref "R68") (pin "2") (pinfunction "2_2") (pintype "passive"))
    )
    (net (code "150") (name "Net-(IC6C-+IN)") (class "Default")
      (node (ref "IC6") (pin "9") (pinfunction "+IN_9") (pintype "input"))
      (node (ref "R90") (pin "2") (pinfunction "2_2") (pintype "passive"))
      (node (ref "R91") (pin "2") (pinfunction "2_2") (pintype "passive"))
    )
    (net (code "151") (name "Net-(IC6C-OUT)") (class "Default")
      (node (ref "IC6") (pin "14") (pinfunction "OUT_14") (pintype "output"))
      (node (ref "R102") (pin "2") (pinfunction "2_2") (pintype "passive"))
      (node (ref "R90") (pin "1") (pinfunction "1_1") (pintype "passive"))
    )
    (net (code "152") (name "Net-(IC6D-+IN)") (class "Default")
      (node (ref "IC6") (pin "11") (pinfunction "+IN_11") (pintype "input"))
      (node (ref "R67") (pin "2") (pinfunction "2_2") (pintype "passive"))
      (node (ref "R87") (pin "2") (pinfunction "2_2") (pintype "passive"))
    )
    (net (code "153") (name "Net-(IC6D-OUT)") (class "Default")
      (node (ref "IC6") (pin "13") (pinfunction "OUT_13") (pintype "output"))
      (node (ref "R103") (pin "2") (pinfunction "2_2") (pintype "passive"))
      (node (ref "R67") (pin "1") (pinfunction "1_1") (pintype "passive"))
    )
    (net (code "154") (name "Net-(IC7A-QH*)") (class "Default")
      (node (ref "IC7") (pin "9") (pinfunction "QH*_9") (pintype "tri_state"))
      (node (ref "IC8") (pin "14") (pinfunction "SER_14") (pintype "input"))
    )
    (net (code "155") (name "Net-(LED5-PadC)") (class "Default")
      (node (ref "LED5") (pin "C") (pinfunction "C_C") (pintype "passive"))
      (node (ref "R31") (pin "1") (pinfunction "1_1") (pintype "passive"))
    )
    (net (code "156") (name "Net-(LED6-PadC)") (class "Default")
      (node (ref "LED6") (pin "C") (pinfunction "C_C") (pintype "passive"))
      (node (ref "R30") (pin "1") (pinfunction "1_1") (pintype "passive"))
    )
    (net (code "157") (name "Net-(OSC-P$1)") (class "Default")
      (node (ref "C44") (pin "2") (pinfunction "2_2") (pintype "passive"))
      (node (ref "OSC") (pin "1") (pinfunction "P$1_1") (pintype "bidirectional"))
      (node (ref "U1") (pin "5") (pinfunction "PH0-OSC_IN_5") (pintype "bidirectional"))
    )
    (net (code "158") (name "Net-(OSC-P$2)") (class "Default")
      (node (ref "C47") (pin "2") (pinfunction "2_2") (pintype "passive"))
      (node (ref "OSC") (pin "3") (pinfunction "P$2_3") (pintype "bidirectional"))
      (node (ref "R76") (pin "2") (pinfunction "2_2") (pintype "passive"))
    )
    (net (code "159") (name "Net-(Q1-PadB)") (class "Default")
      (node (ref "Q1") (pin "B") (pinfunction "B_B") (pintype "passive"))
      (node (ref "R42") (pin "2") (pinfunction "2_2") (pintype "passive"))
      (node (ref "R55") (pin "1") (pinfunction "1_1") (pintype "passive"))
    )
    (net (code "160") (name "Net-(Q1-PadC)") (class "Default")
      (node (ref "Q1") (pin "C") (pinfunction "C_C") (pintype "passive"))
      (node (ref "R47") (pin "1") (pinfunction "1_1") (pintype "passive"))
    )
    (net (code "161") (name "Net-(Q2-PadB)") (class "Default")
      (node (ref "Q2") (pin "B") (pinfunction "B_B") (pintype "passive"))
      (node (ref "R43") (pin "2") (pinfunction "2_2") (pintype "passive"))
      (node (ref "R56") (pin "1") (pinfunction "1_1") (pintype "passive"))
    )
    (net (code "162") (name "Net-(Q2-PadC)") (class "Default")
      (node (ref "Q2") (pin "C") (pinfunction "C_C") (pintype "passive"))
      (node (ref "R48") (pin "1") (pinfunction "1_1") (pintype "passive"))
    )
    (net (code "163") (name "Net-(Q3-PadB)") (class "Default")
      (node (ref "Q3") (pin "B") (pinfunction "B_B") (pintype "passive"))
      (node (ref "R44") (pin "2") (pinfunction "2_2") (pintype "passive"))
      (node (ref "R57") (pin "1") (pinfunction "1_1") (pintype "passive"))
    )
    (net (code "164") (name "Net-(Q3-PadC)") (class "Default")
      (node (ref "Q3") (pin "C") (pinfunction "C_C") (pintype "passive"))
      (node (ref "R50") (pin "1") (pinfunction "1_1") (pintype "passive"))
    )
    (net (code "165") (name "Net-(Q4-PadB)") (class "Default")
      (node (ref "Q4") (pin "B") (pinfunction "B_B") (pintype "passive"))
      (node (ref "R58") (pin "1") (pinfunction "1_1") (pintype "passive"))
      (node (ref "S2") (pin "2") (pinfunction "2_2") (pintype "passive"))
    )
    (net (code "166") (name "Net-(Q4-PadC)") (class "Default")
      (node (ref "Q4") (pin "C") (pinfunction "C_C") (pintype "passive"))
      (node (ref "R51") (pin "1") (pinfunction "1_1") (pintype "passive"))
    )
    (net (code "167") (name "Net-(Q5-PadB)") (class "Default")
      (node (ref "Q5") (pin "B") (pinfunction "B_B") (pintype "passive"))
      (node (ref "R79") (pin "1") (pinfunction "1_1") (pintype "passive"))
      (node (ref "S2") (pin "1") (pinfunction "1_1") (pintype "passive"))
    )
    (net (code "168") (name "Net-(Q5-PadC)") (class "Default")
      (node (ref "Q5") (pin "C") (pinfunction "C_C") (pintype "passive"))
      (node (ref "R78") (pin "1") (pinfunction "1_1") (pintype "passive"))
    )
    (net (code "169") (name "Net-(R15-Pad1)") (class "Default")
      (node (ref "R15") (pin "1") (pinfunction "1_1") (pintype "passive"))
      (node (ref "S1") (pin "1") (pinfunction "1_1") (pintype "passive"))
    )
    (net (code "170") (name "Net-(R16-Pad2)") (class "Default")
      (node (ref "R16") (pin "2") (pinfunction "2_2") (pintype "passive"))
      (node (ref "S1") (pin "3") (pinfunction "3_3") (pintype "passive"))
    )
    (net (code "171") (name "Net-(R17-Pad2)") (class "Default")
      (node (ref "R17") (pin "2") (pinfunction "2_2") (pintype "passive"))
      (node (ref "S1") (pin "5") (pinfunction "5_5") (pintype "passive"))
    )
    (net (code "172") (name "Net-(R45-Pad2)") (class "Default")
      (node (ref "R45") (pin "2") (pinfunction "2_2") (pintype "passive"))
      (node (ref "S2") (pin "3") (pinfunction "3_3") (pintype "passive"))
    )
    (net (code "173") (name "Net-(R77-Pad2)") (class "Default")
      (node (ref "R77") (pin "2") (pinfunction "2_2") (pintype "passive"))
      (node (ref "S2") (pin "4") (pinfunction "4_4") (pintype "passive"))
    )
    (net (code "174") (name "Net-(R81-Pad2)") (class "Default")
      (node (ref "R81") (pin "2") (pinfunction "2_2") (pintype "passive"))
      (node (ref "U2") (pin "8") (pinfunction "8_8") (pintype "bidirectional"))
    )
    (net (code "175") (name "Net-(R82-Pad2)") (class "Default")
      (node (ref "R82") (pin "2") (pinfunction "2_2") (pintype "passive"))
      (node (ref "U2") (pin "1") (pinfunction "1_1") (pintype "bidirectional"))
    )
    (net (code "176") (name "Net-(R83-Pad2)") (class "Default")
      (node (ref "R83") (pin "2") (pinfunction "2_2") (pintype "passive"))
      (node (ref "U2") (pin "2") (pinfunction "2_2") (pintype "bidirectional"))
    )
    (net (code "177") (name "Net-(R84-Pad2)") (class "Default")
      (node (ref "R84") (pin "2") (pinfunction "2_2") (pintype "passive"))
      (node (ref "U2") (pin "4") (pinfunction "4_4") (pintype "bidirectional"))
    )
    (net (code "178") (name "Net-(R105-Pad2)") (class "Default")
      (node (ref "R105") (pin "2") (pinfunction "2_2") (pintype "passive"))
      (node (ref "R172") (pin "1") (pinfunction "1_1") (pintype "passive"))
    )
    (net (code "179") (name "Net-(R126-Pad2)") (class "Default")
      (node (ref "R126") (pin "2") (pinfunction "2_2") (pintype "passive"))
      (node (ref "R156") (pin "1") (pinfunction "1_1") (pintype "passive"))
    )
    (net (code "180") (name "Net-(R127-Pad2)") (class "Default")
      (node (ref "R127") (pin "2") (pinfunction "2_2") (pintype "passive"))
      (node (ref "R152") (pin "1") (pinfunction "1_1") (pintype "passive"))
    )
    (net (code "181") (name "Net-(R148-Pad2)") (class "Default")
      (node (ref "R148") (pin "2") (pinfunction "2_2") (pintype "passive"))
      (node (ref "R164") (pin "1") (pinfunction "1_1") (pintype "passive"))
    )
    (net (code "182") (name "Net-(R149-Pad2)") (class "Default")
      (node (ref "R149") (pin "2") (pinfunction "2_2") (pintype "passive"))
      (node (ref "R36") (pin "1") (pinfunction "1_1") (pintype "passive"))
    )
    (net (code "183") (name "Net-(R160-Pad1)") (class "Default")
      (node (ref "R160") (pin "1") (pinfunction "1_1") (pintype "passive"))
      (node (ref "R62") (pin "2") (pinfunction "2_2") (pintype "passive"))
    )
    (net (code "184") (name "Net-(R166-Pad2)") (class "Default")
      (node (ref "R166") (pin "2") (pinfunction "2_2") (pintype "passive"))
      (node (ref "R40") (pin "1") (pinfunction "1_1") (pintype "passive"))
    )
    (net (code "185") (name "Net-(R167-Pad2)") (class "Default")
      (node (ref "R167") (pin "2") (pinfunction "2_2") (pintype "passive"))
      (node (ref "R29") (pin "1") (pinfunction "1_1") (pintype "passive"))
    )
    (net (code "186") (name "Net-(R168-Pad2)") (class "Default")
      (node (ref "R168") (pin "2") (pinfunction "2_2") (pintype "passive"))
      (node (ref "R26") (pin "1") (pinfunction "1_1") (pintype "passive"))
    )
    (net (code "187") (name "Net-(R176-Pad1)") (class "Default")
      (node (ref "R176") (pin "1") (pinfunction "1_1") (pintype "passive"))
      (node (ref "R61") (pin "2") (pinfunction "2_2") (pintype "passive"))
    )
    (net (code "188") (name "Net-(R180-Pad1)") (class "Default")
      (node (ref "R180") (pin "1") (pinfunction "1_1") (pintype "passive"))
      (node (ref "R59") (pin "2") (pinfunction "2_2") (pintype "passive"))
    )
    (net (code "189") (name "Net-(R184-Pad1)") (class "Default")
      (node (ref "R184") (pin "1") (pinfunction "1_1") (pintype "passive"))
      (node (ref "R60") (pin "2") (pinfunction "2_2") (pintype "passive"))
    )
    (net (code "190") (name "Net-(U1H-PH1-OSC_OUT)") (class "Default")
      (node (ref "R76") (pin "1") (pinfunction "1_1") (pintype "passive"))
      (node (ref "U1") (pin "6") (pinfunction "PH1-OSC_OUT_6") (pintype "bidirectional"))
    )
    (net (code "191") (name "Net-(U1J-VCAP_1)") (class "Default")
      (node (ref "C58") (pin "1") (pinfunction "1_1") (pintype "passive"))
      (node (ref "U1") (pin "30") (pinfunction "VCAP_1_30") (pintype "bidirectional"))
    )
    (net (code "192") (name "Net-(U1J-VDDA{slash}VREF+)") (class "Default")
      (node (ref "C1") (pin "1") (pinfunction "1_1") (pintype "passive"))
      (node (ref "C2") (pin "1") (pinfunction "1_1") (pintype "passive"))
      (node (ref "L1") (pin "2") (pinfunction "2_2") (pintype "passive"))
      (node (ref "U1") (pin "13") (pinfunction "VDDA/VREF+_13") (pintype "bidirectional"))
    )
    (net (code "193") (name "Net-(U5A--IN)") (class "Default")
      (node (ref "R24") (pin "2") (pinfunction "2_2") (pintype "passive"))
      (node (ref "R25") (pin "2") (pinfunction "2_2") (pintype "passive"))
      (node (ref "U5") (pin "2") (pinfunction "-IN_2") (pintype "input"))
    )
    (net (code "194") (name "Net-(U5A-OUT+)") (class "Default")
      (node (ref "U11") (pin "10") (pinfunction "O2_10") (pintype "passive"))
      (node (ref "U11") (pin "7") (pinfunction "O2_7") (pintype "passive"))
      (node (ref "U5") (pin "7") (pinfunction "OUT+_7") (pintype "output"))
    )
    (net (code "195") (name "Net-(U6A--IN)") (class "Default")
      (node (ref "R27") (pin "2") (pinfunction "2_2") (pintype "passive"))
      (node (ref "R28") (pin "2") (pinfunction "2_2") (pintype "passive"))
      (node (ref "U6") (pin "2") (pinfunction "-IN_2") (pintype "input"))
    )
    (net (code "196") (name "Net-(U6A-OUT+)") (class "Default")
      (node (ref "U10") (pin "10") (pinfunction "O2_10") (pintype "passive"))
      (node (ref "U10") (pin "7") (pinfunction "O2_7") (pintype "passive"))
      (node (ref "U6") (pin "7") (pinfunction "OUT+_7") (pintype "output"))
    )
    (net (code "197") (name "Net-(U7-+VOUT)") (class "Default")
      (node (ref "R1") (pin "1") (pinfunction "1_1") (pintype "passive"))
      (node (ref "U7") (pin "VOUT+") (pinfunction "+VOUT_VOUT+") (pintype "bidirectional"))
    )
    (net (code "198") (name "Net-(U9A--IN)") (class "Default")
      (node (ref "R34") (pin "2") (pinfunction "2_2") (pintype "passive"))
      (node (ref "R35") (pin "2") (pinfunction "2_2") (pintype "passive"))
      (node (ref "U9") (pin "2") (pinfunction "-IN_2") (pintype "input"))
    )
    (net (code "199") (name "Net-(U9A-OUT+)") (class "Default")
      (node (ref "U11") (pin "12") (pinfunction "O2_12") (pintype "passive"))
      (node (ref "U11") (pin "5") (pinfunction "O2_5") (pintype "passive"))
      (node (ref "U9") (pin "7") (pinfunction "OUT+_7") (pintype "output"))
    )
    (net (code "200") (name "Net-(U10A-K)") (class "Default")
      (node (ref "R33") (pin "1") (pinfunction "1_1") (pintype "passive"))
      (node (ref "U10") (pin "2") (pinfunction "K_2") (pintype "passive"))
    )
    (net (code "201") (name "Net-(U10B-K)") (class "Default")
      (node (ref "R41") (pin "1") (pinfunction "1_1") (pintype "passive"))
      (node (ref "U10") (pin "4") (pinfunction "K_4") (pintype "passive"))
    )
    (net (code "202") (name "Net-(U11A-K)") (class "Default")
      (node (ref "R75") (pin "1") (pinfunction "1_1") (pintype "passive"))
      (node (ref "U11") (pin "2") (pinfunction "K_2") (pintype "passive"))
    )
    (net (code "203") (name "Net-(U11B-K)") (class "Default")
      (node (ref "R37") (pin "1") (pinfunction "1_1") (pintype "passive"))
      (node (ref "U11") (pin "4") (pinfunction "K_4") (pintype "passive"))
    )
    (net (code "204") (name "Net-(U12A--IN)") (class "Default")
      (node (ref "R38") (pin "2") (pinfunction "2_2") (pintype "passive"))
      (node (ref "R39") (pin "2") (pinfunction "2_2") (pintype "passive"))
      (node (ref "U12") (pin "2") (pinfunction "-IN_2") (pintype "input"))
    )
    (net (code "205") (name "Net-(U12A-OUT+)") (class "Default")
      (node (ref "U10") (pin "12") (pinfunction "O2_12") (pintype "passive"))
      (node (ref "U10") (pin "5") (pinfunction "O2_5") (pintype "passive"))
      (node (ref "U12") (pin "7") (pinfunction "OUT+_7") (pintype "output"))
    )
    (net (code "206") (name "Net-(U14-+VIN)") (class "Default")
      (node (ref "C19") (pin "1") (pinfunction "1_1") (pintype "passive"))
      (node (ref "L5") (pin "2") (pinfunction "2_2") (pintype "passive"))
      (node (ref "U14") (pin "1") (pinfunction "+VIN_1") (pintype "bidirectional"))
    )
    (net (code "207") (name "Net-(U15-EN)") (class "Default")
      (node (ref "R53") (pin "1") (pinfunction "1_1") (pintype "passive"))
      (node (ref "R54") (pin "1") (pinfunction "1_1") (pintype "passive"))
      (node (ref "U15") (pin "4") (pinfunction "EN_4") (pintype "input"))
    )
    (net (code "208") (name "Net-(U15-FB)") (class "Default")
      (node (ref "R46") (pin "2") (pinfunction "2_2") (pintype "passive"))
      (node (ref "R47") (pin "2") (pinfunction "2_2") (pintype "passive"))
      (node (ref "R48") (pin "2") (pinfunction "2_2") (pintype "passive"))
      (node (ref "R50") (pin "2") (pinfunction "2_2") (pintype "passive"))
      (node (ref "R51") (pin "2") (pinfunction "2_2") (pintype "passive"))
      (node (ref "R52") (pin "1") (pinfunction "1_1") (pintype "passive"))
      (node (ref "R78") (pin "2") (pinfunction "2_2") (pintype "passive"))
      (node (ref "U15") (pin "3") (pinfunction "FB_3") (pintype "input"))
    )
    (net (code "209") (name "Net-(U15-SW)") (class "Default")
      (node (ref "L4") (pin "2") (pinfunction "2_2") (pintype "passive"))
      (node (ref "U15") (pin "1") (pinfunction "SW_1") (pintype "power_in"))
    )
    (net (code "210") (name "Net-(U19A--IN)") (class "Default")
      (node (ref "R150") (pin "2") (pinfunction "2_2") (pintype "passive"))
      (node (ref "R151") (pin "2") (pinfunction "2_2") (pintype "passive"))
      (node (ref "U19") (pin "2") (pinfunction "-IN_2") (pintype "input"))
    )
    (net (code "211") (name "Net-(U19A-OUT+)") (class "Default")
      (node (ref "U19") (pin "7") (pinfunction "OUT+_7") (pintype "output"))
      (node (ref "U20") (pin "10") (pinfunction "O2_10") (pintype "passive"))
      (node (ref "U20") (pin "7") (pinfunction "O2_7") (pintype "passive"))
    )
    (net (code "212") (name "Net-(U20A-K)") (class "Default")
      (node (ref "R153") (pin "1") (pinfunction "1_1") (pintype "passive"))
      (node (ref "U20") (pin "2") (pinfunction "K_2") (pintype "passive"))
    )
    (net (code "213") (name "Net-(U20B-K)") (class "Default")
      (node (ref "R157") (pin "1") (pinfunction "1_1") (pintype "passive"))
      (node (ref "U20") (pin "4") (pinfunction "K_4") (pintype "passive"))
    )
    (net (code "214") (name "Net-(U21A--IN)") (class "Default")
      (node (ref "R154") (pin "2") (pinfunction "2_2") (pintype "passive"))
      (node (ref "R155") (pin "2") (pinfunction "2_2") (pintype "passive"))
      (node (ref "U21") (pin "2") (pinfunction "-IN_2") (pintype "input"))
    )
    (net (code "215") (name "Net-(U21A-OUT+)") (class "Default")
      (node (ref "U20") (pin "12") (pinfunction "O2_12") (pintype "passive"))
      (node (ref "U20") (pin "5") (pinfunction "O2_5") (pintype "passive"))
      (node (ref "U21") (pin "7") (pinfunction "OUT+_7") (pintype "output"))
    )
    (net (code "216") (name "Net-(U22A--IN)") (class "Default")
      (node (ref "R158") (pin "2") (pinfunction "2_2") (pintype "passive"))
      (node (ref "R159") (pin "2") (pinfunction "2_2") (pintype "passive"))
      (node (ref "U22") (pin "2") (pinfunction "-IN_2") (pintype "input"))
    )
    (net (code "217") (name "Net-(U22A-OUT+)") (class "Default")
      (node (ref "U22") (pin "7") (pinfunction "OUT+_7") (pintype "output"))
      (node (ref "U23") (pin "10") (pinfunction "O2_10") (pintype "passive"))
      (node (ref "U23") (pin "7") (pinfunction "O2_7") (pintype "passive"))
    )
    (net (code "218") (name "Net-(U23A-K)") (class "Default")
      (node (ref "R161") (pin "1") (pinfunction "1_1") (pintype "passive"))
      (node (ref "U23") (pin "2") (pinfunction "K_2") (pintype "passive"))
    )
    (net (code "219") (name "Net-(U23B-K)") (class "Default")
      (node (ref "R181") (pin "1") (pinfunction "1_1") (pintype "passive"))
      (node (ref "U23") (pin "4") (pinfunction "K_4") (pintype "passive"))
    )
    (net (code "220") (name "Net-(U24A--IN)") (class "Default")
      (node (ref "R162") (pin "2") (pinfunction "2_2") (pintype "passive"))
      (node (ref "R163") (pin "2") (pinfunction "2_2") (pintype "passive"))
      (node (ref "U24") (pin "2") (pinfunction "-IN_2") (pintype "input"))
    )
    (net (code "221") (name "Net-(U24A-OUT+)") (class "Default")
      (node (ref "U24") (pin "7") (pinfunction "OUT+_7") (pintype "output"))
      (node (ref "U26") (pin "10") (pinfunction "O2_10") (pintype "passive"))
      (node (ref "U26") (pin "7") (pinfunction "O2_7") (pintype "passive"))
    )
    (net (code "222") (name "Net-(U25A--IN)") (class "Default")
      (node (ref "R170") (pin "2") (pinfunction "2_2") (pintype "passive"))
      (node (ref "R171") (pin "2") (pinfunction "2_2") (pintype "passive"))
      (node (ref "U25") (pin "2") (pinfunction "-IN_2") (pintype "input"))
    )
    (net (code "223") (name "Net-(U25A-OUT+)") (class "Default")
      (node (ref "U25") (pin "7") (pinfunction "OUT+_7") (pintype "output"))
      (node (ref "U26") (pin "12") (pinfunction "O2_12") (pintype "passive"))
      (node (ref "U26") (pin "5") (pinfunction "O2_5") (pintype "passive"))
    )
    (net (code "224") (name "Net-(U26A-K)") (class "Default")
      (node (ref "R165") (pin "1") (pinfunction "1_1") (pintype "passive"))
      (node (ref "U26") (pin "2") (pinfunction "K_2") (pintype "passive"))
    )
    (net (code "225") (name "Net-(U26B-K)") (class "Default")
      (node (ref "R173") (pin "1") (pinfunction "1_1") (pintype "passive"))
      (node (ref "U26") (pin "4") (pinfunction "K_4") (pintype "passive"))
    )
    (net (code "226") (name "Net-(U27A--IN)") (class "Default")
      (node (ref "R174") (pin "2") (pinfunction "2_2") (pintype "passive"))
      (node (ref "R175") (pin "2") (pinfunction "2_2") (pintype "passive"))
      (node (ref "U27") (pin "2") (pinfunction "-IN_2") (pintype "input"))
    )
    (net (code "227") (name "Net-(U27A-OUT+)") (class "Default")
      (node (ref "U27") (pin "7") (pinfunction "OUT+_7") (pintype "output"))
      (node (ref "U29") (pin "10") (pinfunction "O2_10") (pintype "passive"))
      (node (ref "U29") (pin "7") (pinfunction "O2_7") (pintype "passive"))
    )
    (net (code "228") (name "Net-(U28A--IN)") (class "Default")
      (node (ref "R178") (pin "2") (pinfunction "2_2") (pintype "passive"))
      (node (ref "R179") (pin "2") (pinfunction "2_2") (pintype "passive"))
      (node (ref "U28") (pin "2") (pinfunction "-IN_2") (pintype "input"))
    )
    (net (code "229") (name "Net-(U28A-OUT+)") (class "Default")
      (node (ref "U23") (pin "12") (pinfunction "O2_12") (pintype "passive"))
      (node (ref "U23") (pin "5") (pinfunction "O2_5") (pintype "passive"))
      (node (ref "U28") (pin "7") (pinfunction "OUT+_7") (pintype "output"))
    )
    (net (code "230") (name "Net-(U29A-K)") (class "Default")
      (node (ref "R177") (pin "1") (pinfunction "1_1") (pintype "passive"))
      (node (ref "U29") (pin "2") (pinfunction "K_2") (pintype "passive"))
    )
    (net (code "231") (name "Net-(U29B-K)") (class "Default")
      (node (ref "R185") (pin "1") (pinfunction "1_1") (pintype "passive"))
      (node (ref "U29") (pin "4") (pinfunction "K_4") (pintype "passive"))
    )
    (net (code "232") (name "Net-(U30-A)") (class "Default")
      (node (ref "R13") (pin "2") (pinfunction "2_2") (pintype "passive"))
      (node (ref "U30") (pin "12") (pinfunction "A_12") (pintype "input"))
    )
    (net (code "233") (name "Net-(U30-B)") (class "Default")
      (node (ref "R14") (pin "2") (pinfunction "2_2") (pintype "passive"))
      (node (ref "U30") (pin "13") (pinfunction "B_13") (pintype "input"))
    )
    (net (code "234") (name "Net-(U30-VCC1)") (class "Default")
      (node (ref "C17") (pin "1") (pinfunction "1_1") (pintype "passive"))
      (node (ref "R49") (pin "1") (pinfunction "1_1") (pintype "passive"))
      (node (ref "U30") (pin "1") (pinfunction "VCC1_1") (pintype "input"))
    )
    (net (code "235") (name "Net-(U31A--IN)") (class "Default")
      (node (ref "R182") (pin "2") (pinfunction "2_2") (pintype "passive"))
      (node (ref "R183") (pin "2") (pinfunction "2_2") (pintype "passive"))
      (node (ref "U31") (pin "2") (pinfunction "-IN_2") (pintype "input"))
    )
    (net (code "236") (name "Net-(U31A-OUT+)") (class "Default")
      (node (ref "U29") (pin "12") (pinfunction "O2_12") (pintype "passive"))
      (node (ref "U29") (pin "5") (pinfunction "O2_5") (pintype "passive"))
      (node (ref "U31") (pin "7") (pinfunction "OUT+_7") (pintype "output"))
    )
    (net (code "237") (name "PC0") (class "Default")
      (node (ref "R71") (pin "1") (pinfunction "1_1") (pintype "passive"))
      (node (ref "U1") (pin "8") (pinfunction "PC0_8") (pintype "bidirectional"))
    )
    (net (code "238") (name "PC1") (class "Default")
      (node (ref "R70") (pin "1") (pinfunction "1_1") (pintype "passive"))
      (node (ref "U1") (pin "9") (pinfunction "PC1_9") (pintype "bidirectional"))
    )
    (net (code "239") (name "PC2") (class "Default")
      (node (ref "R68") (pin "1") (pinfunction "1_1") (pintype "passive"))
      (node (ref "U1") (pin "10") (pinfunction "PC2_10") (pintype "bidirectional"))
    )
    (net (code "240") (name "PC3") (class "Default")
      (node (ref "R69") (pin "1") (pinfunction "1_1") (pintype "passive"))
      (node (ref "U1") (pin "11") (pinfunction "PC3_11") (pintype "bidirectional"))
    )
    (net (code "241") (name "PC4") (class "Default")
      (node (ref "R103") (pin "1") (pinfunction "1_1") (pintype "passive"))
      (node (ref "U1") (pin "24") (pinfunction "PC4_24") (pintype "bidirectional"))
    )
    (net (code "242") (name "PC5") (class "Default")
      (node (ref "R102") (pin "1") (pinfunction "1_1") (pintype "passive"))
      (node (ref "U1") (pin "25") (pinfunction "PC5_25") (pintype "bidirectional"))
    )
    (net (code "243") (name "PC6") (class "Default")
      (node (ref "R100") (pin "1") (pinfunction "1_1") (pintype "passive"))
      (node (ref "U1") (pin "37") (pinfunction "PC6_37") (pintype "bidirectional"))
    )
    (net (code "244") (name "PC7") (class "Default")
      (node (ref "R101") (pin "1") (pinfunction "1_1") (pintype "passive"))
      (node (ref "U1") (pin "38") (pinfunction "PC7_38") (pintype "bidirectional"))
    )
    (net (code "245") (name "PC8") (class "Default")
      (node (ref "R125") (pin "1") (pinfunction "1_1") (pintype "passive"))
      (node (ref "U1") (pin "39") (pinfunction "PC8_39") (pintype "bidirectional"))
    )
    (net (code "246") (name "PC9") (class "Default")
      (node (ref "R124") (pin "1") (pinfunction "1_1") (pintype "passive"))
      (node (ref "U1") (pin "40") (pinfunction "PC9_40") (pintype "bidirectional"))
    )
    (net (code "247") (name "PC10") (class "Default")
      (node (ref "R122") (pin "1") (pinfunction "1_1") (pintype "passive"))
      (node (ref "U1") (pin "51") (pinfunction "PC10_51") (pintype "bidirectional"))
    )
    (net (code "248") (name "PC11") (class "Default")
      (node (ref "R123") (pin "1") (pinfunction "1_1") (pintype "passive"))
      (node (ref "U1") (pin "52") (pinfunction "PC11_52") (pintype "bidirectional"))
    )
    (net (code "249") (name "PC12") (class "Default")
      (node (ref "R147") (pin "1") (pinfunction "1_1") (pintype "passive"))
      (node (ref "U1") (pin "53") (pinfunction "PC12_53") (pintype "bidirectional"))
    )
    (net (code "250") (name "PC13") (class "Default")
      (node (ref "R146") (pin "1") (pinfunction "1_1") (pintype "passive"))
      (node (ref "U1") (pin "2") (pinfunction "PC13_2") (pintype "bidirectional"))
    )
    (net (code "251") (name "PC14") (class "Default")
      (node (ref "R144") (pin "1") (pinfunction "1_1") (pintype "passive"))
      (node (ref "U1") (pin "3") (pinfunction "PC14_3") (pintype "bidirectional"))
    )
    (net (code "252") (name "PC15") (class "Default")
      (node (ref "R145") (pin "1") (pinfunction "1_1") (pintype "passive"))
      (node (ref "U1") (pin "4") (pinfunction "PC15_4") (pintype "bidirectional"))
    )
    (net (code "253") (name "PWM1_OUT") (class "Default")
      (node (ref "PL3") (pin "1") (pinfunction "S_1") (pintype "passive"))
      (node (ref "R26") (pin "2") (pinfunction "2_2") (pintype "passive"))
    )
    (net (code "254") (name "PWM1_SELECT") (class "Default")
      (node (ref "IC7") (pin "1") (pinfunction "QB_1") (pintype "tri_state"))
      (node (ref "R75") (pin "2") (pinfunction "2_2") (pintype "passive"))
    )
    (net (code "255") (name "PWM2_OUT") (class "Default")
      (node (ref "PL3") (pin "8") (pinfunction "S_8") (pintype "passive"))
      (node (ref "R36") (pin "2") (pinfunction "2_2") (pintype "passive"))
    )
    (net (code "256") (name "PWM2_SELECT") (class "Default")
      (node (ref "IC7") (pin "2") (pinfunction "QC_2") (pintype "tri_state"))
      (node (ref "R37") (pin "2") (pinfunction "2_2") (pintype "passive"))
    )
    (net (code "257") (name "PWM3_OUT") (class "Default")
      (node (ref "PL3") (pin "2") (pinfunction "S_2") (pintype "passive"))
      (node (ref "R29") (pin "2") (pinfunction "2_2") (pintype "passive"))
    )
    (net (code "258") (name "PWM3_SELECT") (class "Default")
      (node (ref "IC7") (pin "3") (pinfunction "QD_3") (pintype "tri_state"))
      (node (ref "R33") (pin "2") (pinfunction "2_2") (pintype "passive"))
    )
    (net (code "259") (name "PWM4_OUT") (class "Default")
      (node (ref "PL3") (pin "9") (pinfunction "S_9") (pintype "passive"))
      (node (ref "R40") (pin "2") (pinfunction "2_2") (pintype "passive"))
    )
    (net (code "260") (name "PWM4_SELECT") (class "Default")
      (node (ref "IC7") (pin "4") (pinfunction "QE_4") (pintype "tri_state"))
      (node (ref "R41") (pin "2") (pinfunction "2_2") (pintype "passive"))
    )
    (net (code "261") (name "PWM5_OUT") (class "Default")
      (node (ref "PL3") (pin "5") (pinfunction "S_5") (pintype "passive"))
      (node (ref "R152") (pin "2") (pinfunction "2_2") (pintype "passive"))
    )
    (net (code "262") (name "PWM5_SELECT") (class "Default")
      (node (ref "IC7") (pin "7") (pinfunction "QH_7") (pintype "tri_state"))
      (node (ref "R153") (pin "2") (pinfunction "2_2") (pintype "passive"))
    )
    (net (code "263") (name "PWM8_OUT") (class "Default")
      (node (ref "PL3") (pin "7") (pinfunction "S_7") (pintype "passive"))
      (node (ref "R160") (pin "2") (pinfunction "2_2") (pintype "passive"))
    )
    (net (code "264") (name "PWM8_SELECT") (class "Default")
      (node (ref "IC8") (pin "4") (pinfunction "QE_4") (pintype "tri_state"))
      (node (ref "R161") (pin "2") (pinfunction "2_2") (pintype "passive"))
    )
    (net (code "265") (name "PWM9_OUT") (class "Default")
      (node (ref "PL3") (pin "12") (pinfunction "S_12") (pintype "passive"))
      (node (ref "R156") (pin "2") (pinfunction "2_2") (pintype "passive"))
    )
    (net (code "266") (name "PWM9_SELECT") (class "Default")
      (node (ref "IC8") (pin "1") (pinfunction "QB_1") (pintype "tri_state"))
      (node (ref "R157") (pin "2") (pinfunction "2_2") (pintype "passive"))
    )
    (net (code "267") (name "PWM10_OUT") (class "Default")
      (node (ref "PL3") (pin "3") (pinfunction "S_3") (pintype "passive"))
      (node (ref "R164") (pin "2") (pinfunction "2_2") (pintype "passive"))
    )
    (net (code "268") (name "PWM10_SELECT") (class "Default")
      (node (ref "IC7") (pin "5") (pinfunction "QF_5") (pintype "tri_state"))
      (node (ref "R165") (pin "2") (pinfunction "2_2") (pintype "passive"))
    )
    (net (code "269") (name "PWM11_OUT") (class "Default")
      (node (ref "PL3") (pin "10") (pinfunction "S_10") (pintype "passive"))
      (node (ref "R172") (pin "2") (pinfunction "2_2") (pintype "passive"))
    )
    (net (code "270") (name "PWM11_SELECT") (class "Default")
      (node (ref "IC7") (pin "6") (pinfunction "QG_6") (pintype "tri_state"))
      (node (ref "R173") (pin "2") (pinfunction "2_2") (pintype "passive"))
    )
    (net (code "271") (name "PWM12_OUT") (class "Default")
      (node (ref "PL3") (pin "14") (pinfunction "S_14") (pintype "passive"))
      (node (ref "R180") (pin "2") (pinfunction "2_2") (pintype "passive"))
    )
    (net (code "272") (name "PWM12_SELECT") (class "Default")
      (node (ref "IC8") (pin "5") (pinfunction "QF_5") (pintype "tri_state"))
      (node (ref "R181") (pin "2") (pinfunction "2_2") (pintype "passive"))
    )
    (net (code "273") (name "PWM13_OUT") (class "Default")
      (node (ref "PL3") (pin "6") (pinfunction "S_6") (pintype "passive"))
      (node (ref "R176") (pin "2") (pinfunction "2_2") (pintype "passive"))
    )
    (net (code "274") (name "PWM13_SELECT") (class "Default")
      (node (ref "IC8") (pin "2") (pinfunction "QC_2") (pintype "tri_state"))
      (node (ref "R177") (pin "2") (pinfunction "2_2") (pintype "passive"))
    )
    (net (code "275") (name "PWM14_OUT") (class "Default")
      (node (ref "PL3") (pin "13") (pinfunction "S_13") (pintype "passive"))
      (node (ref "R184") (pin "2") (pinfunction "2_2") (pintype "passive"))
    )
    (net (code "276") (name "PWM14_SELECT") (class "Default")
      (node (ref "IC8") (pin "3") (pinfunction "QD_3") (pintype "tri_state"))
      (node (ref "R185") (pin "2") (pinfunction "2_2") (pintype "passive"))
    )
    (net (code "277") (name "PWR_EN_MCU") (class "Default")
      (node (ref "R53") (pin "2") (pinfunction "2_2") (pintype "passive"))
      (node (ref "U1") (pin "44") (pinfunction "PA11_44") (pintype "bidirectional"))
    )
    (net (code "278") (name "SPI1_MOSI") (class "Default")
      (node (ref "IC7") (pin "14") (pinfunction "SER_14") (pintype "input"))
      (node (ref "R191") (pin "1") (pinfunction "1_1") (pintype "passive"))
      (node (ref "U1") (pin "57") (pinfunction "PB5_57") (pintype "bidirectional"))
    )
    (net (code "279") (name "SPI1_SCK") (class "Default")
      (node (ref "IC7") (pin "11") (pinfunction "SCK_11") (pintype "input"))
      (node (ref "IC8") (pin "11") (pinfunction "SCK_11") (pintype "input"))
      (node (ref "R190") (pin "1") (pinfunction "1_1") (pintype "passive"))
      (node (ref "U1") (pin "55") (pinfunction "PB3_55") (pintype "bidirectional"))
    )
    (net (code "280") (name "SPI_PB7") (class "Default")
      (node (ref "IC7") (pin "12") (pinfunction "RCK_12") (pintype "input"))
      (node (ref "IC8") (pin "12") (pinfunction "RCK_12") (pintype "input"))
      (node (ref "R189") (pin "1") (pinfunction "1_1") (pintype "passive"))
      (node (ref "U1") (pin "59") (pinfunction "PB7_59") (pintype "bidirectional"))
    )
    (net (code "281") (name "SPI_PD2") (class "Default")
      (node (ref "IC7") (pin "13") (pinfunction "G_13") (pintype "input"))
      (node (ref "IC8") (pin "13") (pinfunction "G_13") (pintype "input"))
      (node (ref "R188") (pin "1") (pinfunction "1_1") (pintype "passive"))
      (node (ref "U1") (pin "54") (pinfunction "PD2_54") (pintype "bidirectional"))
    )
    (net (code "282") (name "SWCLK") (class "Default")
      (node (ref "K1") (pin "4") (pinfunction "SWDCLK/TCK_4") (pintype "bidirectional"))
      (node (ref "U1") (pin "49") (pinfunction "PA14_49") (pintype "bidirectional"))
    )
    (net (code "283") (name "SWDIO") (class "Default")
      (node (ref "K1") (pin "2") (pinfunction "SWDIO/TMS_2") (pintype "bidirectional"))
      (node (ref "U1") (pin "46") (pinfunction "PA13_46") (pintype "bidirectional"))
    )
    (net (code "284") (name "TIM1_CH1") (class "Default")
      (node (ref "R24") (pin "1") (pinfunction "1_1") (pintype "passive"))
      (node (ref "U1") (pin "41") (pinfunction "PA8_41") (pintype "bidirectional"))
    )
    (net (code "285") (name "TIM2_CH1") (class "Default")
      (node (ref "R34") (pin "1") (pinfunction "1_1") (pintype "passive"))
      (node (ref "U1") (pin "50") (pinfunction "PA15_50") (pintype "bidirectional"))
    )
    (net (code "286") (name "TIM3_CH1") (class "Default")
      (node (ref "R27") (pin "1") (pinfunction "1_1") (pintype "passive"))
      (node (ref "U1") (pin "56") (pinfunction "PB4_56") (pintype "bidirectional"))
    )
    (net (code "287") (name "TIM4_CH1") (class "Default")
      (node (ref "R38") (pin "1") (pinfunction "1_1") (pintype "passive"))
      (node (ref "U1") (pin "58") (pinfunction "PB6_58") (pintype "bidirectional"))
    )
    (net (code "288") (name "TIM5_CH1") (class "Default")
      (node (ref "R150") (pin "1") (pinfunction "1_1") (pintype "passive"))
      (node (ref "U1") (pin "14") (pinfunction "PA0_14") (pintype "bidirectional"))
    )
    (net (code "289") (name "TIM8_CH2N") (class "Default")
      (node (ref "R158") (pin "1") (pinfunction "1_1") (pintype "passive"))
      (node (ref "U1") (pin "26") (pinfunction "PB0_26") (pintype "bidirectional"))
    )
    (net (code "290") (name "TIM9_CH1") (class "Default")
      (node (ref "R154") (pin "1") (pinfunction "1_1") (pintype "passive"))
      (node (ref "U1") (pin "16") (pinfunction "PA2_16") (pintype "bidirectional"))
    )
    (net (code "291") (name "TIM10_CH1") (class "Default")
      (node (ref "R162") (pin "1") (pinfunction "1_1") (pintype "passive"))
      (node (ref "U1") (pin "61") (pinfunction "PB8_61") (pintype "bidirectional"))
    )
    (net (code "292") (name "TIM11_CH1") (class "Default")
      (node (ref "R170") (pin "1") (pinfunction "1_1") (pintype "passive"))
      (node (ref "U1") (pin "62") (pinfunction "PB9_62") (pintype "bidirectional"))
    )
    (net (code "293") (name "TIM12_CH1") (class "Default")
      (node (ref "R178") (pin "1") (pinfunction "1_1") (pintype "passive"))
      (node (ref "U1") (pin "35") (pinfunction "PB14_35") (pintype "bidirectional"))
    )
    (net (code "294") (name "TIM13_CH1") (class "Default")
      (node (ref "R174") (pin "1") (pinfunction "1_1") (pintype "passive"))
      (node (ref "U1") (pin "22") (pinfunction "PA6_22") (pintype "bidirectional"))
    )
    (net (code "295") (name "TIM14_CH1") (class "Default")
      (node (ref "R182") (pin "1") (pinfunction "1_1") (pintype "passive"))
      (node (ref "U1") (pin "23") (pinfunction "PA7_23") (pintype "bidirectional"))
    )
    (net (code "296") (name "TRANSIL") (class "Default")
      (node (ref "D10") (pin "2") (pinfunction "C2_2") (pintype "passive"))
      (node (ref "D12") (pin "2") (pinfunction "C2_2") (pintype "passive"))
      (node (ref "D14") (pin "2") (pinfunction "C2_2") (pintype "passive"))
      (node (ref "D25") (pin "2") (pinfunction "C2_2") (pintype "passive"))
      (node (ref "D26") (pin "2") (pinfunction "C2_2") (pintype "passive"))
      (node (ref "D27") (pin "2") (pinfunction "C2_2") (pintype "passive"))
      (node (ref "D28") (pin "2") (pinfunction "C2_2") (pintype "passive"))
      (node (ref "D30") (pin "2") (pinfunction "C2_2") (pintype "passive"))
      (node (ref "D31") (pin "2") (pinfunction "C2_2") (pintype "passive"))
      (node (ref "D32") (pin "2") (pinfunction "C2_2") (pintype "passive"))
      (node (ref "D33") (pin "2") (pinfunction "C2_2") (pintype "passive"))
      (node (ref "D7") (pin "C") (pinfunction "C_C") (pintype "passive"))
      (node (ref "D8") (pin "2") (pinfunction "C2_2") (pintype "passive"))
    )
    (net (code "297") (name "UART_DE") (class "Default")
      (node (ref "R32") (pin "2") (pinfunction "2_2") (pintype "passive"))
      (node (ref "U1") (pin "45") (pinfunction "PA12_45") (pintype "bidirectional"))
      (node (ref "U30") (pin "4") (pinfunction "~{RE}_4") (pintype "input"))
      (node (ref "U30") (pin "5") (pinfunction "DE_5") (pintype "input"))
    )
    (net (code "298") (name "UART_RXD") (class "Default")
      (node (ref "R31") (pin "2") (pinfunction "2_2") (pintype "passive"))
      (node (ref "U1") (pin "43") (pinfunction "PA10_43") (pintype "bidirectional"))
      (node (ref "U30") (pin "3") (pinfunction "R_3") (pintype "input"))
    )
    (net (code "299") (name "UART_TXD") (class "Default")
      (node (ref "R30") (pin "2") (pinfunction "2_2") (pintype "passive"))
      (node (ref "U1") (pin "42") (pinfunction "PA9_42") (pintype "bidirectional"))
      (node (ref "U30") (pin "6") (pinfunction "D_6") (pintype "input"))
    )
    (net (code "300") (name "V_VARIABLE") (class "Default")
      (node (ref "C11") (pin "1") (pinfunction "1_1") (pintype "passive"))
      (node (ref "C14") (pin "1") (pinfunction "1_1") (pintype "passive"))
      (node (ref "C24") (pin "1") (pinfunction "1_1") (pintype "passive"))
      (node (ref "C25") (pin "1") (pinfunction "1_1") (pintype "passive"))
      (node (ref "C26") (pin "2") (pinfunction "2_2") (pintype "passive"))
      (node (ref "C28") (pin "1") (pinfunction "1_1") (pintype "passive"))
      (node (ref "C32") (pin "1") (pinfunction "1_1") (pintype "passive"))
      (node (ref "C34") (pin "1") (pinfunction "1_1") (pintype "passive"))
      (node (ref "C35") (pin "1") (pinfunction "1_1") (pintype "passive"))
      (node (ref "C36") (pin "2") (pinfunction "2_2") (pintype "passive"))
      (node (ref "C37") (pin "2") (pinfunction "2_2") (pintype "passive"))
      (node (ref "C38") (pin "1") (pinfunction "1_1") (pintype "passive"))
      (node (ref "C39") (pin "2") (pinfunction "2_2") (pintype "passive"))
      (node (ref "C40") (pin "1") (pinfunction "1_1") (pintype "passive"))
      (node (ref "C42") (pin "1") (pinfunction "1_1") (pintype "passive"))
      (node (ref "C43") (pin "1") (pinfunction "1_1") (pintype "passive"))
      (node (ref "C45") (pin "1") (pinfunction "1_1") (pintype "passive"))
      (node (ref "C46") (pin "1") (pinfunction "1_1") (pintype "passive"))
      (node (ref "C51") (pin "1") (pinfunction "1_1") (pintype "passive"))
      (node (ref "C52") (pin "1") (pinfunction "1_1") (pintype "passive"))
      (node (ref "C53") (pin "1") (pinfunction "1_1") (pintype "passive"))
      (node (ref "C54") (pin "1") (pinfunction "1_1") (pintype "passive"))
      (node (ref "C55") (pin "1") (pinfunction "1_1") (pintype "passive"))
      (node (ref "C56") (pin "1") (pinfunction "1_1") (pintype "passive"))
      (node (ref "C57") (pin "1") (pinfunction "1_1") (pintype "passive"))
      (node (ref "R52") (pin "2") (pinfunction "2_2") (pintype "passive"))
      (node (ref "R63") (pin "2") (pinfunction "2_2") (pintype "passive"))
      (node (ref "U12") (pin "1") (pinfunction "VCC_1") (pintype "power_in"))
      (node (ref "U12") (pin "8") (pinfunction "VCC_8") (pintype "power_in"))
      (node (ref "U15") (pin "5") (pinfunction "VOUT_5") (pintype "output"))
      (node (ref "U19") (pin "1") (pinfunction "VCC_1") (pintype "power_in"))
      (node (ref "U19") (pin "8") (pinfunction "VCC_8") (pintype "power_in"))
      (node (ref "U21") (pin "1") (pinfunction "VCC_1") (pintype "power_in"))
      (node (ref "U21") (pin "8") (pinfunction "VCC_8") (pintype "power_in"))
      (node (ref "U22") (pin "1") (pinfunction "VCC_1") (pintype "power_in"))
      (node (ref "U22") (pin "8") (pinfunction "VCC_8") (pintype "power_in"))
      (node (ref "U24") (pin "1") (pinfunction "VCC_1") (pintype "power_in"))
      (node (ref "U24") (pin "8") (pinfunction "VCC_8") (pintype "power_in"))
      (node (ref "U25") (pin "1") (pinfunction "VCC_1") (pintype "power_in"))
      (node (ref "U25") (pin "8") (pinfunction "VCC_8") (pintype "power_in"))
      (node (ref "U27") (pin "1") (pinfunction "VCC_1") (pintype "power_in"))
      (node (ref "U27") (pin "8") (pinfunction "VCC_8") (pintype "power_in"))
      (node (ref "U28") (pin "1") (pinfunction "VCC_1") (pintype "power_in"))
      (node (ref "U28") (pin "8") (pinfunction "VCC_8") (pintype "power_in"))
      (node (ref "U31") (pin "1") (pinfunction "VCC_1") (pintype "power_in"))
      (node (ref "U31") (pin "8") (pinfunction "VCC_8") (pintype "power_in"))
      (node (ref "U5") (pin "1") (pinfunction "VCC_1") (pintype "power_in"))
      (node (ref "U5") (pin "8") (pinfunction "VCC_8") (pintype "power_in"))
      (node (ref "U6") (pin "1") (pinfunction "VCC_1") (pintype "power_in"))
      (node (ref "U6") (pin "8") (pinfunction "VCC_8") (pintype "power_in"))
      (node (ref "U9") (pin "1") (pinfunction "VCC_1") (pintype "power_in"))
      (node (ref "U9") (pin "8") (pinfunction "VCC_8") (pintype "power_in"))
    )
    (net (code "301") (name "unconnected-(IC7A-QA-Pad15)") (class "Default")
      (node (ref "IC7") (pin "15") (pinfunction "QA_15") (pintype "tri_state"))
    )
    (net (code "302") (name "unconnected-(IC8A-QA-Pad15)") (class "Default")
      (node (ref "IC8") (pin "15") (pinfunction "QA_15") (pintype "tri_state"))
    )
    (net (code "303") (name "unconnected-(IC8A-QH*-Pad9)") (class "Default")
      (node (ref "IC8") (pin "9") (pinfunction "QH*_9") (pintype "tri_state"))
    )
    (net (code "304") (name "unconnected-(K1-KEY-Pad7)") (class "Default")
      (node (ref "K1") (pin "7") (pinfunction "KEY_7") (pintype "bidirectional"))
    )
    (net (code "305") (name "unconnected-(K1-NC{slash}TDI-Pad8)") (class "Default")
      (node (ref "K1") (pin "8") (pinfunction "NC/TDI_8") (pintype "bidirectional"))
    )
    (net (code "306") (name "unconnected-(K1-SWO{slash}TDO-Pad6)") (class "Default")
      (node (ref "K1") (pin "6") (pinfunction "SWO/TDO_6") (pintype "bidirectional"))
    )
    (net (code "307") (name "unconnected-(U30-NC-Pad11)") (class "Default")
      (node (ref "U30") (pin "11") (pinfunction "NC_11") (pintype "input"))
    )
    (net (code "308") (name "unconnected-(U30-NC-Pad14)") (class "Default")
      (node (ref "U30") (pin "14") (pinfunction "NC_14") (pintype "input"))
    )
  )
)
